# TD4_CPU.net
KiCad netlist of a schematic drawn in Altium Designer
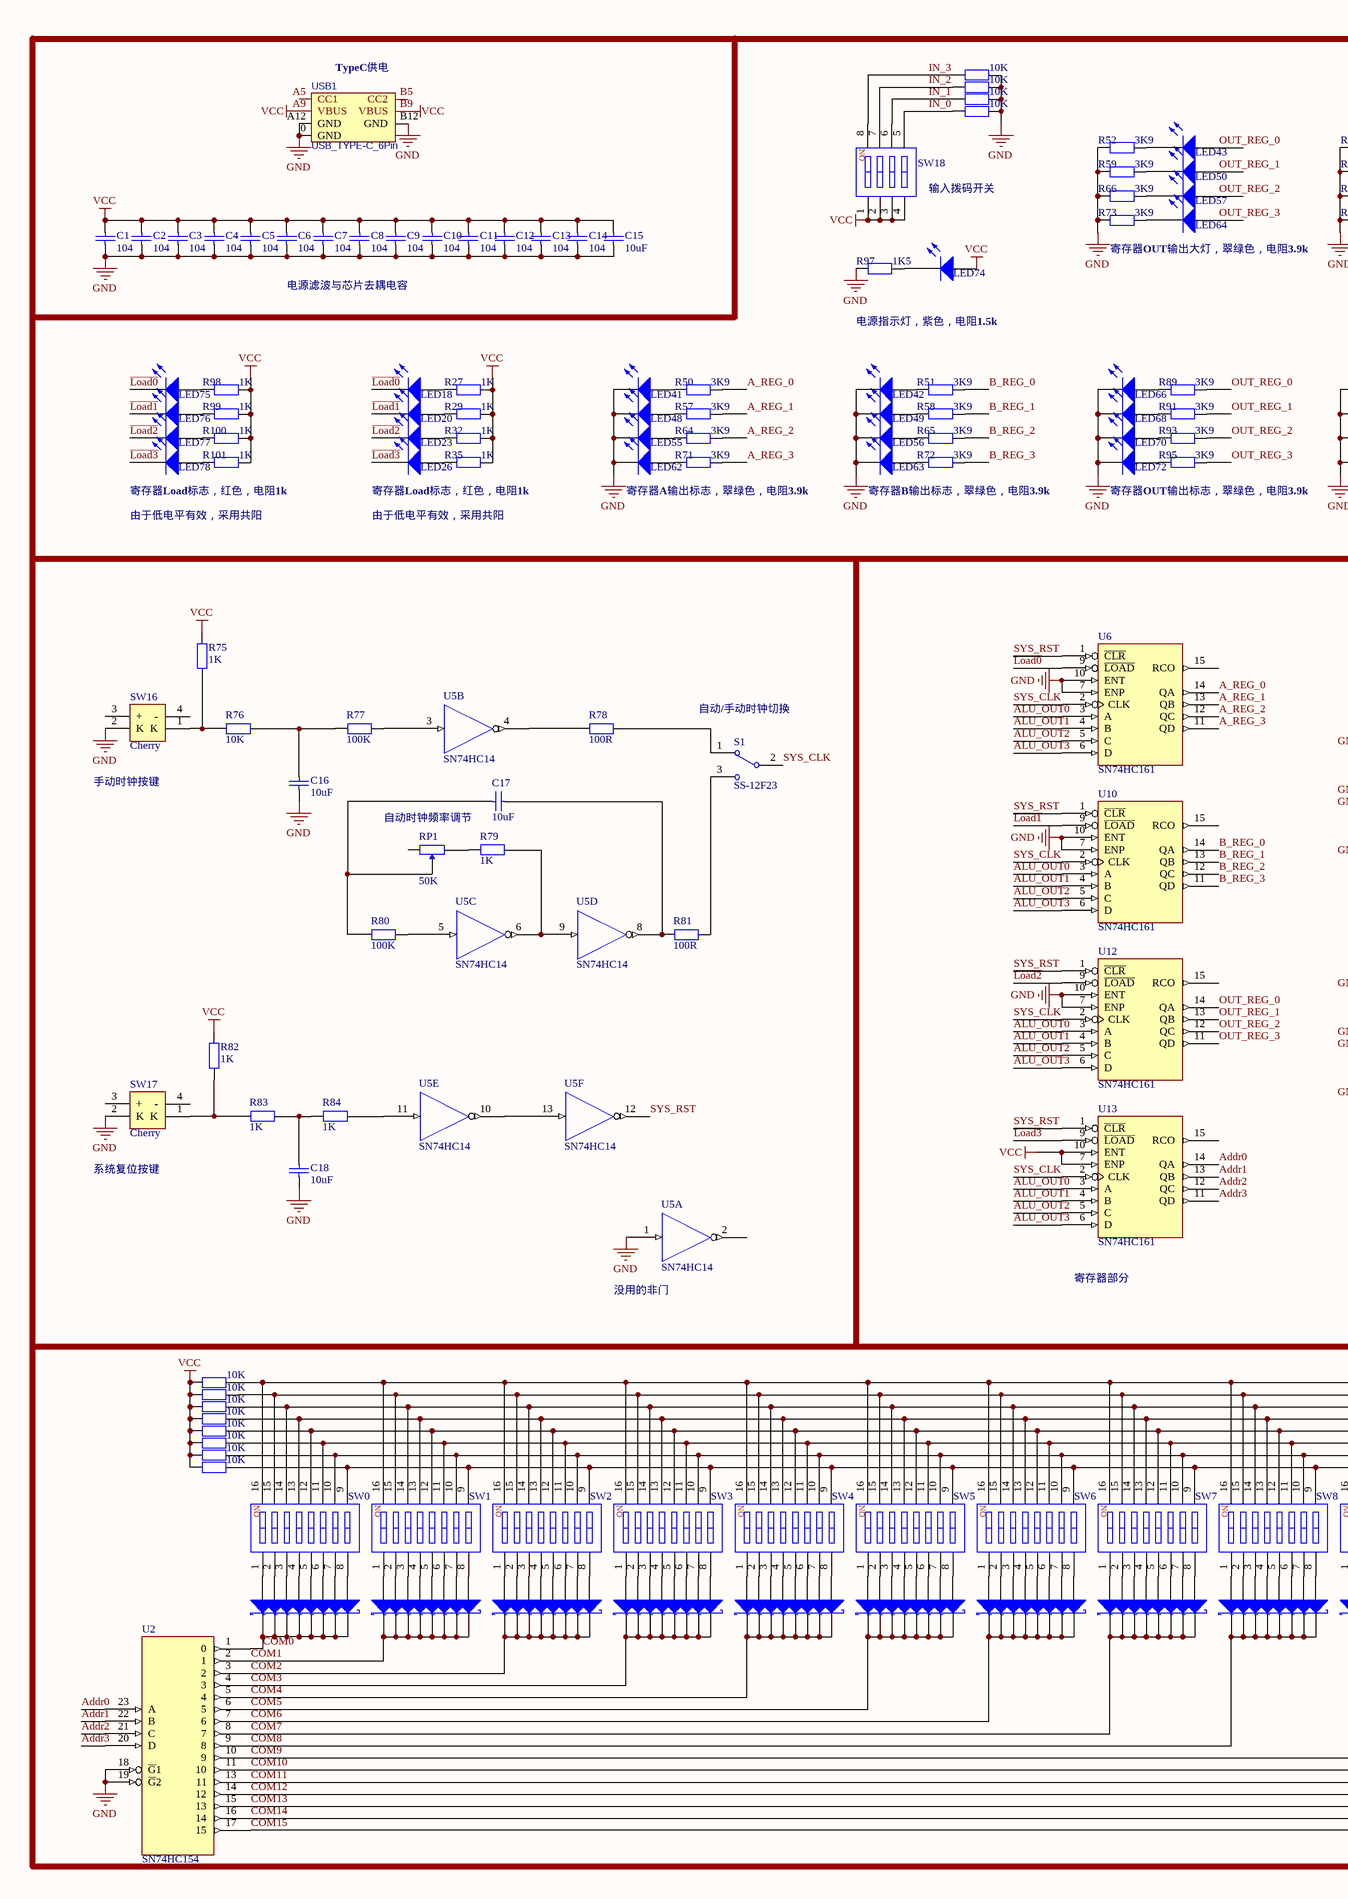
[diagram p0: TD4_CPU.SchDoc, left]
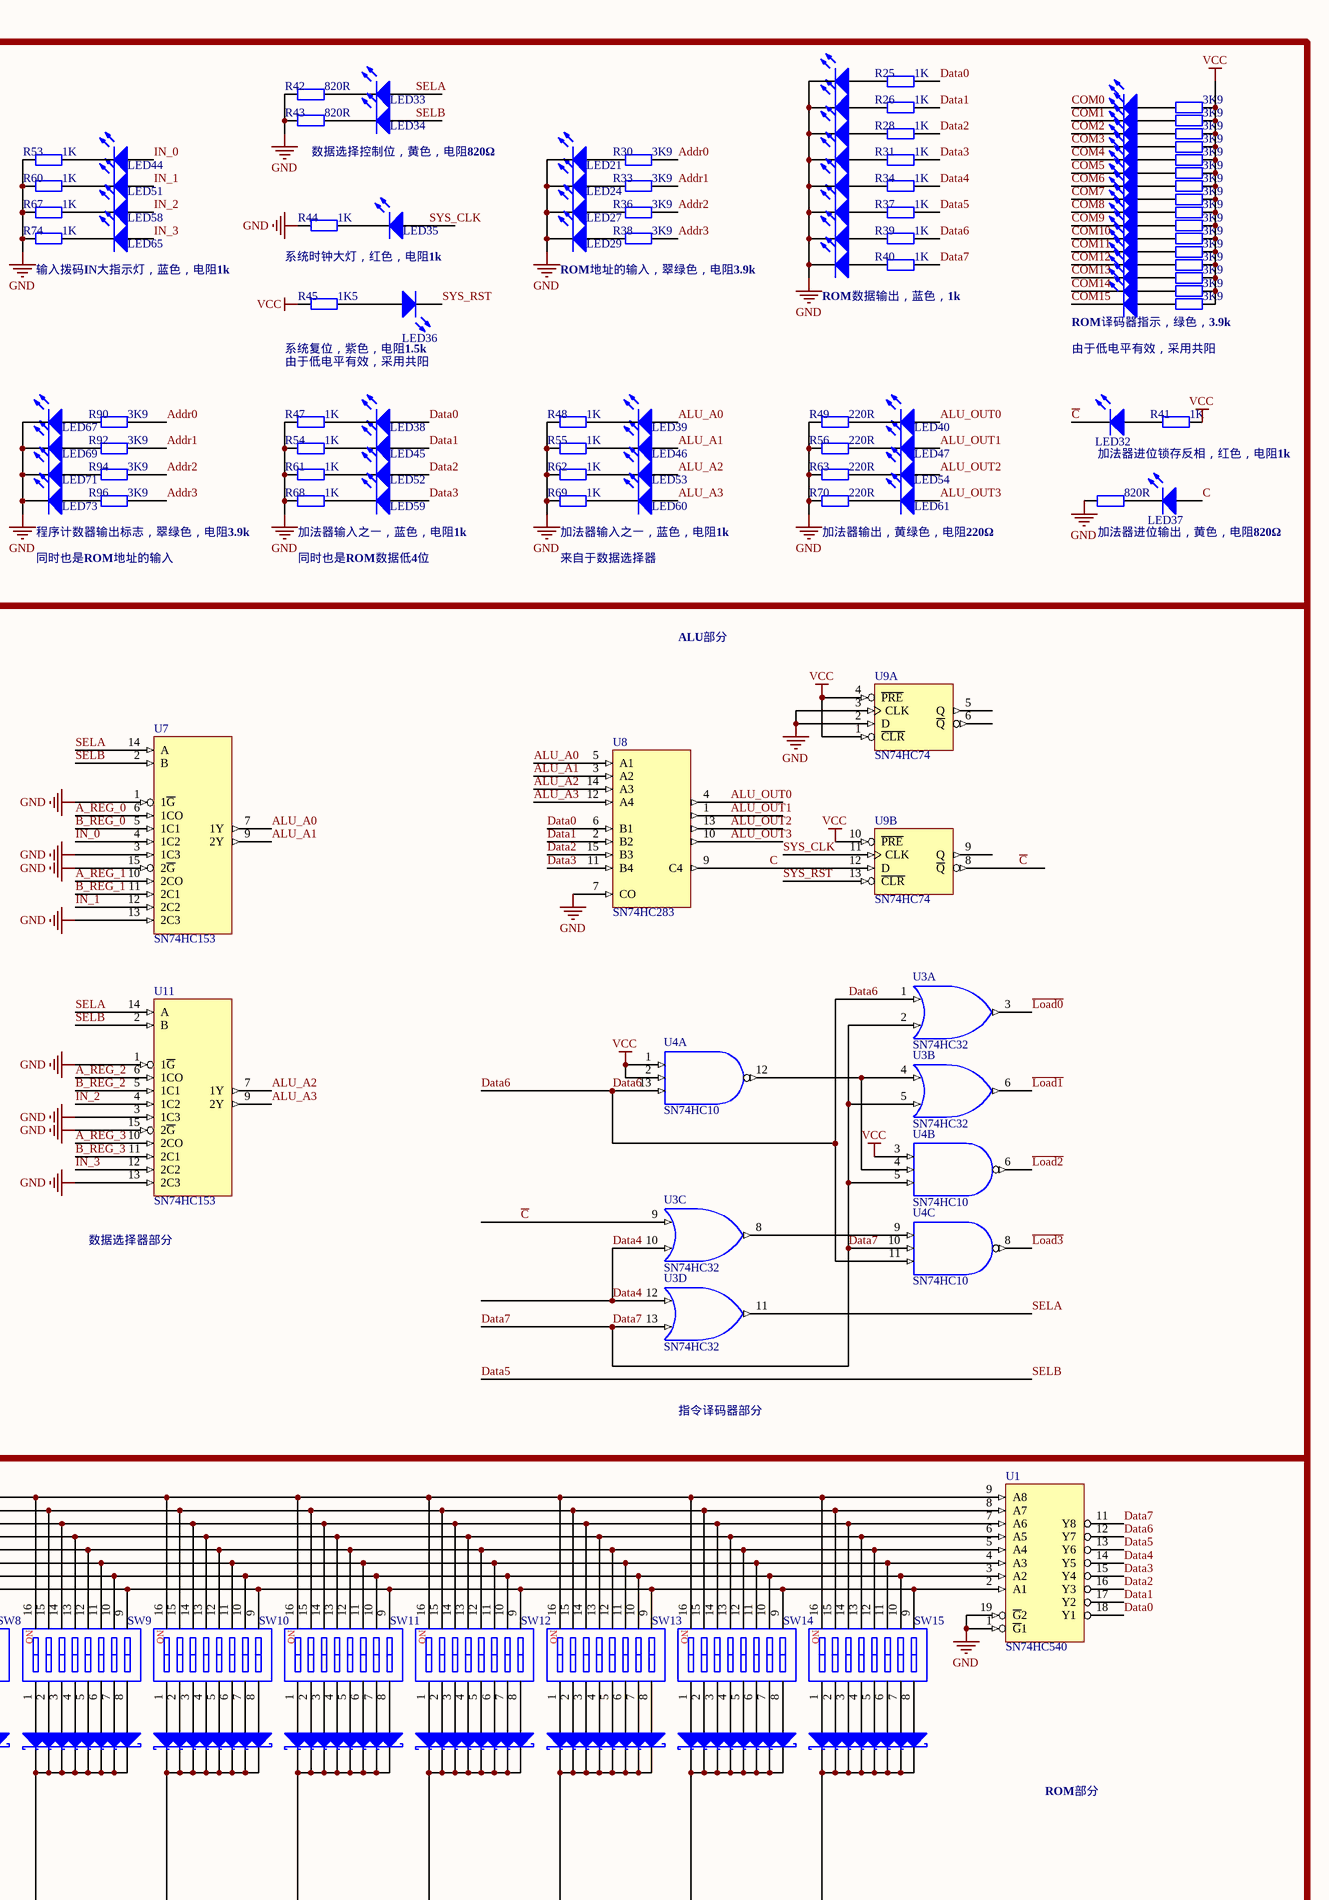
[diagram p1: TD4_CPU.SchDoc, right]

(export (version "E")
  (design (tool "Eeschema 10.0.6"))
  (components
    (comp (ref "C1")
      (value "104")
      (footprint "C0805_L")
      (description "贴片电容/MLCC电容")
      (libsource (lib "0.1 - 电阻-电容-电感-保险丝-晶振-晶体-磁珠-电位器-法拉电容-馈通电容") (part "C"))
    )
    (comp (ref "C2")
      (value "104")
      (footprint "C0805_L")
      (description "贴片电容/MLCC电容")
      (libsource (lib "0.1 - 电阻-电容-电感-保险丝-晶振-晶体-磁珠-电位器-法拉电容-馈通电容") (part "C"))
    )
    (comp (ref "C3")
      (value "104")
      (footprint "C0805_L")
      (description "贴片电容/MLCC电容")
      (libsource (lib "0.1 - 电阻-电容-电感-保险丝-晶振-晶体-磁珠-电位器-法拉电容-馈通电容") (part "C"))
    )
    (comp (ref "C4")
      (value "104")
      (footprint "C0805_L")
      (description "贴片电容/MLCC电容")
      (libsource (lib "0.1 - 电阻-电容-电感-保险丝-晶振-晶体-磁珠-电位器-法拉电容-馈通电容") (part "C"))
    )
    (comp (ref "C5")
      (value "104")
      (footprint "C0805_L")
      (description "贴片电容/MLCC电容")
      (libsource (lib "0.1 - 电阻-电容-电感-保险丝-晶振-晶体-磁珠-电位器-法拉电容-馈通电容") (part "C"))
    )
    (comp (ref "C6")
      (value "104")
      (footprint "C0805_L")
      (description "贴片电容/MLCC电容")
      (libsource (lib "0.1 - 电阻-电容-电感-保险丝-晶振-晶体-磁珠-电位器-法拉电容-馈通电容") (part "C"))
    )
    (comp (ref "C7")
      (value "104")
      (footprint "C0805_L")
      (description "贴片电容/MLCC电容")
      (libsource (lib "0.1 - 电阻-电容-电感-保险丝-晶振-晶体-磁珠-电位器-法拉电容-馈通电容") (part "C"))
    )
    (comp (ref "C8")
      (value "104")
      (footprint "C0805_L")
      (description "贴片电容/MLCC电容")
      (libsource (lib "0.1 - 电阻-电容-电感-保险丝-晶振-晶体-磁珠-电位器-法拉电容-馈通电容") (part "C"))
    )
    (comp (ref "C9")
      (value "104")
      (footprint "C0805_L")
      (description "贴片电容/MLCC电容")
      (libsource (lib "0.1 - 电阻-电容-电感-保险丝-晶振-晶体-磁珠-电位器-法拉电容-馈通电容") (part "C"))
    )
    (comp (ref "C10")
      (value "104")
      (footprint "C0805_L")
      (description "贴片电容/MLCC电容")
      (libsource (lib "0.1 - 电阻-电容-电感-保险丝-晶振-晶体-磁珠-电位器-法拉电容-馈通电容") (part "C"))
    )
    (comp (ref "C11")
      (value "104")
      (footprint "C0805_L")
      (description "贴片电容/MLCC电容")
      (libsource (lib "0.1 - 电阻-电容-电感-保险丝-晶振-晶体-磁珠-电位器-法拉电容-馈通电容") (part "C"))
    )
    (comp (ref "C12")
      (value "104")
      (footprint "C0805_L")
      (description "贴片电容/MLCC电容")
      (libsource (lib "0.1 - 电阻-电容-电感-保险丝-晶振-晶体-磁珠-电位器-法拉电容-馈通电容") (part "C"))
    )
    (comp (ref "C13")
      (value "104")
      (footprint "C0805_L")
      (description "贴片电容/MLCC电容")
      (libsource (lib "0.1 - 电阻-电容-电感-保险丝-晶振-晶体-磁珠-电位器-法拉电容-馈通电容") (part "C"))
    )
    (comp (ref "C14")
      (value "104")
      (footprint "C0805_L")
      (description "贴片电容/MLCC电容")
      (libsource (lib "0.1 - 电阻-电容-电感-保险丝-晶振-晶体-磁珠-电位器-法拉电容-馈通电容") (part "C"))
    )
    (comp (ref "C15")
      (value "10uF")
      (footprint "C0805_L")
      (description "贴片电容/MLCC电容")
      (libsource (lib "0.1 - 电阻-电容-电感-保险丝-晶振-晶体-磁珠-电位器-法拉电容-馈通电容") (part "C"))
    )
    (comp (ref "C16")
      (value "10uF")
      (footprint "C0805_L")
      (description "贴片电容/MLCC电容")
      (libsource (lib "0.1 - 电阻-电容-电感-保险丝-晶振-晶体-磁珠-电位器-法拉电容-馈通电容") (part "C"))
    )
    (comp (ref "C17")
      (value "10uF")
      (footprint "C0805_L")
      (description "贴片电容/MLCC电容")
      (libsource (lib "0.1 - 电阻-电容-电感-保险丝-晶振-晶体-磁珠-电位器-法拉电容-馈通电容") (part "C"))
    )
    (comp (ref "C18")
      (value "10uF")
      (footprint "C0805_L")
      (description "贴片电容/MLCC电容")
      (libsource (lib "0.1 - 电阻-电容-电感-保险丝-晶振-晶体-磁珠-电位器-法拉电容-馈通电容") (part "C"))
    )
    (comp (ref "D1")
      (value "SS14")
      (footprint "SOD-123")
      (description "肖特基二极管")
      (libsource (lib "0.2 - 二极管-TVS-ESD-整流桥-放电管") (part "SS14"))
    )
    (comp (ref "D2")
      (value "SS14")
      (footprint "SOD-123")
      (description "肖特基二极管")
      (libsource (lib "0.2 - 二极管-TVS-ESD-整流桥-放电管") (part "SS14"))
    )
    (comp (ref "D3")
      (value "SS14")
      (footprint "SOD-123")
      (description "肖特基二极管")
      (libsource (lib "0.2 - 二极管-TVS-ESD-整流桥-放电管") (part "SS14"))
    )
    (comp (ref "D4")
      (value "SS14")
      (footprint "SOD-123")
      (description "肖特基二极管")
      (libsource (lib "0.2 - 二极管-TVS-ESD-整流桥-放电管") (part "SS14"))
    )
    (comp (ref "D5")
      (value "SS14")
      (footprint "SOD-123")
      (description "肖特基二极管")
      (libsource (lib "0.2 - 二极管-TVS-ESD-整流桥-放电管") (part "SS14"))
    )
    (comp (ref "D6")
      (value "SS14")
      (footprint "SOD-123")
      (description "肖特基二极管")
      (libsource (lib "0.2 - 二极管-TVS-ESD-整流桥-放电管") (part "SS14"))
    )
    (comp (ref "D7")
      (value "SS14")
      (footprint "SOD-123")
      (description "肖特基二极管")
      (libsource (lib "0.2 - 二极管-TVS-ESD-整流桥-放电管") (part "SS14"))
    )
    (comp (ref "D8")
      (value "SS14")
      (footprint "SOD-123")
      (description "肖特基二极管")
      (libsource (lib "0.2 - 二极管-TVS-ESD-整流桥-放电管") (part "SS14"))
    )
    (comp (ref "D9")
      (value "SS14")
      (footprint "SOD-123")
      (description "肖特基二极管")
      (libsource (lib "0.2 - 二极管-TVS-ESD-整流桥-放电管") (part "SS14"))
    )
    (comp (ref "D10")
      (value "SS14")
      (footprint "SOD-123")
      (description "肖特基二极管")
      (libsource (lib "0.2 - 二极管-TVS-ESD-整流桥-放电管") (part "SS14"))
    )
    (comp (ref "D11")
      (value "SS14")
      (footprint "SOD-123")
      (description "肖特基二极管")
      (libsource (lib "0.2 - 二极管-TVS-ESD-整流桥-放电管") (part "SS14"))
    )
    (comp (ref "D12")
      (value "SS14")
      (footprint "SOD-123")
      (description "肖特基二极管")
      (libsource (lib "0.2 - 二极管-TVS-ESD-整流桥-放电管") (part "SS14"))
    )
    (comp (ref "D13")
      (value "SS14")
      (footprint "SOD-123")
      (description "肖特基二极管")
      (libsource (lib "0.2 - 二极管-TVS-ESD-整流桥-放电管") (part "SS14"))
    )
    (comp (ref "D14")
      (value "SS14")
      (footprint "SOD-123")
      (description "肖特基二极管")
      (libsource (lib "0.2 - 二极管-TVS-ESD-整流桥-放电管") (part "SS14"))
    )
    (comp (ref "D15")
      (value "SS14")
      (footprint "SOD-123")
      (description "肖特基二极管")
      (libsource (lib "0.2 - 二极管-TVS-ESD-整流桥-放电管") (part "SS14"))
    )
    (comp (ref "D16")
      (value "SS14")
      (footprint "SOD-123")
      (description "肖特基二极管")
      (libsource (lib "0.2 - 二极管-TVS-ESD-整流桥-放电管") (part "SS14"))
    )
    (comp (ref "D17")
      (value "SS14")
      (footprint "SOD-123")
      (description "肖特基二极管")
      (libsource (lib "0.2 - 二极管-TVS-ESD-整流桥-放电管") (part "SS14"))
    )
    (comp (ref "D18")
      (value "SS14")
      (footprint "SOD-123")
      (description "肖特基二极管")
      (libsource (lib "0.2 - 二极管-TVS-ESD-整流桥-放电管") (part "SS14"))
    )
    (comp (ref "D19")
      (value "SS14")
      (footprint "SOD-123")
      (description "肖特基二极管")
      (libsource (lib "0.2 - 二极管-TVS-ESD-整流桥-放电管") (part "SS14"))
    )
    (comp (ref "D20")
      (value "SS14")
      (footprint "SOD-123")
      (description "肖特基二极管")
      (libsource (lib "0.2 - 二极管-TVS-ESD-整流桥-放电管") (part "SS14"))
    )
    (comp (ref "D21")
      (value "SS14")
      (footprint "SOD-123")
      (description "肖特基二极管")
      (libsource (lib "0.2 - 二极管-TVS-ESD-整流桥-放电管") (part "SS14"))
    )
    (comp (ref "D22")
      (value "SS14")
      (footprint "SOD-123")
      (description "肖特基二极管")
      (libsource (lib "0.2 - 二极管-TVS-ESD-整流桥-放电管") (part "SS14"))
    )
    (comp (ref "D23")
      (value "SS14")
      (footprint "SOD-123")
      (description "肖特基二极管")
      (libsource (lib "0.2 - 二极管-TVS-ESD-整流桥-放电管") (part "SS14"))
    )
    (comp (ref "D24")
      (value "SS14")
      (footprint "SOD-123")
      (description "肖特基二极管")
      (libsource (lib "0.2 - 二极管-TVS-ESD-整流桥-放电管") (part "SS14"))
    )
    (comp (ref "D25")
      (value "SS14")
      (footprint "SOD-123")
      (description "肖特基二极管")
      (libsource (lib "0.2 - 二极管-TVS-ESD-整流桥-放电管") (part "SS14"))
    )
    (comp (ref "D26")
      (value "SS14")
      (footprint "SOD-123")
      (description "肖特基二极管")
      (libsource (lib "0.2 - 二极管-TVS-ESD-整流桥-放电管") (part "SS14"))
    )
    (comp (ref "D27")
      (value "SS14")
      (footprint "SOD-123")
      (description "肖特基二极管")
      (libsource (lib "0.2 - 二极管-TVS-ESD-整流桥-放电管") (part "SS14"))
    )
    (comp (ref "D28")
      (value "SS14")
      (footprint "SOD-123")
      (description "肖特基二极管")
      (libsource (lib "0.2 - 二极管-TVS-ESD-整流桥-放电管") (part "SS14"))
    )
    (comp (ref "D29")
      (value "SS14")
      (footprint "SOD-123")
      (description "肖特基二极管")
      (libsource (lib "0.2 - 二极管-TVS-ESD-整流桥-放电管") (part "SS14"))
    )
    (comp (ref "D30")
      (value "SS14")
      (footprint "SOD-123")
      (description "肖特基二极管")
      (libsource (lib "0.2 - 二极管-TVS-ESD-整流桥-放电管") (part "SS14"))
    )
    (comp (ref "D31")
      (value "SS14")
      (footprint "SOD-123")
      (description "肖特基二极管")
      (libsource (lib "0.2 - 二极管-TVS-ESD-整流桥-放电管") (part "SS14"))
    )
    (comp (ref "D32")
      (value "SS14")
      (footprint "SOD-123")
      (description "肖特基二极管")
      (libsource (lib "0.2 - 二极管-TVS-ESD-整流桥-放电管") (part "SS14"))
    )
    (comp (ref "D33")
      (value "SS14")
      (footprint "SOD-123")
      (description "肖特基二极管")
      (libsource (lib "0.2 - 二极管-TVS-ESD-整流桥-放电管") (part "SS14"))
    )
    (comp (ref "D34")
      (value "SS14")
      (footprint "SOD-123")
      (description "肖特基二极管")
      (libsource (lib "0.2 - 二极管-TVS-ESD-整流桥-放电管") (part "SS14"))
    )
    (comp (ref "D35")
      (value "SS14")
      (footprint "SOD-123")
      (description "肖特基二极管")
      (libsource (lib "0.2 - 二极管-TVS-ESD-整流桥-放电管") (part "SS14"))
    )
    (comp (ref "D36")
      (value "SS14")
      (footprint "SOD-123")
      (description "肖特基二极管")
      (libsource (lib "0.2 - 二极管-TVS-ESD-整流桥-放电管") (part "SS14"))
    )
    (comp (ref "D37")
      (value "SS14")
      (footprint "SOD-123")
      (description "肖特基二极管")
      (libsource (lib "0.2 - 二极管-TVS-ESD-整流桥-放电管") (part "SS14"))
    )
    (comp (ref "D38")
      (value "SS14")
      (footprint "SOD-123")
      (description "肖特基二极管")
      (libsource (lib "0.2 - 二极管-TVS-ESD-整流桥-放电管") (part "SS14"))
    )
    (comp (ref "D39")
      (value "SS14")
      (footprint "SOD-123")
      (description "肖特基二极管")
      (libsource (lib "0.2 - 二极管-TVS-ESD-整流桥-放电管") (part "SS14"))
    )
    (comp (ref "D40")
      (value "SS14")
      (footprint "SOD-123")
      (description "肖特基二极管")
      (libsource (lib "0.2 - 二极管-TVS-ESD-整流桥-放电管") (part "SS14"))
    )
    (comp (ref "D41")
      (value "SS14")
      (footprint "SOD-123")
      (description "肖特基二极管")
      (libsource (lib "0.2 - 二极管-TVS-ESD-整流桥-放电管") (part "SS14"))
    )
    (comp (ref "D42")
      (value "SS14")
      (footprint "SOD-123")
      (description "肖特基二极管")
      (libsource (lib "0.2 - 二极管-TVS-ESD-整流桥-放电管") (part "SS14"))
    )
    (comp (ref "D43")
      (value "SS14")
      (footprint "SOD-123")
      (description "肖特基二极管")
      (libsource (lib "0.2 - 二极管-TVS-ESD-整流桥-放电管") (part "SS14"))
    )
    (comp (ref "D44")
      (value "SS14")
      (footprint "SOD-123")
      (description "肖特基二极管")
      (libsource (lib "0.2 - 二极管-TVS-ESD-整流桥-放电管") (part "SS14"))
    )
    (comp (ref "D45")
      (value "SS14")
      (footprint "SOD-123")
      (description "肖特基二极管")
      (libsource (lib "0.2 - 二极管-TVS-ESD-整流桥-放电管") (part "SS14"))
    )
    (comp (ref "D46")
      (value "SS14")
      (footprint "SOD-123")
      (description "肖特基二极管")
      (libsource (lib "0.2 - 二极管-TVS-ESD-整流桥-放电管") (part "SS14"))
    )
    (comp (ref "D47")
      (value "SS14")
      (footprint "SOD-123")
      (description "肖特基二极管")
      (libsource (lib "0.2 - 二极管-TVS-ESD-整流桥-放电管") (part "SS14"))
    )
    (comp (ref "D48")
      (value "SS14")
      (footprint "SOD-123")
      (description "肖特基二极管")
      (libsource (lib "0.2 - 二极管-TVS-ESD-整流桥-放电管") (part "SS14"))
    )
    (comp (ref "D49")
      (value "SS14")
      (footprint "SOD-123")
      (description "肖特基二极管")
      (libsource (lib "0.2 - 二极管-TVS-ESD-整流桥-放电管") (part "SS14"))
    )
    (comp (ref "D50")
      (value "SS14")
      (footprint "SOD-123")
      (description "肖特基二极管")
      (libsource (lib "0.2 - 二极管-TVS-ESD-整流桥-放电管") (part "SS14"))
    )
    (comp (ref "D51")
      (value "SS14")
      (footprint "SOD-123")
      (description "肖特基二极管")
      (libsource (lib "0.2 - 二极管-TVS-ESD-整流桥-放电管") (part "SS14"))
    )
    (comp (ref "D52")
      (value "SS14")
      (footprint "SOD-123")
      (description "肖特基二极管")
      (libsource (lib "0.2 - 二极管-TVS-ESD-整流桥-放电管") (part "SS14"))
    )
    (comp (ref "D53")
      (value "SS14")
      (footprint "SOD-123")
      (description "肖特基二极管")
      (libsource (lib "0.2 - 二极管-TVS-ESD-整流桥-放电管") (part "SS14"))
    )
    (comp (ref "D54")
      (value "SS14")
      (footprint "SOD-123")
      (description "肖特基二极管")
      (libsource (lib "0.2 - 二极管-TVS-ESD-整流桥-放电管") (part "SS14"))
    )
    (comp (ref "D55")
      (value "SS14")
      (footprint "SOD-123")
      (description "肖特基二极管")
      (libsource (lib "0.2 - 二极管-TVS-ESD-整流桥-放电管") (part "SS14"))
    )
    (comp (ref "D56")
      (value "SS14")
      (footprint "SOD-123")
      (description "肖特基二极管")
      (libsource (lib "0.2 - 二极管-TVS-ESD-整流桥-放电管") (part "SS14"))
    )
    (comp (ref "D57")
      (value "SS14")
      (footprint "SOD-123")
      (description "肖特基二极管")
      (libsource (lib "0.2 - 二极管-TVS-ESD-整流桥-放电管") (part "SS14"))
    )
    (comp (ref "D58")
      (value "SS14")
      (footprint "SOD-123")
      (description "肖特基二极管")
      (libsource (lib "0.2 - 二极管-TVS-ESD-整流桥-放电管") (part "SS14"))
    )
    (comp (ref "D59")
      (value "SS14")
      (footprint "SOD-123")
      (description "肖特基二极管")
      (libsource (lib "0.2 - 二极管-TVS-ESD-整流桥-放电管") (part "SS14"))
    )
    (comp (ref "D60")
      (value "SS14")
      (footprint "SOD-123")
      (description "肖特基二极管")
      (libsource (lib "0.2 - 二极管-TVS-ESD-整流桥-放电管") (part "SS14"))
    )
    (comp (ref "D61")
      (value "SS14")
      (footprint "SOD-123")
      (description "肖特基二极管")
      (libsource (lib "0.2 - 二极管-TVS-ESD-整流桥-放电管") (part "SS14"))
    )
    (comp (ref "D62")
      (value "SS14")
      (footprint "SOD-123")
      (description "肖特基二极管")
      (libsource (lib "0.2 - 二极管-TVS-ESD-整流桥-放电管") (part "SS14"))
    )
    (comp (ref "D63")
      (value "SS14")
      (footprint "SOD-123")
      (description "肖特基二极管")
      (libsource (lib "0.2 - 二极管-TVS-ESD-整流桥-放电管") (part "SS14"))
    )
    (comp (ref "D64")
      (value "SS14")
      (footprint "SOD-123")
      (description "肖特基二极管")
      (libsource (lib "0.2 - 二极管-TVS-ESD-整流桥-放电管") (part "SS14"))
    )
    (comp (ref "D65")
      (value "SS14")
      (footprint "SOD-123")
      (description "肖特基二极管")
      (libsource (lib "0.2 - 二极管-TVS-ESD-整流桥-放电管") (part "SS14"))
    )
    (comp (ref "D66")
      (value "SS14")
      (footprint "SOD-123")
      (description "肖特基二极管")
      (libsource (lib "0.2 - 二极管-TVS-ESD-整流桥-放电管") (part "SS14"))
    )
    (comp (ref "D67")
      (value "SS14")
      (footprint "SOD-123")
      (description "肖特基二极管")
      (libsource (lib "0.2 - 二极管-TVS-ESD-整流桥-放电管") (part "SS14"))
    )
    (comp (ref "D68")
      (value "SS14")
      (footprint "SOD-123")
      (description "肖特基二极管")
      (libsource (lib "0.2 - 二极管-TVS-ESD-整流桥-放电管") (part "SS14"))
    )
    (comp (ref "D69")
      (value "SS14")
      (footprint "SOD-123")
      (description "肖特基二极管")
      (libsource (lib "0.2 - 二极管-TVS-ESD-整流桥-放电管") (part "SS14"))
    )
    (comp (ref "D70")
      (value "SS14")
      (footprint "SOD-123")
      (description "肖特基二极管")
      (libsource (lib "0.2 - 二极管-TVS-ESD-整流桥-放电管") (part "SS14"))
    )
    (comp (ref "D71")
      (value "SS14")
      (footprint "SOD-123")
      (description "肖特基二极管")
      (libsource (lib "0.2 - 二极管-TVS-ESD-整流桥-放电管") (part "SS14"))
    )
    (comp (ref "D72")
      (value "SS14")
      (footprint "SOD-123")
      (description "肖特基二极管")
      (libsource (lib "0.2 - 二极管-TVS-ESD-整流桥-放电管") (part "SS14"))
    )
    (comp (ref "D73")
      (value "SS14")
      (footprint "SOD-123")
      (description "肖特基二极管")
      (libsource (lib "0.2 - 二极管-TVS-ESD-整流桥-放电管") (part "SS14"))
    )
    (comp (ref "D74")
      (value "SS14")
      (footprint "SOD-123")
      (description "肖特基二极管")
      (libsource (lib "0.2 - 二极管-TVS-ESD-整流桥-放电管") (part "SS14"))
    )
    (comp (ref "D75")
      (value "SS14")
      (footprint "SOD-123")
      (description "肖特基二极管")
      (libsource (lib "0.2 - 二极管-TVS-ESD-整流桥-放电管") (part "SS14"))
    )
    (comp (ref "D76")
      (value "SS14")
      (footprint "SOD-123")
      (description "肖特基二极管")
      (libsource (lib "0.2 - 二极管-TVS-ESD-整流桥-放电管") (part "SS14"))
    )
    (comp (ref "D77")
      (value "SS14")
      (footprint "SOD-123")
      (description "肖特基二极管")
      (libsource (lib "0.2 - 二极管-TVS-ESD-整流桥-放电管") (part "SS14"))
    )
    (comp (ref "D78")
      (value "SS14")
      (footprint "SOD-123")
      (description "肖特基二极管")
      (libsource (lib "0.2 - 二极管-TVS-ESD-整流桥-放电管") (part "SS14"))
    )
    (comp (ref "D79")
      (value "SS14")
      (footprint "SOD-123")
      (description "肖特基二极管")
      (libsource (lib "0.2 - 二极管-TVS-ESD-整流桥-放电管") (part "SS14"))
    )
    (comp (ref "D80")
      (value "SS14")
      (footprint "SOD-123")
      (description "肖特基二极管")
      (libsource (lib "0.2 - 二极管-TVS-ESD-整流桥-放电管") (part "SS14"))
    )
    (comp (ref "D81")
      (value "SS14")
      (footprint "SOD-123")
      (description "肖特基二极管")
      (libsource (lib "0.2 - 二极管-TVS-ESD-整流桥-放电管") (part "SS14"))
    )
    (comp (ref "D82")
      (value "SS14")
      (footprint "SOD-123")
      (description "肖特基二极管")
      (libsource (lib "0.2 - 二极管-TVS-ESD-整流桥-放电管") (part "SS14"))
    )
    (comp (ref "D83")
      (value "SS14")
      (footprint "SOD-123")
      (description "肖特基二极管")
      (libsource (lib "0.2 - 二极管-TVS-ESD-整流桥-放电管") (part "SS14"))
    )
    (comp (ref "D84")
      (value "SS14")
      (footprint "SOD-123")
      (description "肖特基二极管")
      (libsource (lib "0.2 - 二极管-TVS-ESD-整流桥-放电管") (part "SS14"))
    )
    (comp (ref "D85")
      (value "SS14")
      (footprint "SOD-123")
      (description "肖特基二极管")
      (libsource (lib "0.2 - 二极管-TVS-ESD-整流桥-放电管") (part "SS14"))
    )
    (comp (ref "D86")
      (value "SS14")
      (footprint "SOD-123")
      (description "肖特基二极管")
      (libsource (lib "0.2 - 二极管-TVS-ESD-整流桥-放电管") (part "SS14"))
    )
    (comp (ref "D87")
      (value "SS14")
      (footprint "SOD-123")
      (description "肖特基二极管")
      (libsource (lib "0.2 - 二极管-TVS-ESD-整流桥-放电管") (part "SS14"))
    )
    (comp (ref "D88")
      (value "SS14")
      (footprint "SOD-123")
      (description "肖特基二极管")
      (libsource (lib "0.2 - 二极管-TVS-ESD-整流桥-放电管") (part "SS14"))
    )
    (comp (ref "D89")
      (value "SS14")
      (footprint "SOD-123")
      (description "肖特基二极管")
      (libsource (lib "0.2 - 二极管-TVS-ESD-整流桥-放电管") (part "SS14"))
    )
    (comp (ref "D90")
      (value "SS14")
      (footprint "SOD-123")
      (description "肖特基二极管")
      (libsource (lib "0.2 - 二极管-TVS-ESD-整流桥-放电管") (part "SS14"))
    )
    (comp (ref "D91")
      (value "SS14")
      (footprint "SOD-123")
      (description "肖特基二极管")
      (libsource (lib "0.2 - 二极管-TVS-ESD-整流桥-放电管") (part "SS14"))
    )
    (comp (ref "D92")
      (value "SS14")
      (footprint "SOD-123")
      (description "肖特基二极管")
      (libsource (lib "0.2 - 二极管-TVS-ESD-整流桥-放电管") (part "SS14"))
    )
    (comp (ref "D93")
      (value "SS14")
      (footprint "SOD-123")
      (description "肖特基二极管")
      (libsource (lib "0.2 - 二极管-TVS-ESD-整流桥-放电管") (part "SS14"))
    )
    (comp (ref "D94")
      (value "SS14")
      (footprint "SOD-123")
      (description "肖特基二极管")
      (libsource (lib "0.2 - 二极管-TVS-ESD-整流桥-放电管") (part "SS14"))
    )
    (comp (ref "D95")
      (value "SS14")
      (footprint "SOD-123")
      (description "肖特基二极管")
      (libsource (lib "0.2 - 二极管-TVS-ESD-整流桥-放电管") (part "SS14"))
    )
    (comp (ref "D96")
      (value "SS14")
      (footprint "SOD-123")
      (description "肖特基二极管")
      (libsource (lib "0.2 - 二极管-TVS-ESD-整流桥-放电管") (part "SS14"))
    )
    (comp (ref "D97")
      (value "SS14")
      (footprint "SOD-123")
      (description "肖特基二极管")
      (libsource (lib "0.2 - 二极管-TVS-ESD-整流桥-放电管") (part "SS14"))
    )
    (comp (ref "D98")
      (value "SS14")
      (footprint "SOD-123")
      (description "肖特基二极管")
      (libsource (lib "0.2 - 二极管-TVS-ESD-整流桥-放电管") (part "SS14"))
    )
    (comp (ref "D99")
      (value "SS14")
      (footprint "SOD-123")
      (description "肖特基二极管")
      (libsource (lib "0.2 - 二极管-TVS-ESD-整流桥-放电管") (part "SS14"))
    )
    (comp (ref "D100")
      (value "SS14")
      (footprint "SOD-123")
      (description "肖特基二极管")
      (libsource (lib "0.2 - 二极管-TVS-ESD-整流桥-放电管") (part "SS14"))
    )
    (comp (ref "D101")
      (value "SS14")
      (footprint "SOD-123")
      (description "肖特基二极管")
      (libsource (lib "0.2 - 二极管-TVS-ESD-整流桥-放电管") (part "SS14"))
    )
    (comp (ref "D102")
      (value "SS14")
      (footprint "SOD-123")
      (description "肖特基二极管")
      (libsource (lib "0.2 - 二极管-TVS-ESD-整流桥-放电管") (part "SS14"))
    )
    (comp (ref "D103")
      (value "SS14")
      (footprint "SOD-123")
      (description "肖特基二极管")
      (libsource (lib "0.2 - 二极管-TVS-ESD-整流桥-放电管") (part "SS14"))
    )
    (comp (ref "D104")
      (value "SS14")
      (footprint "SOD-123")
      (description "肖特基二极管")
      (libsource (lib "0.2 - 二极管-TVS-ESD-整流桥-放电管") (part "SS14"))
    )
    (comp (ref "D105")
      (value "SS14")
      (footprint "SOD-123")
      (description "肖特基二极管")
      (libsource (lib "0.2 - 二极管-TVS-ESD-整流桥-放电管") (part "SS14"))
    )
    (comp (ref "D106")
      (value "SS14")
      (footprint "SOD-123")
      (description "肖特基二极管")
      (libsource (lib "0.2 - 二极管-TVS-ESD-整流桥-放电管") (part "SS14"))
    )
    (comp (ref "D107")
      (value "SS14")
      (footprint "SOD-123")
      (description "肖特基二极管")
      (libsource (lib "0.2 - 二极管-TVS-ESD-整流桥-放电管") (part "SS14"))
    )
    (comp (ref "D108")
      (value "SS14")
      (footprint "SOD-123")
      (description "肖特基二极管")
      (libsource (lib "0.2 - 二极管-TVS-ESD-整流桥-放电管") (part "SS14"))
    )
    (comp (ref "D109")
      (value "SS14")
      (footprint "SOD-123")
      (description "肖特基二极管")
      (libsource (lib "0.2 - 二极管-TVS-ESD-整流桥-放电管") (part "SS14"))
    )
    (comp (ref "D110")
      (value "SS14")
      (footprint "SOD-123")
      (description "肖特基二极管")
      (libsource (lib "0.2 - 二极管-TVS-ESD-整流桥-放电管") (part "SS14"))
    )
    (comp (ref "D111")
      (value "SS14")
      (footprint "SOD-123")
      (description "肖特基二极管")
      (libsource (lib "0.2 - 二极管-TVS-ESD-整流桥-放电管") (part "SS14"))
    )
    (comp (ref "D112")
      (value "SS14")
      (footprint "SOD-123")
      (description "肖特基二极管")
      (libsource (lib "0.2 - 二极管-TVS-ESD-整流桥-放电管") (part "SS14"))
    )
    (comp (ref "D113")
      (value "SS14")
      (footprint "SOD-123")
      (description "肖特基二极管")
      (libsource (lib "0.2 - 二极管-TVS-ESD-整流桥-放电管") (part "SS14"))
    )
    (comp (ref "D114")
      (value "SS14")
      (footprint "SOD-123")
      (description "肖特基二极管")
      (libsource (lib "0.2 - 二极管-TVS-ESD-整流桥-放电管") (part "SS14"))
    )
    (comp (ref "D115")
      (value "SS14")
      (footprint "SOD-123")
      (description "肖特基二极管")
      (libsource (lib "0.2 - 二极管-TVS-ESD-整流桥-放电管") (part "SS14"))
    )
    (comp (ref "D116")
      (value "SS14")
      (footprint "SOD-123")
      (description "肖特基二极管")
      (libsource (lib "0.2 - 二极管-TVS-ESD-整流桥-放电管") (part "SS14"))
    )
    (comp (ref "D117")
      (value "SS14")
      (footprint "SOD-123")
      (description "肖特基二极管")
      (libsource (lib "0.2 - 二极管-TVS-ESD-整流桥-放电管") (part "SS14"))
    )
    (comp (ref "D118")
      (value "SS14")
      (footprint "SOD-123")
      (description "肖特基二极管")
      (libsource (lib "0.2 - 二极管-TVS-ESD-整流桥-放电管") (part "SS14"))
    )
    (comp (ref "D119")
      (value "SS14")
      (footprint "SOD-123")
      (description "肖特基二极管")
      (libsource (lib "0.2 - 二极管-TVS-ESD-整流桥-放电管") (part "SS14"))
    )
    (comp (ref "D120")
      (value "SS14")
      (footprint "SOD-123")
      (description "肖特基二极管")
      (libsource (lib "0.2 - 二极管-TVS-ESD-整流桥-放电管") (part "SS14"))
    )
    (comp (ref "D121")
      (value "SS14")
      (footprint "SOD-123")
      (description "肖特基二极管")
      (libsource (lib "0.2 - 二极管-TVS-ESD-整流桥-放电管") (part "SS14"))
    )
    (comp (ref "D122")
      (value "SS14")
      (footprint "SOD-123")
      (description "肖特基二极管")
      (libsource (lib "0.2 - 二极管-TVS-ESD-整流桥-放电管") (part "SS14"))
    )
    (comp (ref "D123")
      (value "SS14")
      (footprint "SOD-123")
      (description "肖特基二极管")
      (libsource (lib "0.2 - 二极管-TVS-ESD-整流桥-放电管") (part "SS14"))
    )
    (comp (ref "D124")
      (value "SS14")
      (footprint "SOD-123")
      (description "肖特基二极管")
      (libsource (lib "0.2 - 二极管-TVS-ESD-整流桥-放电管") (part "SS14"))
    )
    (comp (ref "D125")
      (value "SS14")
      (footprint "SOD-123")
      (description "肖特基二极管")
      (libsource (lib "0.2 - 二极管-TVS-ESD-整流桥-放电管") (part "SS14"))
    )
    (comp (ref "D126")
      (value "SS14")
      (footprint "SOD-123")
      (description "肖特基二极管")
      (libsource (lib "0.2 - 二极管-TVS-ESD-整流桥-放电管") (part "SS14"))
    )
    (comp (ref "D127")
      (value "SS14")
      (footprint "SOD-123")
      (description "肖特基二极管")
      (libsource (lib "0.2 - 二极管-TVS-ESD-整流桥-放电管") (part "SS14"))
    )
    (comp (ref "D128")
      (value "SS14")
      (footprint "SOD-123")
      (description "肖特基二极管")
      (libsource (lib "0.2 - 二极管-TVS-ESD-整流桥-放电管") (part "SS14"))
    )
    (comp (ref "LED0")
      (value "绿色")
      (footprint "LED0805_B")
      (description "贴片LED")
      (libsource (lib "0.3 - LED发光二极管-IR二极管_接收管-光耦") (part "LED"))
    )
    (comp (ref "LED1")
      (value "绿色")
      (footprint "LED0805_B")
      (description "贴片LED")
      (libsource (lib "0.3 - LED发光二极管-IR二极管_接收管-光耦") (part "LED"))
    )
    (comp (ref "LED2")
      (value "绿色")
      (footprint "LED0805_B")
      (description "贴片LED")
      (libsource (lib "0.3 - LED发光二极管-IR二极管_接收管-光耦") (part "LED"))
    )
    (comp (ref "LED3")
      (value "绿色")
      (footprint "LED0805_B")
      (description "贴片LED")
      (libsource (lib "0.3 - LED发光二极管-IR二极管_接收管-光耦") (part "LED"))
    )
    (comp (ref "LED4")
      (value "绿色")
      (footprint "LED0805_B")
      (description "贴片LED")
      (libsource (lib "0.3 - LED发光二极管-IR二极管_接收管-光耦") (part "LED"))
    )
    (comp (ref "LED5")
      (value "绿色")
      (footprint "LED0805_B")
      (description "贴片LED")
      (libsource (lib "0.3 - LED发光二极管-IR二极管_接收管-光耦") (part "LED"))
    )
    (comp (ref "LED6")
      (value "绿色")
      (footprint "LED0805_B")
      (description "贴片LED")
      (libsource (lib "0.3 - LED发光二极管-IR二极管_接收管-光耦") (part "LED"))
    )
    (comp (ref "LED7")
      (value "绿色")
      (footprint "LED0805_B")
      (description "贴片LED")
      (libsource (lib "0.3 - LED发光二极管-IR二极管_接收管-光耦") (part "LED"))
    )
    (comp (ref "LED8")
      (value "绿色")
      (footprint "LED0805_B")
      (description "贴片LED")
      (libsource (lib "0.3 - LED发光二极管-IR二极管_接收管-光耦") (part "LED"))
    )
    (comp (ref "LED9")
      (value "绿色")
      (footprint "LED0805_B")
      (description "贴片LED")
      (libsource (lib "0.3 - LED发光二极管-IR二极管_接收管-光耦") (part "LED"))
    )
    (comp (ref "LED10")
      (value "绿色")
      (footprint "LED0805_B")
      (description "贴片LED")
      (libsource (lib "0.3 - LED发光二极管-IR二极管_接收管-光耦") (part "LED"))
    )
    (comp (ref "LED11")
      (value "绿色")
      (footprint "LED0805_B")
      (description "贴片LED")
      (libsource (lib "0.3 - LED发光二极管-IR二极管_接收管-光耦") (part "LED"))
    )
    (comp (ref "LED12")
      (value "绿色")
      (footprint "LED0805_B")
      (description "贴片LED")
      (libsource (lib "0.3 - LED发光二极管-IR二极管_接收管-光耦") (part "LED"))
    )
    (comp (ref "LED13")
      (value "绿色")
      (footprint "LED0805_B")
      (description "贴片LED")
      (libsource (lib "0.3 - LED发光二极管-IR二极管_接收管-光耦") (part "LED"))
    )
    (comp (ref "LED14")
      (value "绿色")
      (footprint "LED0805_B")
      (description "贴片LED")
      (libsource (lib "0.3 - LED发光二极管-IR二极管_接收管-光耦") (part "LED"))
    )
    (comp (ref "LED15")
      (value "绿色")
      (footprint "LED0805_B")
      (description "贴片LED")
      (libsource (lib "0.3 - LED发光二极管-IR二极管_接收管-光耦") (part "LED"))
    )
    (comp (ref "LED16")
      (value "蓝色")
      (footprint "LED0805_B")
      (description "贴片LED")
      (libsource (lib "0.3 - LED发光二极管-IR二极管_接收管-光耦") (part "LED"))
    )
    (comp (ref "LED17")
      (value "蓝色")
      (footprint "LED0805_B")
      (description "贴片LED")
      (libsource (lib "0.3 - LED发光二极管-IR二极管_接收管-光耦") (part "LED"))
    )
    (comp (ref "LED18")
      (value "红色")
      (footprint "LED0805_B")
      (description "贴片LED")
      (libsource (lib "0.3 - LED发光二极管-IR二极管_接收管-光耦") (part "LED"))
    )
    (comp (ref "LED19")
      (value "蓝色")
      (footprint "LED0805_B")
      (description "贴片LED")
      (libsource (lib "0.3 - LED发光二极管-IR二极管_接收管-光耦") (part "LED"))
    )
    (comp (ref "LED20")
      (value "红色")
      (footprint "LED0805_B")
      (description "贴片LED")
      (libsource (lib "0.3 - LED发光二极管-IR二极管_接收管-光耦") (part "LED"))
    )
    (comp (ref "LED21")
      (value "绿色")
      (footprint "LED0805_B")
      (description "贴片LED")
      (libsource (lib "0.3 - LED发光二极管-IR二极管_接收管-光耦") (part "LED"))
    )
    (comp (ref "LED22")
      (value "蓝色")
      (footprint "LED0805_B")
      (description "贴片LED")
      (libsource (lib "0.3 - LED发光二极管-IR二极管_接收管-光耦") (part "LED"))
    )
    (comp (ref "LED23")
      (value "红色")
      (footprint "LED0805_B")
      (description "贴片LED")
      (libsource (lib "0.3 - LED发光二极管-IR二极管_接收管-光耦") (part "LED"))
    )
    (comp (ref "LED24")
      (value "绿色")
      (footprint "LED0805_B")
      (description "贴片LED")
      (libsource (lib "0.3 - LED发光二极管-IR二极管_接收管-光耦") (part "LED"))
    )
    (comp (ref "LED25")
      (value "蓝色")
      (footprint "LED0805_B")
      (description "贴片LED")
      (libsource (lib "0.3 - LED发光二极管-IR二极管_接收管-光耦") (part "LED"))
    )
    (comp (ref "LED26")
      (value "红色")
      (footprint "LED0805_B")
      (description "贴片LED")
      (libsource (lib "0.3 - LED发光二极管-IR二极管_接收管-光耦") (part "LED"))
    )
    (comp (ref "LED27")
      (value "绿色")
      (footprint "LED0805_B")
      (description "贴片LED")
      (libsource (lib "0.3 - LED发光二极管-IR二极管_接收管-光耦") (part "LED"))
    )
    (comp (ref "LED28")
      (value "蓝色")
      (footprint "LED0805_B")
      (description "贴片LED")
      (libsource (lib "0.3 - LED发光二极管-IR二极管_接收管-光耦") (part "LED"))
    )
    (comp (ref "LED29")
      (value "绿色")
      (footprint "LED0805_B")
      (description "贴片LED")
      (libsource (lib "0.3 - LED发光二极管-IR二极管_接收管-光耦") (part "LED"))
    )
    (comp (ref "LED30")
      (value "蓝色")
      (footprint "LED0805_B")
      (description "贴片LED")
      (libsource (lib "0.3 - LED发光二极管-IR二极管_接收管-光耦") (part "LED"))
    )
    (comp (ref "LED31")
      (value "蓝色")
      (footprint "LED0805_B")
      (description "贴片LED")
      (libsource (lib "0.3 - LED发光二极管-IR二极管_接收管-光耦") (part "LED"))
    )
    (comp (ref "LED32")
      (value "红色")
      (footprint "LED0805_B")
      (description "贴片LED")
      (libsource (lib "0.3 - LED发光二极管-IR二极管_接收管-光耦") (part "LED"))
    )
    (comp (ref "LED33")
      (value "黄色")
      (footprint "LED0805_B")
      (description "贴片LED")
      (libsource (lib "0.3 - LED发光二极管-IR二极管_接收管-光耦") (part "LED"))
    )
    (comp (ref "LED34")
      (value "黄色")
      (footprint "LED0805_B")
      (description "贴片LED")
      (libsource (lib "0.3 - LED发光二极管-IR二极管_接收管-光耦") (part "LED"))
    )
    (comp (ref "LED35")
      (value "红色")
      (footprint "LED F257-W - duplicate")
      (description "贴片LED")
      (libsource (lib "0.3 - LED发光二极管-IR二极管_接收管-光耦") (part "LED"))
    )
    (comp (ref "LED36")
      (value "紫色")
      (footprint "LED0805_B")
      (description "贴片LED")
      (libsource (lib "0.3 - LED发光二极管-IR二极管_接收管-光耦") (part "LED"))
    )
    (comp (ref "LED37")
      (value "黄色")
      (footprint "LED0805_B")
      (description "贴片LED")
      (libsource (lib "0.3 - LED发光二极管-IR二极管_接收管-光耦") (part "LED"))
    )
    (comp (ref "LED38")
      (value "蓝色")
      (footprint "LED0805_B")
      (description "贴片LED")
      (libsource (lib "0.3 - LED发光二极管-IR二极管_接收管-光耦") (part "LED"))
    )
    (comp (ref "LED39")
      (value "红色")
      (footprint "LED0805_B")
      (description "贴片LED")
      (libsource (lib "0.3 - LED发光二极管-IR二极管_接收管-光耦") (part "LED"))
    )
    (comp (ref "LED40")
      (value "黄绿色")
      (footprint "LED0805_B")
      (description "贴片LED")
      (libsource (lib "0.3 - LED发光二极管-IR二极管_接收管-光耦") (part "LED"))
    )
    (comp (ref "LED41")
      (value "绿色")
      (footprint "LED0805_B")
      (description "贴片LED")
      (libsource (lib "0.3 - LED发光二极管-IR二极管_接收管-光耦") (part "LED"))
    )
    (comp (ref "LED42")
      (value "绿色")
      (footprint "LED0805_B")
      (description "贴片LED")
      (libsource (lib "0.3 - LED发光二极管-IR二极管_接收管-光耦") (part "LED"))
    )
    (comp (ref "LED43")
      (value "绿色")
      (footprint "LED F257-W - duplicate")
      (description "贴片LED")
      (libsource (lib "0.3 - LED发光二极管-IR二极管_接收管-光耦") (part "LED"))
    )
    (comp (ref "LED44")
      (value "蓝色")
      (footprint "LED F257-W - duplicate")
      (description "贴片LED")
      (libsource (lib "0.3 - LED发光二极管-IR二极管_接收管-光耦") (part "LED"))
    )
    (comp (ref "LED45")
      (value "蓝色")
      (footprint "LED0805_B")
      (description "贴片LED")
      (libsource (lib "0.3 - LED发光二极管-IR二极管_接收管-光耦") (part "LED"))
    )
    (comp (ref "LED46")
      (value "红色")
      (footprint "LED0805_B")
      (description "贴片LED")
      (libsource (lib "0.3 - LED发光二极管-IR二极管_接收管-光耦") (part "LED"))
    )
    (comp (ref "LED47")
      (value "黄绿色")
      (footprint "LED0805_B")
      (description "贴片LED")
      (libsource (lib "0.3 - LED发光二极管-IR二极管_接收管-光耦") (part "LED"))
    )
    (comp (ref "LED48")
      (value "绿色")
      (footprint "LED0805_B")
      (description "贴片LED")
      (libsource (lib "0.3 - LED发光二极管-IR二极管_接收管-光耦") (part "LED"))
    )
    (comp (ref "LED49")
      (value "绿色")
      (footprint "LED0805_B")
      (description "贴片LED")
      (libsource (lib "0.3 - LED发光二极管-IR二极管_接收管-光耦") (part "LED"))
    )
    (comp (ref "LED50")
      (value "绿色")
      (footprint "LED F257-W - duplicate")
      (description "贴片LED")
      (libsource (lib "0.3 - LED发光二极管-IR二极管_接收管-光耦") (part "LED"))
    )
    (comp (ref "LED51")
      (value "蓝色")
      (footprint "LED F257-W - duplicate")
      (description "贴片LED")
      (libsource (lib "0.3 - LED发光二极管-IR二极管_接收管-光耦") (part "LED"))
    )
    (comp (ref "LED52")
      (value "蓝色")
      (footprint "LED0805_B")
      (description "贴片LED")
      (libsource (lib "0.3 - LED发光二极管-IR二极管_接收管-光耦") (part "LED"))
    )
    (comp (ref "LED53")
      (value "红色")
      (footprint "LED0805_B")
      (description "贴片LED")
      (libsource (lib "0.3 - LED发光二极管-IR二极管_接收管-光耦") (part "LED"))
    )
    (comp (ref "LED54")
      (value "黄绿色")
      (footprint "LED0805_B")
      (description "贴片LED")
      (libsource (lib "0.3 - LED发光二极管-IR二极管_接收管-光耦") (part "LED"))
    )
    (comp (ref "LED55")
      (value "绿色")
      (footprint "LED0805_B")
      (description "贴片LED")
      (libsource (lib "0.3 - LED发光二极管-IR二极管_接收管-光耦") (part "LED"))
    )
    (comp (ref "LED56")
      (value "绿色")
      (footprint "LED0805_B")
      (description "贴片LED")
      (libsource (lib "0.3 - LED发光二极管-IR二极管_接收管-光耦") (part "LED"))
    )
    (comp (ref "LED57")
      (value "绿色")
      (footprint "LED F257-W - duplicate")
      (description "贴片LED")
      (libsource (lib "0.3 - LED发光二极管-IR二极管_接收管-光耦") (part "LED"))
    )
    (comp (ref "LED58")
      (value "蓝色")
      (footprint "LED F257-W - duplicate")
      (description "贴片LED")
      (libsource (lib "0.3 - LED发光二极管-IR二极管_接收管-光耦") (part "LED"))
    )
    (comp (ref "LED59")
      (value "蓝色")
      (footprint "LED0805_B")
      (description "贴片LED")
      (libsource (lib "0.3 - LED发光二极管-IR二极管_接收管-光耦") (part "LED"))
    )
    (comp (ref "LED60")
      (value "红色")
      (footprint "LED0805_B")
      (description "贴片LED")
      (libsource (lib "0.3 - LED发光二极管-IR二极管_接收管-光耦") (part "LED"))
    )
    (comp (ref "LED61")
      (value "黄绿色")
      (footprint "LED0805_B")
      (description "贴片LED")
      (libsource (lib "0.3 - LED发光二极管-IR二极管_接收管-光耦") (part "LED"))
    )
    (comp (ref "LED62")
      (value "绿色")
      (footprint "LED0805_B")
      (description "贴片LED")
      (libsource (lib "0.3 - LED发光二极管-IR二极管_接收管-光耦") (part "LED"))
    )
    (comp (ref "LED63")
      (value "绿色")
      (footprint "LED0805_B")
      (description "贴片LED")
      (libsource (lib "0.3 - LED发光二极管-IR二极管_接收管-光耦") (part "LED"))
    )
    (comp (ref "LED64")
      (value "绿色")
      (footprint "LED F257-W - duplicate")
      (description "贴片LED")
      (libsource (lib "0.3 - LED发光二极管-IR二极管_接收管-光耦") (part "LED"))
    )
    (comp (ref "LED65")
      (value "蓝色")
      (footprint "LED F257-W - duplicate")
      (description "贴片LED")
      (libsource (lib "0.3 - LED发光二极管-IR二极管_接收管-光耦") (part "LED"))
    )
    (comp (ref "LED66")
      (value "绿色")
      (footprint "LED0805_B")
      (description "贴片LED")
      (libsource (lib "0.3 - LED发光二极管-IR二极管_接收管-光耦") (part "LED"))
    )
    (comp (ref "LED67")
      (value "绿色")
      (footprint "LED0805_B")
      (description "贴片LED")
      (libsource (lib "0.3 - LED发光二极管-IR二极管_接收管-光耦") (part "LED"))
    )
    (comp (ref "LED68")
      (value "绿色")
      (footprint "LED0805_B")
      (description "贴片LED")
      (libsource (lib "0.3 - LED发光二极管-IR二极管_接收管-光耦") (part "LED"))
    )
    (comp (ref "LED69")
      (value "绿色")
      (footprint "LED0805_B")
      (description "贴片LED")
      (libsource (lib "0.3 - LED发光二极管-IR二极管_接收管-光耦") (part "LED"))
    )
    (comp (ref "LED70")
      (value "绿色")
      (footprint "LED0805_B")
      (description "贴片LED")
      (libsource (lib "0.3 - LED发光二极管-IR二极管_接收管-光耦") (part "LED"))
    )
    (comp (ref "LED71")
      (value "绿色")
      (footprint "LED0805_B")
      (description "贴片LED")
      (libsource (lib "0.3 - LED发光二极管-IR二极管_接收管-光耦") (part "LED"))
    )
    (comp (ref "LED72")
      (value "绿色")
      (footprint "LED0805_B")
      (description "贴片LED")
      (libsource (lib "0.3 - LED发光二极管-IR二极管_接收管-光耦") (part "LED"))
    )
    (comp (ref "LED73")
      (value "绿色")
      (footprint "LED0805_B")
      (description "贴片LED")
      (libsource (lib "0.3 - LED发光二极管-IR二极管_接收管-光耦") (part "LED"))
    )
    (comp (ref "LED74")
      (value "紫色")
      (footprint "LED0805_B")
      (description "贴片LED")
      (libsource (lib "0.3 - LED发光二极管-IR二极管_接收管-光耦") (part "LED"))
    )
    (comp (ref "LED75")
      (value "红色")
      (footprint "LED0805_B")
      (description "贴片LED")
      (libsource (lib "0.3 - LED发光二极管-IR二极管_接收管-光耦") (part "LED"))
    )
    (comp (ref "LED76")
      (value "红色")
      (footprint "LED0805_B")
      (description "贴片LED")
      (libsource (lib "0.3 - LED发光二极管-IR二极管_接收管-光耦") (part "LED"))
    )
    (comp (ref "LED77")
      (value "红色")
      (footprint "LED0805_B")
      (description "贴片LED")
      (libsource (lib "0.3 - LED发光二极管-IR二极管_接收管-光耦") (part "LED"))
    )
    (comp (ref "LED78")
      (value "红色")
      (footprint "LED0805_B")
      (description "贴片LED")
      (libsource (lib "0.3 - LED发光二极管-IR二极管_接收管-光耦") (part "LED"))
    )
    (comp (ref "R1")
      (value "10K")
      (footprint "R0805_L")
      (description "贴片电阻")
      (libsource (lib "0.1 - 电阻-电容-电感-保险丝-晶振-晶体-磁珠-电位器-法拉电容-馈通电容") (part "R"))
    )
    (comp (ref "R2")
      (value "10K")
      (footprint "R0805_L")
      (description "贴片电阻")
      (libsource (lib "0.1 - 电阻-电容-电感-保险丝-晶振-晶体-磁珠-电位器-法拉电容-馈通电容") (part "R"))
    )
    (comp (ref "R3")
      (value "10K")
      (footprint "R0805_L")
      (description "贴片电阻")
      (libsource (lib "0.1 - 电阻-电容-电感-保险丝-晶振-晶体-磁珠-电位器-法拉电容-馈通电容") (part "R"))
    )
    (comp (ref "R4")
      (value "10K")
      (footprint "R0805_L")
      (description "贴片电阻")
      (libsource (lib "0.1 - 电阻-电容-电感-保险丝-晶振-晶体-磁珠-电位器-法拉电容-馈通电容") (part "R"))
    )
    (comp (ref "R5")
      (value "10K")
      (footprint "R0805_L")
      (description "贴片电阻")
      (libsource (lib "0.1 - 电阻-电容-电感-保险丝-晶振-晶体-磁珠-电位器-法拉电容-馈通电容") (part "R"))
    )
    (comp (ref "R6")
      (value "10K")
      (footprint "R0805_L")
      (description "贴片电阻")
      (libsource (lib "0.1 - 电阻-电容-电感-保险丝-晶振-晶体-磁珠-电位器-法拉电容-馈通电容") (part "R"))
    )
    (comp (ref "R7")
      (value "10K")
      (footprint "R0805_L")
      (description "贴片电阻")
      (libsource (lib "0.1 - 电阻-电容-电感-保险丝-晶振-晶体-磁珠-电位器-法拉电容-馈通电容") (part "R"))
    )
    (comp (ref "R8")
      (value "10K")
      (footprint "R0805_L")
      (description "贴片电阻")
      (libsource (lib "0.1 - 电阻-电容-电感-保险丝-晶振-晶体-磁珠-电位器-法拉电容-馈通电容") (part "R"))
    )
    (comp (ref "R9")
      (value "3K9")
      (footprint "R0805_L")
      (description "贴片电阻")
      (libsource (lib "0.1 - 电阻-电容-电感-保险丝-晶振-晶体-磁珠-电位器-法拉电容-馈通电容") (part "R"))
    )
    (comp (ref "R10")
      (value "3K9")
      (footprint "R0805_L")
      (description "贴片电阻")
      (libsource (lib "0.1 - 电阻-电容-电感-保险丝-晶振-晶体-磁珠-电位器-法拉电容-馈通电容") (part "R"))
    )
    (comp (ref "R11")
      (value "3K9")
      (footprint "R0805_L")
      (description "贴片电阻")
      (libsource (lib "0.1 - 电阻-电容-电感-保险丝-晶振-晶体-磁珠-电位器-法拉电容-馈通电容") (part "R"))
    )
    (comp (ref "R12")
      (value "3K9")
      (footprint "R0805_L")
      (description "贴片电阻")
      (libsource (lib "0.1 - 电阻-电容-电感-保险丝-晶振-晶体-磁珠-电位器-法拉电容-馈通电容") (part "R"))
    )
    (comp (ref "R13")
      (value "3K9")
      (footprint "R0805_L")
      (description "贴片电阻")
      (libsource (lib "0.1 - 电阻-电容-电感-保险丝-晶振-晶体-磁珠-电位器-法拉电容-馈通电容") (part "R"))
    )
    (comp (ref "R14")
      (value "3K9")
      (footprint "R0805_L")
      (description "贴片电阻")
      (libsource (lib "0.1 - 电阻-电容-电感-保险丝-晶振-晶体-磁珠-电位器-法拉电容-馈通电容") (part "R"))
    )
    (comp (ref "R15")
      (value "3K9")
      (footprint "R0805_L")
      (description "贴片电阻")
      (libsource (lib "0.1 - 电阻-电容-电感-保险丝-晶振-晶体-磁珠-电位器-法拉电容-馈通电容") (part "R"))
    )
    (comp (ref "R16")
      (value "3K9")
      (footprint "R0805_L")
      (description "贴片电阻")
      (libsource (lib "0.1 - 电阻-电容-电感-保险丝-晶振-晶体-磁珠-电位器-法拉电容-馈通电容") (part "R"))
    )
    (comp (ref "R17")
      (value "3K9")
      (footprint "R0805_L")
      (description "贴片电阻")
      (libsource (lib "0.1 - 电阻-电容-电感-保险丝-晶振-晶体-磁珠-电位器-法拉电容-馈通电容") (part "R"))
    )
    (comp (ref "R18")
      (value "3K9")
      (footprint "R0805_L")
      (description "贴片电阻")
      (libsource (lib "0.1 - 电阻-电容-电感-保险丝-晶振-晶体-磁珠-电位器-法拉电容-馈通电容") (part "R"))
    )
    (comp (ref "R19")
      (value "3K9")
      (footprint "R0805_L")
      (description "贴片电阻")
      (libsource (lib "0.1 - 电阻-电容-电感-保险丝-晶振-晶体-磁珠-电位器-法拉电容-馈通电容") (part "R"))
    )
    (comp (ref "R20")
      (value "3K9")
      (footprint "R0805_L")
      (description "贴片电阻")
      (libsource (lib "0.1 - 电阻-电容-电感-保险丝-晶振-晶体-磁珠-电位器-法拉电容-馈通电容") (part "R"))
    )
    (comp (ref "R21")
      (value "3K9")
      (footprint "R0805_L")
      (description "贴片电阻")
      (libsource (lib "0.1 - 电阻-电容-电感-保险丝-晶振-晶体-磁珠-电位器-法拉电容-馈通电容") (part "R"))
    )
    (comp (ref "R22")
      (value "3K9")
      (footprint "R0805_L")
      (description "贴片电阻")
      (libsource (lib "0.1 - 电阻-电容-电感-保险丝-晶振-晶体-磁珠-电位器-法拉电容-馈通电容") (part "R"))
    )
    (comp (ref "R23")
      (value "3K9")
      (footprint "R0805_L")
      (description "贴片电阻")
      (libsource (lib "0.1 - 电阻-电容-电感-保险丝-晶振-晶体-磁珠-电位器-法拉电容-馈通电容") (part "R"))
    )
    (comp (ref "R24")
      (value "3K9")
      (footprint "R0805_L")
      (description "贴片电阻")
      (libsource (lib "0.1 - 电阻-电容-电感-保险丝-晶振-晶体-磁珠-电位器-法拉电容-馈通电容") (part "R"))
    )
    (comp (ref "R25")
      (value "1K")
      (footprint "R0805_L")
      (description "贴片电阻")
      (libsource (lib "0.1 - 电阻-电容-电感-保险丝-晶振-晶体-磁珠-电位器-法拉电容-馈通电容") (part "R"))
    )
    (comp (ref "R26")
      (value "1K")
      (footprint "R0805_L")
      (description "贴片电阻")
      (libsource (lib "0.1 - 电阻-电容-电感-保险丝-晶振-晶体-磁珠-电位器-法拉电容-馈通电容") (part "R"))
    )
    (comp (ref "R27")
      (value "1K")
      (footprint "R0805_L")
      (description "贴片电阻")
      (libsource (lib "0.1 - 电阻-电容-电感-保险丝-晶振-晶体-磁珠-电位器-法拉电容-馈通电容") (part "R"))
    )
    (comp (ref "R28")
      (value "1K")
      (footprint "R0805_L")
      (description "贴片电阻")
      (libsource (lib "0.1 - 电阻-电容-电感-保险丝-晶振-晶体-磁珠-电位器-法拉电容-馈通电容") (part "R"))
    )
    (comp (ref "R29")
      (value "1K")
      (footprint "R0805_L")
      (description "贴片电阻")
      (libsource (lib "0.1 - 电阻-电容-电感-保险丝-晶振-晶体-磁珠-电位器-法拉电容-馈通电容") (part "R"))
    )
    (comp (ref "R30")
      (value "3K9")
      (footprint "R0805_L")
      (description "贴片电阻")
      (libsource (lib "0.1 - 电阻-电容-电感-保险丝-晶振-晶体-磁珠-电位器-法拉电容-馈通电容") (part "R"))
    )
    (comp (ref "R31")
      (value "1K")
      (footprint "R0805_L")
      (description "贴片电阻")
      (libsource (lib "0.1 - 电阻-电容-电感-保险丝-晶振-晶体-磁珠-电位器-法拉电容-馈通电容") (part "R"))
    )
    (comp (ref "R32")
      (value "1K")
      (footprint "R0805_L")
      (description "贴片电阻")
      (libsource (lib "0.1 - 电阻-电容-电感-保险丝-晶振-晶体-磁珠-电位器-法拉电容-馈通电容") (part "R"))
    )
    (comp (ref "R33")
      (value "3K9")
      (footprint "R0805_L")
      (description "贴片电阻")
      (libsource (lib "0.1 - 电阻-电容-电感-保险丝-晶振-晶体-磁珠-电位器-法拉电容-馈通电容") (part "R"))
    )
    (comp (ref "R34")
      (value "1K")
      (footprint "R0805_L")
      (description "贴片电阻")
      (libsource (lib "0.1 - 电阻-电容-电感-保险丝-晶振-晶体-磁珠-电位器-法拉电容-馈通电容") (part "R"))
    )
    (comp (ref "R35")
      (value "1K")
      (footprint "R0805_L")
      (description "贴片电阻")
      (libsource (lib "0.1 - 电阻-电容-电感-保险丝-晶振-晶体-磁珠-电位器-法拉电容-馈通电容") (part "R"))
    )
    (comp (ref "R36")
      (value "3K9")
      (footprint "R0805_L")
      (description "贴片电阻")
      (libsource (lib "0.1 - 电阻-电容-电感-保险丝-晶振-晶体-磁珠-电位器-法拉电容-馈通电容") (part "R"))
    )
    (comp (ref "R37")
      (value "1K")
      (footprint "R0805_L")
      (description "贴片电阻")
      (libsource (lib "0.1 - 电阻-电容-电感-保险丝-晶振-晶体-磁珠-电位器-法拉电容-馈通电容") (part "R"))
    )
    (comp (ref "R38")
      (value "3K9")
      (footprint "R0805_L")
      (description "贴片电阻")
      (libsource (lib "0.1 - 电阻-电容-电感-保险丝-晶振-晶体-磁珠-电位器-法拉电容-馈通电容") (part "R"))
    )
    (comp (ref "R39")
      (value "1K")
      (footprint "R0805_L")
      (description "贴片电阻")
      (libsource (lib "0.1 - 电阻-电容-电感-保险丝-晶振-晶体-磁珠-电位器-法拉电容-馈通电容") (part "R"))
    )
    (comp (ref "R40")
      (value "1K")
      (footprint "R0805_L")
      (description "贴片电阻")
      (libsource (lib "0.1 - 电阻-电容-电感-保险丝-晶振-晶体-磁珠-电位器-法拉电容-馈通电容") (part "R"))
    )
    (comp (ref "R41")
      (value "1K")
      (footprint "R0805_L")
      (description "贴片电阻")
      (libsource (lib "0.1 - 电阻-电容-电感-保险丝-晶振-晶体-磁珠-电位器-法拉电容-馈通电容") (part "R"))
    )
    (comp (ref "R42")
      (value "820R")
      (footprint "R0805_L")
      (description "贴片电阻")
      (libsource (lib "0.1 - 电阻-电容-电感-保险丝-晶振-晶体-磁珠-电位器-法拉电容-馈通电容") (part "R"))
    )
    (comp (ref "R43")
      (value "820R")
      (footprint "R0805_L")
      (description "贴片电阻")
      (libsource (lib "0.1 - 电阻-电容-电感-保险丝-晶振-晶体-磁珠-电位器-法拉电容-馈通电容") (part "R"))
    )
    (comp (ref "R44")
      (value "1K")
      (footprint "R0805_L")
      (description "贴片电阻")
      (libsource (lib "0.1 - 电阻-电容-电感-保险丝-晶振-晶体-磁珠-电位器-法拉电容-馈通电容") (part "R"))
    )
    (comp (ref "R45")
      (value "1K5")
      (footprint "R0805_L")
      (description "贴片电阻")
      (libsource (lib "0.1 - 电阻-电容-电感-保险丝-晶振-晶体-磁珠-电位器-法拉电容-馈通电容") (part "R"))
    )
    (comp (ref "R46")
      (value "820R")
      (footprint "R0805_L")
      (description "贴片电阻")
      (libsource (lib "0.1 - 电阻-电容-电感-保险丝-晶振-晶体-磁珠-电位器-法拉电容-馈通电容") (part "R"))
    )
    (comp (ref "R47")
      (value "1K")
      (footprint "R0805_L")
      (description "贴片电阻")
      (libsource (lib "0.1 - 电阻-电容-电感-保险丝-晶振-晶体-磁珠-电位器-法拉电容-馈通电容") (part "R"))
    )
    (comp (ref "R48")
      (value "1K")
      (footprint "R0805_L")
      (description "贴片电阻")
      (libsource (lib "0.1 - 电阻-电容-电感-保险丝-晶振-晶体-磁珠-电位器-法拉电容-馈通电容") (part "R"))
    )
    (comp (ref "R49")
      (value "220R")
      (footprint "R0805_L")
      (description "贴片电阻")
      (libsource (lib "0.1 - 电阻-电容-电感-保险丝-晶振-晶体-磁珠-电位器-法拉电容-馈通电容") (part "R"))
    )
    (comp (ref "R50")
      (value "3K9")
      (footprint "R0805_L")
      (description "贴片电阻")
      (libsource (lib "0.1 - 电阻-电容-电感-保险丝-晶振-晶体-磁珠-电位器-法拉电容-馈通电容") (part "R"))
    )
    (comp (ref "R51")
      (value "3K9")
      (footprint "R0805_L")
      (description "贴片电阻")
      (libsource (lib "0.1 - 电阻-电容-电感-保险丝-晶振-晶体-磁珠-电位器-法拉电容-馈通电容") (part "R"))
    )
    (comp (ref "R52")
      (value "3K9")
      (footprint "R0805_L")
      (description "贴片电阻")
      (libsource (lib "0.1 - 电阻-电容-电感-保险丝-晶振-晶体-磁珠-电位器-法拉电容-馈通电容") (part "R"))
    )
    (comp (ref "R53")
      (value "1K")
      (footprint "R0805_L")
      (description "贴片电阻")
      (libsource (lib "0.1 - 电阻-电容-电感-保险丝-晶振-晶体-磁珠-电位器-法拉电容-馈通电容") (part "R"))
    )
    (comp (ref "R54")
      (value "1K")
      (footprint "R0805_L")
      (description "贴片电阻")
      (libsource (lib "0.1 - 电阻-电容-电感-保险丝-晶振-晶体-磁珠-电位器-法拉电容-馈通电容") (part "R"))
    )
    (comp (ref "R55")
      (value "1K")
      (footprint "R0805_L")
      (description "贴片电阻")
      (libsource (lib "0.1 - 电阻-电容-电感-保险丝-晶振-晶体-磁珠-电位器-法拉电容-馈通电容") (part "R"))
    )
    (comp (ref "R56")
      (value "220R")
      (footprint "R0805_L")
      (description "贴片电阻")
      (libsource (lib "0.1 - 电阻-电容-电感-保险丝-晶振-晶体-磁珠-电位器-法拉电容-馈通电容") (part "R"))
    )
    (comp (ref "R57")
      (value "3K9")
      (footprint "R0805_L")
      (description "贴片电阻")
      (libsource (lib "0.1 - 电阻-电容-电感-保险丝-晶振-晶体-磁珠-电位器-法拉电容-馈通电容") (part "R"))
    )
    (comp (ref "R58")
      (value "3K9")
      (footprint "R0805_L")
      (description "贴片电阻")
      (libsource (lib "0.1 - 电阻-电容-电感-保险丝-晶振-晶体-磁珠-电位器-法拉电容-馈通电容") (part "R"))
    )
    (comp (ref "R59")
      (value "3K9")
      (footprint "R0805_L")
      (description "贴片电阻")
      (libsource (lib "0.1 - 电阻-电容-电感-保险丝-晶振-晶体-磁珠-电位器-法拉电容-馈通电容") (part "R"))
    )
    (comp (ref "R60")
      (value "1K")
      (footprint "R0805_L")
      (description "贴片电阻")
      (libsource (lib "0.1 - 电阻-电容-电感-保险丝-晶振-晶体-磁珠-电位器-法拉电容-馈通电容") (part "R"))
    )
    (comp (ref "R61")
      (value "1K")
      (footprint "R0805_L")
      (description "贴片电阻")
      (libsource (lib "0.1 - 电阻-电容-电感-保险丝-晶振-晶体-磁珠-电位器-法拉电容-馈通电容") (part "R"))
    )
    (comp (ref "R62")
      (value "1K")
      (footprint "R0805_L")
      (description "贴片电阻")
      (libsource (lib "0.1 - 电阻-电容-电感-保险丝-晶振-晶体-磁珠-电位器-法拉电容-馈通电容") (part "R"))
    )
    (comp (ref "R63")
      (value "220R")
      (footprint "R0805_L")
      (description "贴片电阻")
      (libsource (lib "0.1 - 电阻-电容-电感-保险丝-晶振-晶体-磁珠-电位器-法拉电容-馈通电容") (part "R"))
    )
    (comp (ref "R64")
      (value "3K9")
      (footprint "R0805_L")
      (description "贴片电阻")
      (libsource (lib "0.1 - 电阻-电容-电感-保险丝-晶振-晶体-磁珠-电位器-法拉电容-馈通电容") (part "R"))
    )
    (comp (ref "R65")
      (value "3K9")
      (footprint "R0805_L")
      (description "贴片电阻")
      (libsource (lib "0.1 - 电阻-电容-电感-保险丝-晶振-晶体-磁珠-电位器-法拉电容-馈通电容") (part "R"))
    )
    (comp (ref "R66")
      (value "3K9")
      (footprint "R0805_L")
      (description "贴片电阻")
      (libsource (lib "0.1 - 电阻-电容-电感-保险丝-晶振-晶体-磁珠-电位器-法拉电容-馈通电容") (part "R"))
    )
    (comp (ref "R67")
      (value "1K")
      (footprint "R0805_L")
      (description "贴片电阻")
      (libsource (lib "0.1 - 电阻-电容-电感-保险丝-晶振-晶体-磁珠-电位器-法拉电容-馈通电容") (part "R"))
    )
    (comp (ref "R68")
      (value "1K")
      (footprint "R0805_L")
      (description "贴片电阻")
      (libsource (lib "0.1 - 电阻-电容-电感-保险丝-晶振-晶体-磁珠-电位器-法拉电容-馈通电容") (part "R"))
    )
    (comp (ref "R69")
      (value "1K")
      (footprint "R0805_L")
      (description "贴片电阻")
      (libsource (lib "0.1 - 电阻-电容-电感-保险丝-晶振-晶体-磁珠-电位器-法拉电容-馈通电容") (part "R"))
    )
    (comp (ref "R70")
      (value "220R")
      (footprint "R0805_L")
      (description "贴片电阻")
      (libsource (lib "0.1 - 电阻-电容-电感-保险丝-晶振-晶体-磁珠-电位器-法拉电容-馈通电容") (part "R"))
    )
    (comp (ref "R71")
      (value "3K9")
      (footprint "R0805_L")
      (description "贴片电阻")
      (libsource (lib "0.1 - 电阻-电容-电感-保险丝-晶振-晶体-磁珠-电位器-法拉电容-馈通电容") (part "R"))
    )
    (comp (ref "R72")
      (value "3K9")
      (footprint "R0805_L")
      (description "贴片电阻")
      (libsource (lib "0.1 - 电阻-电容-电感-保险丝-晶振-晶体-磁珠-电位器-法拉电容-馈通电容") (part "R"))
    )
    (comp (ref "R73")
      (value "3K9")
      (footprint "R0805_L")
      (description "贴片电阻")
      (libsource (lib "0.1 - 电阻-电容-电感-保险丝-晶振-晶体-磁珠-电位器-法拉电容-馈通电容") (part "R"))
    )
    (comp (ref "R74")
      (value "1K")
      (footprint "R0805_L")
      (description "贴片电阻")
      (libsource (lib "0.1 - 电阻-电容-电感-保险丝-晶振-晶体-磁珠-电位器-法拉电容-馈通电容") (part "R"))
    )
    (comp (ref "R75")
      (value "1K")
      (footprint "R0805_L")
      (description "贴片电阻")
      (libsource (lib "0.1 - 电阻-电容-电感-保险丝-晶振-晶体-磁珠-电位器-法拉电容-馈通电容") (part "R"))
    )
    (comp (ref "R76")
      (value "10K")
      (footprint "R0805_L")
      (description "贴片电阻")
      (libsource (lib "0.1 - 电阻-电容-电感-保险丝-晶振-晶体-磁珠-电位器-法拉电容-馈通电容") (part "R"))
    )
    (comp (ref "R77")
      (value "100K")
      (footprint "R0805_L")
      (description "贴片电阻")
      (libsource (lib "0.1 - 电阻-电容-电感-保险丝-晶振-晶体-磁珠-电位器-法拉电容-馈通电容") (part "R"))
    )
    (comp (ref "R78")
      (value "100R")
      (footprint "R0805_L")
      (description "贴片电阻")
      (libsource (lib "0.1 - 电阻-电容-电感-保险丝-晶振-晶体-磁珠-电位器-法拉电容-馈通电容") (part "R"))
    )
    (comp (ref "R79")
      (value "1K")
      (footprint "R0805_L")
      (description "贴片电阻")
      (libsource (lib "0.1 - 电阻-电容-电感-保险丝-晶振-晶体-磁珠-电位器-法拉电容-馈通电容") (part "R"))
    )
    (comp (ref "R80")
      (value "100K")
      (footprint "R0805_L")
      (description "贴片电阻")
      (libsource (lib "0.1 - 电阻-电容-电感-保险丝-晶振-晶体-磁珠-电位器-法拉电容-馈通电容") (part "R"))
    )
    (comp (ref "R81")
      (value "100R")
      (footprint "R0805_L")
      (description "贴片电阻")
      (libsource (lib "0.1 - 电阻-电容-电感-保险丝-晶振-晶体-磁珠-电位器-法拉电容-馈通电容") (part "R"))
    )
    (comp (ref "R82")
      (value "1K")
      (footprint "R0805_L")
      (description "贴片电阻")
      (libsource (lib "0.1 - 电阻-电容-电感-保险丝-晶振-晶体-磁珠-电位器-法拉电容-馈通电容") (part "R"))
    )
    (comp (ref "R83")
      (value "1K")
      (footprint "R0805_L")
      (description "贴片电阻")
      (libsource (lib "0.1 - 电阻-电容-电感-保险丝-晶振-晶体-磁珠-电位器-法拉电容-馈通电容") (part "R"))
    )
    (comp (ref "R84")
      (value "1K")
      (footprint "R0805_L")
      (description "贴片电阻")
      (libsource (lib "0.1 - 电阻-电容-电感-保险丝-晶振-晶体-磁珠-电位器-法拉电容-馈通电容") (part "R"))
    )
    (comp (ref "R85")
      (value "10K")
      (footprint "R0805_L")
      (description "贴片电阻")
      (libsource (lib "0.1 - 电阻-电容-电感-保险丝-晶振-晶体-磁珠-电位器-法拉电容-馈通电容") (part "R"))
    )
    (comp (ref "R86")
      (value "10K")
      (footprint "R0805_L")
      (description "贴片电阻")
      (libsource (lib "0.1 - 电阻-电容-电感-保险丝-晶振-晶体-磁珠-电位器-法拉电容-馈通电容") (part "R"))
    )
    (comp (ref "R87")
      (value "10K")
      (footprint "R0805_L")
      (description "贴片电阻")
      (libsource (lib "0.1 - 电阻-电容-电感-保险丝-晶振-晶体-磁珠-电位器-法拉电容-馈通电容") (part "R"))
    )
    (comp (ref "R88")
      (value "10K")
      (footprint "R0805_L")
      (description "贴片电阻")
      (libsource (lib "0.1 - 电阻-电容-电感-保险丝-晶振-晶体-磁珠-电位器-法拉电容-馈通电容") (part "R"))
    )
    (comp (ref "R89")
      (value "3K9")
      (footprint "R0805_L")
      (description "贴片电阻")
      (libsource (lib "0.1 - 电阻-电容-电感-保险丝-晶振-晶体-磁珠-电位器-法拉电容-馈通电容") (part "R"))
    )
    (comp (ref "R90")
      (value "3K9")
      (footprint "R0805_L")
      (description "贴片电阻")
      (libsource (lib "0.1 - 电阻-电容-电感-保险丝-晶振-晶体-磁珠-电位器-法拉电容-馈通电容") (part "R"))
    )
    (comp (ref "R91")
      (value "3K9")
      (footprint "R0805_L")
      (description "贴片电阻")
      (libsource (lib "0.1 - 电阻-电容-电感-保险丝-晶振-晶体-磁珠-电位器-法拉电容-馈通电容") (part "R"))
    )
    (comp (ref "R92")
      (value "3K9")
      (footprint "R0805_L")
      (description "贴片电阻")
      (libsource (lib "0.1 - 电阻-电容-电感-保险丝-晶振-晶体-磁珠-电位器-法拉电容-馈通电容") (part "R"))
    )
    (comp (ref "R93")
      (value "3K9")
      (footprint "R0805_L")
      (description "贴片电阻")
      (libsource (lib "0.1 - 电阻-电容-电感-保险丝-晶振-晶体-磁珠-电位器-法拉电容-馈通电容") (part "R"))
    )
    (comp (ref "R94")
      (value "3K9")
      (footprint "R0805_L")
      (description "贴片电阻")
      (libsource (lib "0.1 - 电阻-电容-电感-保险丝-晶振-晶体-磁珠-电位器-法拉电容-馈通电容") (part "R"))
    )
    (comp (ref "R95")
      (value "3K9")
      (footprint "R0805_L")
      (description "贴片电阻")
      (libsource (lib "0.1 - 电阻-电容-电感-保险丝-晶振-晶体-磁珠-电位器-法拉电容-馈通电容") (part "R"))
    )
    (comp (ref "R96")
      (value "3K9")
      (footprint "R0805_L")
      (description "贴片电阻")
      (libsource (lib "0.1 - 电阻-电容-电感-保险丝-晶振-晶体-磁珠-电位器-法拉电容-馈通电容") (part "R"))
    )
    (comp (ref "R97")
      (value "1K5")
      (footprint "R0805_L")
      (description "贴片电阻")
      (libsource (lib "0.1 - 电阻-电容-电感-保险丝-晶振-晶体-磁珠-电位器-法拉电容-馈通电容") (part "R"))
    )
    (comp (ref "R98")
      (value "1K")
      (footprint "R0805_L")
      (description "贴片电阻")
      (libsource (lib "0.1 - 电阻-电容-电感-保险丝-晶振-晶体-磁珠-电位器-法拉电容-馈通电容") (part "R"))
    )
    (comp (ref "R99")
      (value "1K")
      (footprint "R0805_L")
      (description "贴片电阻")
      (libsource (lib "0.1 - 电阻-电容-电感-保险丝-晶振-晶体-磁珠-电位器-法拉电容-馈通电容") (part "R"))
    )
    (comp (ref "R100")
      (value "1K")
      (footprint "R0805_L")
      (description "贴片电阻")
      (libsource (lib "0.1 - 电阻-电容-电感-保险丝-晶振-晶体-磁珠-电位器-法拉电容-馈通电容") (part "R"))
    )
    (comp (ref "R101")
      (value "1K")
      (footprint "R0805_L")
      (description "贴片电阻")
      (libsource (lib "0.1 - 电阻-电容-电感-保险丝-晶振-晶体-磁珠-电位器-法拉电容-馈通电容") (part "R"))
    )
    (comp (ref "RP1")
      (value "50K")
      (footprint "XV09223NPV-20F")
      (description "单联电位器")
      (libsource (lib "0.1 - 电阻-电容-电感-保险丝-晶振-晶体-磁珠-电位器-法拉电容-馈通电容") (part "RP"))
    )
    (comp (ref "S1")
      (value "SS-12F23")
      (footprint "SS-12D10")
      (description "1路波动开关")
      (libsource (lib "0.5 - 按键_开关_蜂鸣器_电池_测试点_Mark点_铜柱") (part "SSW-1P"))
    )
    (comp (ref "SW0")
      (value "DIP-SW-8P")
      (footprint "SW DIP-8P-B")
      (description "8路编码开关")
      (libsource (lib "0.5 - 按键_开关_蜂鸣器_电池_测试点_Mark点_铜柱") (part "DIP-SW-8P"))
    )
    (comp (ref "SW1")
      (value "DIP-SW-8P")
      (footprint "SW DIP-8P-B")
      (description "8路编码开关")
      (libsource (lib "0.5 - 按键_开关_蜂鸣器_电池_测试点_Mark点_铜柱") (part "DIP-SW-8P"))
    )
    (comp (ref "SW2")
      (value "DIP-SW-8P")
      (footprint "SW DIP-8P-B")
      (description "8路编码开关")
      (libsource (lib "0.5 - 按键_开关_蜂鸣器_电池_测试点_Mark点_铜柱") (part "DIP-SW-8P"))
    )
    (comp (ref "SW3")
      (value "DIP-SW-8P")
      (footprint "SW DIP-8P-B")
      (description "8路编码开关")
      (libsource (lib "0.5 - 按键_开关_蜂鸣器_电池_测试点_Mark点_铜柱") (part "DIP-SW-8P"))
    )
    (comp (ref "SW4")
      (value "DIP-SW-8P")
      (footprint "SW DIP-8P-B")
      (description "8路编码开关")
      (libsource (lib "0.5 - 按键_开关_蜂鸣器_电池_测试点_Mark点_铜柱") (part "DIP-SW-8P"))
    )
    (comp (ref "SW5")
      (value "DIP-SW-8P")
      (footprint "SW DIP-8P-B")
      (description "8路编码开关")
      (libsource (lib "0.5 - 按键_开关_蜂鸣器_电池_测试点_Mark点_铜柱") (part "DIP-SW-8P"))
    )
    (comp (ref "SW6")
      (value "DIP-SW-8P")
      (footprint "SW DIP-8P-B")
      (description "8路编码开关")
      (libsource (lib "0.5 - 按键_开关_蜂鸣器_电池_测试点_Mark点_铜柱") (part "DIP-SW-8P"))
    )
    (comp (ref "SW7")
      (value "DIP-SW-8P")
      (footprint "SW DIP-8P-B")
      (description "8路编码开关")
      (libsource (lib "0.5 - 按键_开关_蜂鸣器_电池_测试点_Mark点_铜柱") (part "DIP-SW-8P"))
    )
    (comp (ref "SW8")
      (value "DIP-SW-8P")
      (footprint "SW DIP-8P-B")
      (description "8路编码开关")
      (libsource (lib "0.5 - 按键_开关_蜂鸣器_电池_测试点_Mark点_铜柱") (part "DIP-SW-8P"))
    )
    (comp (ref "SW9")
      (value "DIP-SW-8P")
      (footprint "SW DIP-8P-B")
      (description "8路编码开关")
      (libsource (lib "0.5 - 按键_开关_蜂鸣器_电池_测试点_Mark点_铜柱") (part "DIP-SW-8P"))
    )
    (comp (ref "SW10")
      (value "DIP-SW-8P")
      (footprint "SW DIP-8P-B")
      (description "8路编码开关")
      (libsource (lib "0.5 - 按键_开关_蜂鸣器_电池_测试点_Mark点_铜柱") (part "DIP-SW-8P"))
    )
    (comp (ref "SW11")
      (value "DIP-SW-8P")
      (footprint "SW DIP-8P-B")
      (description "8路编码开关")
      (libsource (lib "0.5 - 按键_开关_蜂鸣器_电池_测试点_Mark点_铜柱") (part "DIP-SW-8P"))
    )
    (comp (ref "SW12")
      (value "DIP-SW-8P")
      (footprint "SW DIP-8P-B")
      (description "8路编码开关")
      (libsource (lib "0.5 - 按键_开关_蜂鸣器_电池_测试点_Mark点_铜柱") (part "DIP-SW-8P"))
    )
    (comp (ref "SW13")
      (value "DIP-SW-8P")
      (footprint "SW DIP-8P-B")
      (description "8路编码开关")
      (libsource (lib "0.5 - 按键_开关_蜂鸣器_电池_测试点_Mark点_铜柱") (part "DIP-SW-8P"))
    )
    (comp (ref "SW14")
      (value "DIP-SW-8P")
      (footprint "SW DIP-8P-B")
      (description "8路编码开关")
      (libsource (lib "0.5 - 按键_开关_蜂鸣器_电池_测试点_Mark点_铜柱") (part "DIP-SW-8P"))
    )
    (comp (ref "SW15")
      (value "DIP-SW-8P")
      (footprint "SW DIP-8P-B")
      (description "8路编码开关")
      (libsource (lib "0.5 - 按键_开关_蜂鸣器_电池_测试点_Mark点_铜柱") (part "DIP-SW-8P"))
    )
    (comp (ref "SW16")
      (value "Cherry")
      (footprint "LSW DIP-CHERRY-Hat")
      (description "带灯机械按键开关")
      (libsource (lib "0.5 - 按键_开关_蜂鸣器_电池_测试点_Mark点_铜柱") (part "LSW"))
    )
    (comp (ref "SW17")
      (value "Cherry")
      (footprint "LSW DIP-CHERRY-Hat")
      (description "带灯机械按键开关")
      (libsource (lib "0.5 - 按键_开关_蜂鸣器_电池_测试点_Mark点_铜柱") (part "LSW"))
    )
    (comp (ref "SW18")
      (value "DIP-SW-4P")
      (footprint "SW DIP-4P-B")
      (description "4路编码开关")
      (libsource (lib "0.5 - 按键_开关_蜂鸣器_电池_测试点_Mark点_铜柱") (part "DIP-SW-4P"))
    )
    (comp (ref "U1")
      (value "SN74HC540")
      (footprint "DIP20-300_MH")
      (description "OCTAL BUF AND LINE DRV 3SO")
      (libsource (lib "1.1 - 74系列TTL逻辑芯片") (part "SN74HC540"))
    )
    (comp (ref "U2")
      (value "SN74HC154")
      (footprint "DIP24-300_MH")
      (description "4-16LINE DEC DEMUL")
      (libsource (lib "1.1 - 74系列TTL逻辑芯片") (part "SN74HC154"))
    )
    (comp (ref "U3")
      (value "SN74HC32")
      (footprint "DIP14-300_MH")
      (description "Quad 2-IN Pos Or G")
      (libsource (lib "1.1 - 74系列TTL逻辑芯片") (part "SN74HC32"))
    )
    (comp (ref "U4")
      (value "SN74HC10")
      (footprint "DIP14-300_MH")
      (description "Triple 3-IN Pos Nand G")
      (libsource (lib "1.1 - 74系列TTL逻辑芯片") (part "SN74HC10"))
    )
    (comp (ref "U5")
      (value "SN74HC14")
      (footprint "DIP14-300_MH")
      (description "Hex Inverter SCH")
      (libsource (lib "1.1 - 74系列TTL逻辑芯片") (part "SN74HC14"))
    )
    (comp (ref "U6")
      (value "SN74HC161")
      (footprint "DIP16-300_MH")
      (description "SYN 4-BIT CNT")
      (libsource (lib "1.1 - 74系列TTL逻辑芯片") (part "SN74HC161"))
    )
    (comp (ref "U7")
      (value "SN74HC153")
      (footprint "DIP16-300_MH")
      (description "DUAL 4-1 LINE DATA SELEC/MUX")
      (libsource (lib "1.1 - 74系列TTL逻辑芯片") (part "SN74HC153"))
    )
    (comp (ref "U8")
      (value "SN74HC283")
      (footprint "DIP16-300_MH")
      (description "4-BIT BIN ADD WITH FC")
      (libsource (lib "1.1 - 74系列TTL逻辑芯片") (part "SN74HC283"))
    )
    (comp (ref "U9")
      (value "SN74HC74")
      (footprint "DIP14-300_MH")
      (description "DUAL D PET FF RS CR")
      (libsource (lib "1.1 - 74系列TTL逻辑芯片") (part "SN74HC74"))
    )
    (comp (ref "U10")
      (value "SN74HC161")
      (footprint "DIP16-300_MH")
      (description "SYN 4-BIT CNT")
      (libsource (lib "1.1 - 74系列TTL逻辑芯片") (part "SN74HC161"))
    )
    (comp (ref "U11")
      (value "SN74HC153")
      (footprint "DIP16-300_MH")
      (description "DUAL 4-1 LINE DATA SELEC/MUX")
      (libsource (lib "1.1 - 74系列TTL逻辑芯片") (part "SN74HC153"))
    )
    (comp (ref "U12")
      (value "SN74HC161")
      (footprint "DIP16-300_MH")
      (description "SYN 4-BIT CNT")
      (libsource (lib "1.1 - 74系列TTL逻辑芯片") (part "SN74HC161"))
    )
    (comp (ref "U13")
      (value "SN74HC161")
      (footprint "DIP16-300_MH")
      (description "SYN 4-BIT CNT")
      (libsource (lib "1.1 - 74系列TTL逻辑芯片") (part "SN74HC161"))
    )
    (comp (ref "USB1")
      (value "USB_TYPE-C_6Pin")
      (footprint "USB-C-SMD_6P")
      (description "USB_TYPE-C_6Pin母座")
      (libsource (lib "0.6 - 电源_音频_USB Type-C_HDMI_XT60_5557_D-SUB_RJ45_SD-TF_SIM插座") (part "USB_TYPE-C_6Pin"))
    )
  )
  (nets
    (net (code "1") (name "/ALU_A0") (class "Default")
      (node (ref "LED39") (pin "1") (pinfunction "A_1") (pintype "passive"))
      (node (ref "U7") (pin "7") (pinfunction "1Y_7") (pintype "output"))
      (node (ref "U8") (pin "5") (pinfunction "A1_5") (pintype "input"))
    )
    (net (code "2") (name "/ALU_A1") (class "Default")
      (node (ref "LED46") (pin "1") (pinfunction "A_1") (pintype "passive"))
      (node (ref "U7") (pin "9") (pinfunction "2Y_9") (pintype "output"))
      (node (ref "U8") (pin "3") (pinfunction "A2_3") (pintype "input"))
    )
    (net (code "3") (name "/ALU_A2") (class "Default")
      (node (ref "LED53") (pin "1") (pinfunction "A_1") (pintype "passive"))
      (node (ref "U11") (pin "7") (pinfunction "1Y_7") (pintype "output"))
      (node (ref "U8") (pin "14") (pinfunction "A3_14") (pintype "input"))
    )
    (net (code "4") (name "/ALU_A3") (class "Default")
      (node (ref "LED60") (pin "1") (pinfunction "A_1") (pintype "passive"))
      (node (ref "U11") (pin "9") (pinfunction "2Y_9") (pintype "output"))
      (node (ref "U8") (pin "12") (pinfunction "A4_12") (pintype "input"))
    )
    (net (code "5") (name "/ALU_OUT0") (class "Default")
      (node (ref "LED40") (pin "1") (pinfunction "A_1") (pintype "passive"))
      (node (ref "U10") (pin "3") (pinfunction "A_3") (pintype "input"))
      (node (ref "U12") (pin "3") (pinfunction "A_3") (pintype "input"))
      (node (ref "U13") (pin "3") (pinfunction "A_3") (pintype "input"))
      (node (ref "U6") (pin "3") (pinfunction "A_3") (pintype "input"))
      (node (ref "U8") (pin "4") (pintype "output"))
    )
    (net (code "6") (name "/ALU_OUT1") (class "Default")
      (node (ref "LED47") (pin "1") (pinfunction "A_1") (pintype "passive"))
      (node (ref "U10") (pin "4") (pinfunction "B_4") (pintype "input"))
      (node (ref "U12") (pin "4") (pinfunction "B_4") (pintype "input"))
      (node (ref "U13") (pin "4") (pinfunction "B_4") (pintype "input"))
      (node (ref "U6") (pin "4") (pinfunction "B_4") (pintype "input"))
      (node (ref "U8") (pin "1") (pintype "output"))
    )
    (net (code "7") (name "/ALU_OUT2") (class "Default")
      (node (ref "LED54") (pin "1") (pinfunction "A_1") (pintype "passive"))
      (node (ref "U10") (pin "5") (pinfunction "C_5") (pintype "input"))
      (node (ref "U12") (pin "5") (pinfunction "C_5") (pintype "input"))
      (node (ref "U13") (pin "5") (pinfunction "C_5") (pintype "input"))
      (node (ref "U6") (pin "5") (pinfunction "C_5") (pintype "input"))
      (node (ref "U8") (pin "13") (pintype "output"))
    )
    (net (code "8") (name "/ALU_OUT3") (class "Default")
      (node (ref "LED61") (pin "1") (pinfunction "A_1") (pintype "passive"))
      (node (ref "U10") (pin "6") (pinfunction "D_6") (pintype "input"))
      (node (ref "U12") (pin "6") (pinfunction "D_6") (pintype "input"))
      (node (ref "U13") (pin "6") (pinfunction "D_6") (pintype "input"))
      (node (ref "U6") (pin "6") (pinfunction "D_6") (pintype "input"))
      (node (ref "U8") (pin "10") (pintype "output"))
    )
    (net (code "9") (name "/A_REG_0") (class "Default")
      (node (ref "R50") (pin "2") (pinfunction "2_2") (pintype "passive"))
      (node (ref "U6") (pin "14") (pinfunction "QA_14") (pintype "output"))
      (node (ref "U7") (pin "6") (pinfunction "1CO_6") (pintype "input"))
    )
    (net (code "10") (name "/A_REG_1") (class "Default")
      (node (ref "R57") (pin "2") (pinfunction "2_2") (pintype "passive"))
      (node (ref "U6") (pin "13") (pinfunction "QB_13") (pintype "output"))
      (node (ref "U7") (pin "10") (pinfunction "2CO_10") (pintype "input"))
    )
    (net (code "11") (name "/A_REG_2") (class "Default")
      (node (ref "R64") (pin "2") (pinfunction "2_2") (pintype "passive"))
      (node (ref "U11") (pin "6") (pinfunction "1CO_6") (pintype "input"))
      (node (ref "U6") (pin "12") (pinfunction "QC_12") (pintype "output"))
    )
    (net (code "12") (name "/A_REG_3") (class "Default")
      (node (ref "R71") (pin "2") (pinfunction "2_2") (pintype "passive"))
      (node (ref "U11") (pin "10") (pinfunction "2CO_10") (pintype "input"))
      (node (ref "U6") (pin "11") (pinfunction "QD_11") (pintype "output"))
    )
    (net (code "13") (name "/Addr0") (class "Default")
      (node (ref "R30") (pin "2") (pinfunction "2_2") (pintype "passive"))
      (node (ref "R90") (pin "2") (pinfunction "2_2") (pintype "passive"))
      (node (ref "U13") (pin "14") (pinfunction "QA_14") (pintype "output"))
      (node (ref "U2") (pin "23") (pinfunction "A_23") (pintype "input"))
    )
    (net (code "14") (name "/Addr1") (class "Default")
      (node (ref "R33") (pin "2") (pinfunction "2_2") (pintype "passive"))
      (node (ref "R92") (pin "2") (pinfunction "2_2") (pintype "passive"))
      (node (ref "U13") (pin "13") (pinfunction "QB_13") (pintype "output"))
      (node (ref "U2") (pin "22") (pinfunction "B_22") (pintype "input"))
    )
    (net (code "15") (name "/Addr2") (class "Default")
      (node (ref "R36") (pin "2") (pinfunction "2_2") (pintype "passive"))
      (node (ref "R94") (pin "2") (pinfunction "2_2") (pintype "passive"))
      (node (ref "U13") (pin "12") (pinfunction "QC_12") (pintype "output"))
      (node (ref "U2") (pin "21") (pinfunction "C_21") (pintype "input"))
    )
    (net (code "16") (name "/Addr3") (class "Default")
      (node (ref "R38") (pin "2") (pinfunction "2_2") (pintype "passive"))
      (node (ref "R96") (pin "2") (pinfunction "2_2") (pintype "passive"))
      (node (ref "U13") (pin "11") (pinfunction "QD_11") (pintype "output"))
      (node (ref "U2") (pin "20") (pinfunction "D_20") (pintype "input"))
    )
    (net (code "17") (name "/B_REG_0") (class "Default")
      (node (ref "R51") (pin "2") (pinfunction "2_2") (pintype "passive"))
      (node (ref "U10") (pin "14") (pinfunction "QA_14") (pintype "output"))
      (node (ref "U7") (pin "5") (pinfunction "1C1_5") (pintype "input"))
    )
    (net (code "18") (name "/B_REG_1") (class "Default")
      (node (ref "R58") (pin "2") (pinfunction "2_2") (pintype "passive"))
      (node (ref "U10") (pin "13") (pinfunction "QB_13") (pintype "output"))
      (node (ref "U7") (pin "11") (pinfunction "2C1_11") (pintype "input"))
    )
    (net (code "19") (name "/B_REG_2") (class "Default")
      (node (ref "R65") (pin "2") (pinfunction "2_2") (pintype "passive"))
      (node (ref "U10") (pin "12") (pinfunction "QC_12") (pintype "output"))
      (node (ref "U11") (pin "5") (pinfunction "1C1_5") (pintype "input"))
    )
    (net (code "20") (name "/B_REG_3") (class "Default")
      (node (ref "R72") (pin "2") (pinfunction "2_2") (pintype "passive"))
      (node (ref "U10") (pin "11") (pinfunction "QD_11") (pintype "output"))
      (node (ref "U11") (pin "11") (pinfunction "2C1_11") (pintype "input"))
    )
    (net (code "21") (name "/C") (class "Default")
      (node (ref "LED37") (pin "1") (pinfunction "A_1") (pintype "passive"))
      (node (ref "U8") (pin "9") (pinfunction "C4_9") (pintype "output"))
      (node (ref "U9") (pin "12") (pinfunction "D_12") (pintype "input"))
    )
    (net (code "22") (name "/COM0") (class "Default")
      (node (ref "D1") (pin "2") (pinfunction "K_2") (pintype "passive"))
      (node (ref "D2") (pin "2") (pinfunction "K_2") (pintype "passive"))
      (node (ref "D3") (pin "2") (pinfunction "K_2") (pintype "passive"))
      (node (ref "D4") (pin "2") (pinfunction "K_2") (pintype "passive"))
      (node (ref "D5") (pin "2") (pinfunction "K_2") (pintype "passive"))
      (node (ref "D6") (pin "2") (pinfunction "K_2") (pintype "passive"))
      (node (ref "D7") (pin "2") (pinfunction "K_2") (pintype "passive"))
      (node (ref "D8") (pin "2") (pinfunction "K_2") (pintype "passive"))
      (node (ref "LED0") (pin "2") (pinfunction "K_2") (pintype "passive"))
      (node (ref "U2") (pin "1") (pinfunction "0_1") (pintype "output"))
    )
    (net (code "23") (name "/COM1") (class "Default")
      (node (ref "D10") (pin "2") (pinfunction "K_2") (pintype "passive"))
      (node (ref "D11") (pin "2") (pinfunction "K_2") (pintype "passive"))
      (node (ref "D12") (pin "2") (pinfunction "K_2") (pintype "passive"))
      (node (ref "D13") (pin "2") (pinfunction "K_2") (pintype "passive"))
      (node (ref "D14") (pin "2") (pinfunction "K_2") (pintype "passive"))
      (node (ref "D15") (pin "2") (pinfunction "K_2") (pintype "passive"))
      (node (ref "D16") (pin "2") (pinfunction "K_2") (pintype "passive"))
      (node (ref "D9") (pin "2") (pinfunction "K_2") (pintype "passive"))
      (node (ref "LED1") (pin "2") (pinfunction "K_2") (pintype "passive"))
      (node (ref "U2") (pin "2") (pinfunction "1_2") (pintype "output"))
    )
    (net (code "24") (name "/COM2") (class "Default")
      (node (ref "D17") (pin "2") (pinfunction "K_2") (pintype "passive"))
      (node (ref "D18") (pin "2") (pinfunction "K_2") (pintype "passive"))
      (node (ref "D19") (pin "2") (pinfunction "K_2") (pintype "passive"))
      (node (ref "D20") (pin "2") (pinfunction "K_2") (pintype "passive"))
      (node (ref "D21") (pin "2") (pinfunction "K_2") (pintype "passive"))
      (node (ref "D22") (pin "2") (pinfunction "K_2") (pintype "passive"))
      (node (ref "D23") (pin "2") (pinfunction "K_2") (pintype "passive"))
      (node (ref "D24") (pin "2") (pinfunction "K_2") (pintype "passive"))
      (node (ref "LED2") (pin "2") (pinfunction "K_2") (pintype "passive"))
      (node (ref "U2") (pin "3") (pinfunction "2_3") (pintype "output"))
    )
    (net (code "25") (name "/COM3") (class "Default")
      (node (ref "D25") (pin "2") (pinfunction "K_2") (pintype "passive"))
      (node (ref "D26") (pin "2") (pinfunction "K_2") (pintype "passive"))
      (node (ref "D27") (pin "2") (pinfunction "K_2") (pintype "passive"))
      (node (ref "D28") (pin "2") (pinfunction "K_2") (pintype "passive"))
      (node (ref "D29") (pin "2") (pinfunction "K_2") (pintype "passive"))
      (node (ref "D30") (pin "2") (pinfunction "K_2") (pintype "passive"))
      (node (ref "D31") (pin "2") (pinfunction "K_2") (pintype "passive"))
      (node (ref "D32") (pin "2") (pinfunction "K_2") (pintype "passive"))
      (node (ref "LED3") (pin "2") (pinfunction "K_2") (pintype "passive"))
      (node (ref "U2") (pin "4") (pinfunction "3_4") (pintype "output"))
    )
    (net (code "26") (name "/COM4") (class "Default")
      (node (ref "D33") (pin "2") (pinfunction "K_2") (pintype "passive"))
      (node (ref "D34") (pin "2") (pinfunction "K_2") (pintype "passive"))
      (node (ref "D35") (pin "2") (pinfunction "K_2") (pintype "passive"))
      (node (ref "D36") (pin "2") (pinfunction "K_2") (pintype "passive"))
      (node (ref "D37") (pin "2") (pinfunction "K_2") (pintype "passive"))
      (node (ref "D38") (pin "2") (pinfunction "K_2") (pintype "passive"))
      (node (ref "D39") (pin "2") (pinfunction "K_2") (pintype "passive"))
      (node (ref "D40") (pin "2") (pinfunction "K_2") (pintype "passive"))
      (node (ref "LED4") (pin "2") (pinfunction "K_2") (pintype "passive"))
      (node (ref "U2") (pin "5") (pinfunction "4_5") (pintype "output"))
    )
    (net (code "27") (name "/COM5") (class "Default")
      (node (ref "D41") (pin "2") (pinfunction "K_2") (pintype "passive"))
      (node (ref "D42") (pin "2") (pinfunction "K_2") (pintype "passive"))
      (node (ref "D43") (pin "2") (pinfunction "K_2") (pintype "passive"))
      (node (ref "D44") (pin "2") (pinfunction "K_2") (pintype "passive"))
      (node (ref "D45") (pin "2") (pinfunction "K_2") (pintype "passive"))
      (node (ref "D46") (pin "2") (pinfunction "K_2") (pintype "passive"))
      (node (ref "D47") (pin "2") (pinfunction "K_2") (pintype "passive"))
      (node (ref "D48") (pin "2") (pinfunction "K_2") (pintype "passive"))
      (node (ref "LED5") (pin "2") (pinfunction "K_2") (pintype "passive"))
      (node (ref "U2") (pin "6") (pinfunction "5_6") (pintype "output"))
    )
    (net (code "28") (name "/COM6") (class "Default")
      (node (ref "D49") (pin "2") (pinfunction "K_2") (pintype "passive"))
      (node (ref "D50") (pin "2") (pinfunction "K_2") (pintype "passive"))
      (node (ref "D51") (pin "2") (pinfunction "K_2") (pintype "passive"))
      (node (ref "D52") (pin "2") (pinfunction "K_2") (pintype "passive"))
      (node (ref "D53") (pin "2") (pinfunction "K_2") (pintype "passive"))
      (node (ref "D54") (pin "2") (pinfunction "K_2") (pintype "passive"))
      (node (ref "D55") (pin "2") (pinfunction "K_2") (pintype "passive"))
      (node (ref "D56") (pin "2") (pinfunction "K_2") (pintype "passive"))
      (node (ref "LED6") (pin "2") (pinfunction "K_2") (pintype "passive"))
      (node (ref "U2") (pin "7") (pinfunction "6_7") (pintype "output"))
    )
    (net (code "29") (name "/COM7") (class "Default")
      (node (ref "D57") (pin "2") (pinfunction "K_2") (pintype "passive"))
      (node (ref "D58") (pin "2") (pinfunction "K_2") (pintype "passive"))
      (node (ref "D59") (pin "2") (pinfunction "K_2") (pintype "passive"))
      (node (ref "D60") (pin "2") (pinfunction "K_2") (pintype "passive"))
      (node (ref "D61") (pin "2") (pinfunction "K_2") (pintype "passive"))
      (node (ref "D62") (pin "2") (pinfunction "K_2") (pintype "passive"))
      (node (ref "D63") (pin "2") (pinfunction "K_2") (pintype "passive"))
      (node (ref "D64") (pin "2") (pinfunction "K_2") (pintype "passive"))
      (node (ref "LED7") (pin "2") (pinfunction "K_2") (pintype "passive"))
      (node (ref "U2") (pin "8") (pinfunction "7_8") (pintype "output"))
    )
    (net (code "30") (name "/COM8") (class "Default")
      (node (ref "D65") (pin "2") (pinfunction "K_2") (pintype "passive"))
      (node (ref "D66") (pin "2") (pinfunction "K_2") (pintype "passive"))
      (node (ref "D67") (pin "2") (pinfunction "K_2") (pintype "passive"))
      (node (ref "D68") (pin "2") (pinfunction "K_2") (pintype "passive"))
      (node (ref "D69") (pin "2") (pinfunction "K_2") (pintype "passive"))
      (node (ref "D70") (pin "2") (pinfunction "K_2") (pintype "passive"))
      (node (ref "D71") (pin "2") (pinfunction "K_2") (pintype "passive"))
      (node (ref "D72") (pin "2") (pinfunction "K_2") (pintype "passive"))
      (node (ref "LED8") (pin "2") (pinfunction "K_2") (pintype "passive"))
      (node (ref "U2") (pin "9") (pinfunction "8_9") (pintype "output"))
    )
    (net (code "31") (name "/COM9") (class "Default")
      (node (ref "D73") (pin "2") (pinfunction "K_2") (pintype "passive"))
      (node (ref "D74") (pin "2") (pinfunction "K_2") (pintype "passive"))
      (node (ref "D75") (pin "2") (pinfunction "K_2") (pintype "passive"))
      (node (ref "D76") (pin "2") (pinfunction "K_2") (pintype "passive"))
      (node (ref "D77") (pin "2") (pinfunction "K_2") (pintype "passive"))
      (node (ref "D78") (pin "2") (pinfunction "K_2") (pintype "passive"))
      (node (ref "D79") (pin "2") (pinfunction "K_2") (pintype "passive"))
      (node (ref "D80") (pin "2") (pinfunction "K_2") (pintype "passive"))
      (node (ref "LED9") (pin "2") (pinfunction "K_2") (pintype "passive"))
      (node (ref "U2") (pin "10") (pinfunction "9_10") (pintype "output"))
    )
    (net (code "32") (name "/COM10") (class "Default")
      (node (ref "D81") (pin "2") (pinfunction "K_2") (pintype "passive"))
      (node (ref "D82") (pin "2") (pinfunction "K_2") (pintype "passive"))
      (node (ref "D83") (pin "2") (pinfunction "K_2") (pintype "passive"))
      (node (ref "D84") (pin "2") (pinfunction "K_2") (pintype "passive"))
      (node (ref "D85") (pin "2") (pinfunction "K_2") (pintype "passive"))
      (node (ref "D86") (pin "2") (pinfunction "K_2") (pintype "passive"))
      (node (ref "D87") (pin "2") (pinfunction "K_2") (pintype "passive"))
      (node (ref "D88") (pin "2") (pinfunction "K_2") (pintype "passive"))
      (node (ref "LED10") (pin "2") (pinfunction "K_2") (pintype "passive"))
      (node (ref "U2") (pin "11") (pinfunction "10_11") (pintype "output"))
    )
    (net (code "33") (name "/COM11") (class "Default")
      (node (ref "D89") (pin "2") (pinfunction "K_2") (pintype "passive"))
      (node (ref "D90") (pin "2") (pinfunction "K_2") (pintype "passive"))
      (node (ref "D91") (pin "2") (pinfunction "K_2") (pintype "passive"))
      (node (ref "D92") (pin "2") (pinfunction "K_2") (pintype "passive"))
      (node (ref "D93") (pin "2") (pinfunction "K_2") (pintype "passive"))
      (node (ref "D94") (pin "2") (pinfunction "K_2") (pintype "passive"))
      (node (ref "D95") (pin "2") (pinfunction "K_2") (pintype "passive"))
      (node (ref "D96") (pin "2") (pinfunction "K_2") (pintype "passive"))
      (node (ref "LED11") (pin "2") (pinfunction "K_2") (pintype "passive"))
      (node (ref "U2") (pin "13") (pinfunction "11_13") (pintype "output"))
    )
    (net (code "34") (name "/COM12") (class "Default")
      (node (ref "D100") (pin "2") (pinfunction "K_2") (pintype "passive"))
      (node (ref "D101") (pin "2") (pinfunction "K_2") (pintype "passive"))
      (node (ref "D102") (pin "2") (pinfunction "K_2") (pintype "passive"))
      (node (ref "D103") (pin "2") (pinfunction "K_2") (pintype "passive"))
      (node (ref "D104") (pin "2") (pinfunction "K_2") (pintype "passive"))
      (node (ref "D97") (pin "2") (pinfunction "K_2") (pintype "passive"))
      (node (ref "D98") (pin "2") (pinfunction "K_2") (pintype "passive"))
      (node (ref "D99") (pin "2") (pinfunction "K_2") (pintype "passive"))
      (node (ref "LED12") (pin "2") (pinfunction "K_2") (pintype "passive"))
      (node (ref "U2") (pin "14") (pinfunction "12_14") (pintype "output"))
    )
    (net (code "35") (name "/COM13") (class "Default")
      (node (ref "D105") (pin "2") (pinfunction "K_2") (pintype "passive"))
      (node (ref "D106") (pin "2") (pinfunction "K_2") (pintype "passive"))
      (node (ref "D107") (pin "2") (pinfunction "K_2") (pintype "passive"))
      (node (ref "D108") (pin "2") (pinfunction "K_2") (pintype "passive"))
      (node (ref "D109") (pin "2") (pinfunction "K_2") (pintype "passive"))
      (node (ref "D110") (pin "2") (pinfunction "K_2") (pintype "passive"))
      (node (ref "D111") (pin "2") (pinfunction "K_2") (pintype "passive"))
      (node (ref "D112") (pin "2") (pinfunction "K_2") (pintype "passive"))
      (node (ref "LED13") (pin "2") (pinfunction "K_2") (pintype "passive"))
      (node (ref "U2") (pin "15") (pinfunction "13_15") (pintype "output"))
    )
    (net (code "36") (name "/COM14") (class "Default")
      (node (ref "D113") (pin "2") (pinfunction "K_2") (pintype "passive"))
      (node (ref "D114") (pin "2") (pinfunction "K_2") (pintype "passive"))
      (node (ref "D115") (pin "2") (pinfunction "K_2") (pintype "passive"))
      (node (ref "D116") (pin "2") (pinfunction "K_2") (pintype "passive"))
      (node (ref "D117") (pin "2") (pinfunction "K_2") (pintype "passive"))
      (node (ref "D118") (pin "2") (pinfunction "K_2") (pintype "passive"))
      (node (ref "D119") (pin "2") (pinfunction "K_2") (pintype "passive"))
      (node (ref "D120") (pin "2") (pinfunction "K_2") (pintype "passive"))
      (node (ref "LED14") (pin "2") (pinfunction "K_2") (pintype "passive"))
      (node (ref "U2") (pin "16") (pinfunction "14_16") (pintype "output"))
    )
    (net (code "37") (name "/COM15") (class "Default")
      (node (ref "D121") (pin "2") (pinfunction "K_2") (pintype "passive"))
      (node (ref "D122") (pin "2") (pinfunction "K_2") (pintype "passive"))
      (node (ref "D123") (pin "2") (pinfunction "K_2") (pintype "passive"))
      (node (ref "D124") (pin "2") (pinfunction "K_2") (pintype "passive"))
      (node (ref "D125") (pin "2") (pinfunction "K_2") (pintype "passive"))
      (node (ref "D126") (pin "2") (pinfunction "K_2") (pintype "passive"))
      (node (ref "D127") (pin "2") (pinfunction "K_2") (pintype "passive"))
      (node (ref "D128") (pin "2") (pinfunction "K_2") (pintype "passive"))
      (node (ref "LED15") (pin "2") (pinfunction "K_2") (pintype "passive"))
      (node (ref "U2") (pin "17") (pinfunction "15_17") (pintype "output"))
    )
    (net (code "38") (name "/Data0") (class "Default")
      (node (ref "LED38") (pin "1") (pinfunction "A_1") (pintype "passive"))
      (node (ref "R25") (pin "2") (pinfunction "2_2") (pintype "passive"))
      (node (ref "U1") (pin "18") (pinfunction "Y1_18") (pintype "tri_state"))
      (node (ref "U8") (pin "6") (pinfunction "B1_6") (pintype "input"))
    )
    (net (code "39") (name "/Data1") (class "Default")
      (node (ref "LED45") (pin "1") (pinfunction "A_1") (pintype "passive"))
      (node (ref "R26") (pin "2") (pinfunction "2_2") (pintype "passive"))
      (node (ref "U1") (pin "17") (pinfunction "Y2_17") (pintype "tri_state"))
      (node (ref "U8") (pin "2") (pinfunction "B2_2") (pintype "input"))
    )
    (net (code "40") (name "/Data2") (class "Default")
      (node (ref "LED52") (pin "1") (pinfunction "A_1") (pintype "passive"))
      (node (ref "R28") (pin "2") (pinfunction "2_2") (pintype "passive"))
      (node (ref "U1") (pin "16") (pinfunction "Y3_16") (pintype "tri_state"))
      (node (ref "U8") (pin "15") (pinfunction "B3_15") (pintype "input"))
    )
    (net (code "41") (name "/Data3") (class "Default")
      (node (ref "LED59") (pin "1") (pinfunction "A_1") (pintype "passive"))
      (node (ref "R31") (pin "2") (pinfunction "2_2") (pintype "passive"))
      (node (ref "U1") (pin "15") (pinfunction "Y4_15") (pintype "tri_state"))
      (node (ref "U8") (pin "11") (pinfunction "B4_11") (pintype "input"))
    )
    (net (code "42") (name "/Data4") (class "Default")
      (node (ref "R34") (pin "2") (pinfunction "2_2") (pintype "passive"))
      (node (ref "U1") (pin "14") (pinfunction "Y5_14") (pintype "tri_state"))
      (node (ref "U3") (pin "10") (pintype "input"))
      (node (ref "U3") (pin "12") (pintype "input"))
    )
    (net (code "43") (name "/Data5") (class "Default")
      (node (ref "LED34") (pin "1") (pinfunction "A_1") (pintype "passive"))
      (node (ref "R37") (pin "2") (pinfunction "2_2") (pintype "passive"))
      (node (ref "U1") (pin "13") (pinfunction "Y6_13") (pintype "tri_state"))
      (node (ref "U11") (pin "2") (pinfunction "B_2") (pintype "input"))
      (node (ref "U7") (pin "2") (pinfunction "B_2") (pintype "input"))
    )
    (net (code "44") (name "/Data6") (class "Default")
      (node (ref "R39") (pin "2") (pinfunction "2_2") (pintype "passive"))
      (node (ref "U1") (pin "12") (pinfunction "Y7_12") (pintype "tri_state"))
      (node (ref "U3") (pin "1") (pintype "input"))
      (node (ref "U4") (pin "11") (pintype "input"))
      (node (ref "U4") (pin "13") (pintype "input"))
    )
    (net (code "45") (name "/Data7") (class "Default")
      (node (ref "R40") (pin "2") (pinfunction "2_2") (pintype "passive"))
      (node (ref "U1") (pin "11") (pinfunction "Y8_11") (pintype "tri_state"))
      (node (ref "U3") (pin "13") (pintype "input"))
      (node (ref "U3") (pin "2") (pintype "input"))
      (node (ref "U3") (pin "5") (pintype "input"))
      (node (ref "U4") (pin "10") (pintype "input"))
      (node (ref "U4") (pin "5") (pintype "input"))
    )
    (net (code "46") (name "/IN_0") (class "Default")
      (node (ref "LED44") (pin "1") (pinfunction "A_1") (pintype "passive"))
      (node (ref "R88") (pin "1") (pinfunction "1_1") (pintype "passive"))
      (node (ref "SW18") (pin "5") (pinfunction "5_5") (pintype "passive"))
      (node (ref "U7") (pin "4") (pinfunction "1C2_4") (pintype "input"))
    )
    (net (code "47") (name "/IN_1") (class "Default")
      (node (ref "LED51") (pin "1") (pinfunction "A_1") (pintype "passive"))
      (node (ref "R87") (pin "1") (pinfunction "1_1") (pintype "passive"))
      (node (ref "SW18") (pin "6") (pinfunction "6_6") (pintype "passive"))
      (node (ref "U7") (pin "12") (pinfunction "2C2_12") (pintype "input"))
    )
    (net (code "48") (name "/IN_2") (class "Default")
      (node (ref "LED58") (pin "1") (pinfunction "A_1") (pintype "passive"))
      (node (ref "R86") (pin "1") (pinfunction "1_1") (pintype "passive"))
      (node (ref "SW18") (pin "7") (pinfunction "7_7") (pintype "passive"))
      (node (ref "U11") (pin "4") (pinfunction "1C2_4") (pintype "input"))
    )
    (net (code "49") (name "/IN_3") (class "Default")
      (node (ref "LED65") (pin "1") (pinfunction "A_1") (pintype "passive"))
      (node (ref "R85") (pin "1") (pinfunction "1_1") (pintype "passive"))
      (node (ref "SW18") (pin "8") (pinfunction "8_8") (pintype "passive"))
      (node (ref "U11") (pin "12") (pinfunction "2C2_12") (pintype "input"))
    )
    (net (code "50") (name "/OUT_REG_0") (class "Default")
      (node (ref "LED43") (pin "1") (pinfunction "A_1") (pintype "passive"))
      (node (ref "R89") (pin "2") (pinfunction "2_2") (pintype "passive"))
      (node (ref "U12") (pin "14") (pinfunction "QA_14") (pintype "output"))
    )
    (net (code "51") (name "/OUT_REG_1") (class "Default")
      (node (ref "LED50") (pin "1") (pinfunction "A_1") (pintype "passive"))
      (node (ref "R91") (pin "2") (pinfunction "2_2") (pintype "passive"))
      (node (ref "U12") (pin "13") (pinfunction "QB_13") (pintype "output"))
    )
    (net (code "52") (name "/OUT_REG_2") (class "Default")
      (node (ref "LED57") (pin "1") (pinfunction "A_1") (pintype "passive"))
      (node (ref "R93") (pin "2") (pinfunction "2_2") (pintype "passive"))
      (node (ref "U12") (pin "12") (pinfunction "QC_12") (pintype "output"))
    )
    (net (code "53") (name "/OUT_REG_3") (class "Default")
      (node (ref "LED64") (pin "1") (pinfunction "A_1") (pintype "passive"))
      (node (ref "R95") (pin "2") (pinfunction "2_2") (pintype "passive"))
      (node (ref "U12") (pin "11") (pinfunction "QD_11") (pintype "output"))
    )
    (net (code "54") (name "/SELA") (class "Default")
      (node (ref "LED33") (pin "1") (pinfunction "A_1") (pintype "passive"))
      (node (ref "U11") (pin "14") (pinfunction "A_14") (pintype "input"))
      (node (ref "U3") (pin "11") (pintype "output"))
      (node (ref "U7") (pin "14") (pinfunction "A_14") (pintype "input"))
    )
    (net (code "55") (name "/SYS_CLK") (class "Default")
      (node (ref "LED35") (pin "1") (pinfunction "A_1") (pintype "passive"))
      (node (ref "S1") (pin "2") (pinfunction "2_2") (pintype "passive"))
      (node (ref "U10") (pin "2") (pinfunction "CLK_2") (pintype "input"))
      (node (ref "U12") (pin "2") (pinfunction "CLK_2") (pintype "input"))
      (node (ref "U13") (pin "2") (pinfunction "CLK_2") (pintype "input"))
      (node (ref "U6") (pin "2") (pinfunction "CLK_2") (pintype "input"))
      (node (ref "U9") (pin "11") (pinfunction "CLK_11") (pintype "input"))
    )
    (net (code "56") (name "/SYS_RST") (class "Default")
      (node (ref "LED36") (pin "2") (pinfunction "K_2") (pintype "passive"))
      (node (ref "U10") (pin "1") (pinfunction "~{CLR}_1") (pintype "input"))
      (node (ref "U12") (pin "1") (pinfunction "~{CLR}_1") (pintype "input"))
      (node (ref "U13") (pin "1") (pinfunction "~{CLR}_1") (pintype "input"))
      (node (ref "U5") (pin "12") (pintype "output"))
      (node (ref "U6") (pin "1") (pinfunction "~{CLR}_1") (pintype "input"))
      (node (ref "U9") (pin "13") (pinfunction "~{CLR}_13") (pintype "input"))
    )
    (net (code "57") (name "/~{C}") (class "Default")
      (node (ref "LED32") (pin "2") (pinfunction "K_2") (pintype "passive"))
      (node (ref "U3") (pin "9") (pintype "input"))
      (node (ref "U9") (pin "8") (pinfunction "~{Q}_8") (pintype "output"))
    )
    (net (code "58") (name "/~{Load0}") (class "Default")
      (node (ref "LED18") (pin "2") (pinfunction "K_2") (pintype "passive"))
      (node (ref "LED75") (pin "2") (pinfunction "K_2") (pintype "passive"))
      (node (ref "U3") (pin "3") (pintype "output"))
      (node (ref "U6") (pin "9") (pinfunction "~{LOAD}_9") (pintype "input"))
    )
    (net (code "59") (name "/~{Load1}") (class "Default")
      (node (ref "LED20") (pin "2") (pinfunction "K_2") (pintype "passive"))
      (node (ref "LED76") (pin "2") (pinfunction "K_2") (pintype "passive"))
      (node (ref "U10") (pin "9") (pinfunction "~{LOAD}_9") (pintype "input"))
      (node (ref "U3") (pin "6") (pintype "output"))
    )
    (net (code "60") (name "/~{Load2}") (class "Default")
      (node (ref "LED23") (pin "2") (pinfunction "K_2") (pintype "passive"))
      (node (ref "LED77") (pin "2") (pinfunction "K_2") (pintype "passive"))
      (node (ref "U12") (pin "9") (pinfunction "~{LOAD}_9") (pintype "input"))
      (node (ref "U4") (pin "6") (pintype "output"))
    )
    (net (code "61") (name "/~{Load3}") (class "Default")
      (node (ref "LED26") (pin "2") (pinfunction "K_2") (pintype "passive"))
      (node (ref "LED78") (pin "2") (pinfunction "K_2") (pintype "passive"))
      (node (ref "U13") (pin "9") (pinfunction "~{LOAD}_9") (pintype "input"))
      (node (ref "U4") (pin "8") (pintype "output"))
    )
    (net (code "62") (name "GND") (class "Default")
      (node (ref "C1") (pin "1") (pinfunction "1_1") (pintype "passive"))
      (node (ref "C10") (pin "1") (pinfunction "1_1") (pintype "passive"))
      (node (ref "C11") (pin "1") (pinfunction "1_1") (pintype "passive"))
      (node (ref "C12") (pin "1") (pinfunction "1_1") (pintype "passive"))
      (node (ref "C13") (pin "1") (pinfunction "1_1") (pintype "passive"))
      (node (ref "C14") (pin "1") (pinfunction "1_1") (pintype "passive"))
      (node (ref "C15") (pin "1") (pinfunction "1_1") (pintype "passive"))
      (node (ref "C16") (pin "1") (pinfunction "1_1") (pintype "passive"))
      (node (ref "C18") (pin "1") (pinfunction "1_1") (pintype "passive"))
      (node (ref "C2") (pin "1") (pinfunction "1_1") (pintype "passive"))
      (node (ref "C3") (pin "1") (pinfunction "1_1") (pintype "passive"))
      (node (ref "C4") (pin "1") (pinfunction "1_1") (pintype "passive"))
      (node (ref "C5") (pin "1") (pinfunction "1_1") (pintype "passive"))
      (node (ref "C6") (pin "1") (pinfunction "1_1") (pintype "passive"))
      (node (ref "C7") (pin "1") (pinfunction "1_1") (pintype "passive"))
      (node (ref "C8") (pin "1") (pinfunction "1_1") (pintype "passive"))
      (node (ref "C9") (pin "1") (pinfunction "1_1") (pintype "passive"))
      (node (ref "LED16") (pin "2") (pinfunction "K_2") (pintype "passive"))
      (node (ref "LED17") (pin "2") (pinfunction "K_2") (pintype "passive"))
      (node (ref "LED19") (pin "2") (pinfunction "K_2") (pintype "passive"))
      (node (ref "LED21") (pin "2") (pinfunction "K_2") (pintype "passive"))
      (node (ref "LED22") (pin "2") (pinfunction "K_2") (pintype "passive"))
      (node (ref "LED24") (pin "2") (pinfunction "K_2") (pintype "passive"))
      (node (ref "LED25") (pin "2") (pinfunction "K_2") (pintype "passive"))
      (node (ref "LED27") (pin "2") (pinfunction "K_2") (pintype "passive"))
      (node (ref "LED28") (pin "2") (pinfunction "K_2") (pintype "passive"))
      (node (ref "LED29") (pin "2") (pinfunction "K_2") (pintype "passive"))
      (node (ref "LED30") (pin "2") (pinfunction "K_2") (pintype "passive"))
      (node (ref "LED31") (pin "2") (pinfunction "K_2") (pintype "passive"))
      (node (ref "LED41") (pin "2") (pinfunction "K_2") (pintype "passive"))
      (node (ref "LED42") (pin "2") (pinfunction "K_2") (pintype "passive"))
      (node (ref "LED48") (pin "2") (pinfunction "K_2") (pintype "passive"))
      (node (ref "LED49") (pin "2") (pinfunction "K_2") (pintype "passive"))
      (node (ref "LED55") (pin "2") (pinfunction "K_2") (pintype "passive"))
      (node (ref "LED56") (pin "2") (pinfunction "K_2") (pintype "passive"))
      (node (ref "LED62") (pin "2") (pinfunction "K_2") (pintype "passive"))
      (node (ref "LED63") (pin "2") (pinfunction "K_2") (pintype "passive"))
      (node (ref "LED66") (pin "2") (pinfunction "K_2") (pintype "passive"))
      (node (ref "LED67") (pin "2") (pinfunction "K_2") (pintype "passive"))
      (node (ref "LED68") (pin "2") (pinfunction "K_2") (pintype "passive"))
      (node (ref "LED69") (pin "2") (pinfunction "K_2") (pintype "passive"))
      (node (ref "LED70") (pin "2") (pinfunction "K_2") (pintype "passive"))
      (node (ref "LED71") (pin "2") (pinfunction "K_2") (pintype "passive"))
      (node (ref "LED72") (pin "2") (pinfunction "K_2") (pintype "passive"))
      (node (ref "LED73") (pin "2") (pinfunction "K_2") (pintype "passive"))
      (node (ref "R42") (pin "1") (pinfunction "1_1") (pintype "passive"))
      (node (ref "R43") (pin "1") (pinfunction "1_1") (pintype "passive"))
      (node (ref "R44") (pin "1") (pinfunction "1_1") (pintype "passive"))
      (node (ref "R46") (pin "1") (pinfunction "1_1") (pintype "passive"))
      (node (ref "R47") (pin "1") (pinfunction "1_1") (pintype "passive"))
      (node (ref "R48") (pin "1") (pinfunction "1_1") (pintype "passive"))
      (node (ref "R49") (pin "1") (pinfunction "1_1") (pintype "passive"))
      (node (ref "R52") (pin "1") (pinfunction "1_1") (pintype "passive"))
      (node (ref "R53") (pin "1") (pinfunction "1_1") (pintype "passive"))
      (node (ref "R54") (pin "1") (pinfunction "1_1") (pintype "passive"))
      (node (ref "R55") (pin "1") (pinfunction "1_1") (pintype "passive"))
      (node (ref "R56") (pin "1") (pinfunction "1_1") (pintype "passive"))
      (node (ref "R59") (pin "1") (pinfunction "1_1") (pintype "passive"))
      (node (ref "R60") (pin "1") (pinfunction "1_1") (pintype "passive"))
      (node (ref "R61") (pin "1") (pinfunction "1_1") (pintype "passive"))
      (node (ref "R62") (pin "1") (pinfunction "1_1") (pintype "passive"))
      (node (ref "R63") (pin "1") (pinfunction "1_1") (pintype "passive"))
      (node (ref "R66") (pin "1") (pinfunction "1_1") (pintype "passive"))
      (node (ref "R67") (pin "1") (pinfunction "1_1") (pintype "passive"))
      (node (ref "R68") (pin "1") (pinfunction "1_1") (pintype "passive"))
      (node (ref "R69") (pin "1") (pinfunction "1_1") (pintype "passive"))
      (node (ref "R70") (pin "1") (pinfunction "1_1") (pintype "passive"))
      (node (ref "R73") (pin "1") (pinfunction "1_1") (pintype "passive"))
      (node (ref "R74") (pin "1") (pinfunction "1_1") (pintype "passive"))
      (node (ref "R85") (pin "2") (pinfunction "2_2") (pintype "passive"))
      (node (ref "R86") (pin "2") (pinfunction "2_2") (pintype "passive"))
      (node (ref "R87") (pin "2") (pinfunction "2_2") (pintype "passive"))
      (node (ref "R88") (pin "2") (pinfunction "2_2") (pintype "passive"))
      (node (ref "R97") (pin "1") (pinfunction "1_1") (pintype "passive"))
      (node (ref "SW16") (pin "2") (pinfunction "K_2") (pintype "passive"))
      (node (ref "SW17") (pin "2") (pinfunction "K_2") (pintype "passive"))
      (node (ref "U1") (pin "1") (pinfunction "~{G}1_1") (pintype "input"))
      (node (ref "U1") (pin "10") (pinfunction "GND_10") (pintype "power_in"))
      (node (ref "U1") (pin "19") (pinfunction "~{G}2_19") (pintype "input"))
      (node (ref "U10") (pin "10") (pinfunction "ENT_10") (pintype "input"))
      (node (ref "U10") (pin "7") (pinfunction "ENP_7") (pintype "input"))
      (node (ref "U10") (pin "8") (pinfunction "GND_8") (pintype "power_in"))
      (node (ref "U11") (pin "1") (pinfunction "1~{G}_1") (pintype "input"))
      (node (ref "U11") (pin "13") (pinfunction "2C3_13") (pintype "input"))
      (node (ref "U11") (pin "15") (pinfunction "2~{G}_15") (pintype "input"))
      (node (ref "U11") (pin "3") (pinfunction "1C3_3") (pintype "input"))
      (node (ref "U11") (pin "8") (pinfunction "GND_8") (pintype "power_in"))
      (node (ref "U12") (pin "10") (pinfunction "ENT_10") (pintype "input"))
      (node (ref "U12") (pin "7") (pinfunction "ENP_7") (pintype "input"))
      (node (ref "U12") (pin "8") (pinfunction "GND_8") (pintype "power_in"))
      (node (ref "U13") (pin "8") (pinfunction "GND_8") (pintype "power_in"))
      (node (ref "U2") (pin "12") (pinfunction "GND_12") (pintype "power_in"))
      (node (ref "U2") (pin "18") (pinfunction "~{G}1_18") (pintype "input"))
      (node (ref "U2") (pin "19") (pinfunction "~{G}2_19") (pintype "input"))
      (node (ref "U3") (pin "7") (pinfunction "GND_7") (pintype "power_in"))
      (node (ref "U4") (pin "7") (pinfunction "GND_7") (pintype "power_in"))
      (node (ref "U5") (pin "1") (pintype "input"))
      (node (ref "U5") (pin "7") (pinfunction "GND_7") (pintype "power_in"))
      (node (ref "U6") (pin "10") (pinfunction "ENT_10") (pintype "input"))
      (node (ref "U6") (pin "7") (pinfunction "ENP_7") (pintype "input"))
      (node (ref "U6") (pin "8") (pinfunction "GND_8") (pintype "power_in"))
      (node (ref "U7") (pin "1") (pinfunction "1~{G}_1") (pintype "input"))
      (node (ref "U7") (pin "13") (pinfunction "2C3_13") (pintype "input"))
      (node (ref "U7") (pin "15") (pinfunction "2~{G}_15") (pintype "input"))
      (node (ref "U7") (pin "3") (pinfunction "1C3_3") (pintype "input"))
      (node (ref "U7") (pin "8") (pinfunction "GND_8") (pintype "power_in"))
      (node (ref "U8") (pin "7") (pinfunction "CO_7") (pintype "input"))
      (node (ref "U8") (pin "8") (pinfunction "GND_8") (pintype "power_in"))
      (node (ref "U9") (pin "2") (pinfunction "D_2") (pintype "input"))
      (node (ref "U9") (pin "3") (pinfunction "CLK_3") (pintype "input"))
      (node (ref "U9") (pin "7") (pinfunction "GND_7") (pintype "power_in"))
      (node (ref "USB1") (pin "0") (pinfunction "GND_0") (pintype "passive"))
      (node (ref "USB1") (pin "A12") (pinfunction "GND_A12") (pintype "passive"))
      (node (ref "USB1") (pin "B12") (pinfunction "GND_B12") (pintype "passive"))
    )
    (net (code "63") (name "Net-(C16-Pad2)") (class "Default")
      (node (ref "C16") (pin "2") (pinfunction "2_2") (pintype "passive"))
      (node (ref "R76") (pin "2") (pinfunction "2_2") (pintype "passive"))
      (node (ref "R77") (pin "1") (pinfunction "1_1") (pintype "passive"))
    )
    (net (code "64") (name "Net-(C17-Pad1)") (class "Default")
      (node (ref "C17") (pin "1") (pinfunction "1_1") (pintype "passive"))
      (node (ref "R81") (pin "1") (pinfunction "1_1") (pintype "passive"))
      (node (ref "U5") (pin "8") (pintype "output"))
    )
    (net (code "65") (name "Net-(C17-Pad2)") (class "Default")
      (node (ref "C17") (pin "2") (pinfunction "2_2") (pintype "passive"))
      (node (ref "R80") (pin "1") (pinfunction "1_1") (pintype "passive"))
      (node (ref "RP1") (pin "2") (pinfunction "2_2") (pintype "passive"))
    )
    (net (code "66") (name "Net-(C18-Pad2)") (class "Default")
      (node (ref "C18") (pin "2") (pinfunction "2_2") (pintype "passive"))
      (node (ref "R83") (pin "2") (pinfunction "2_2") (pintype "passive"))
      (node (ref "R84") (pin "1") (pinfunction "1_1") (pintype "passive"))
    )
    (net (code "67") (name "Net-(D1-A)") (class "Default")
      (node (ref "D1") (pin "1") (pinfunction "A_1") (pintype "passive"))
      (node (ref "SW0") (pin "1") (pinfunction "1_1") (pintype "passive"))
    )
    (net (code "68") (name "Net-(D2-A)") (class "Default")
      (node (ref "D2") (pin "1") (pinfunction "A_1") (pintype "passive"))
      (node (ref "SW0") (pin "2") (pinfunction "2_2") (pintype "passive"))
    )
    (net (code "69") (name "Net-(D3-A)") (class "Default")
      (node (ref "D3") (pin "1") (pinfunction "A_1") (pintype "passive"))
      (node (ref "SW0") (pin "3") (pinfunction "3_3") (pintype "passive"))
    )
    (net (code "70") (name "Net-(D4-A)") (class "Default")
      (node (ref "D4") (pin "1") (pinfunction "A_1") (pintype "passive"))
      (node (ref "SW0") (pin "4") (pinfunction "4_4") (pintype "passive"))
    )
    (net (code "71") (name "Net-(D5-A)") (class "Default")
      (node (ref "D5") (pin "1") (pinfunction "A_1") (pintype "passive"))
      (node (ref "SW0") (pin "5") (pinfunction "5_5") (pintype "passive"))
    )
    (net (code "72") (name "Net-(D6-A)") (class "Default")
      (node (ref "D6") (pin "1") (pinfunction "A_1") (pintype "passive"))
      (node (ref "SW0") (pin "6") (pinfunction "6_6") (pintype "passive"))
    )
    (net (code "73") (name "Net-(D7-A)") (class "Default")
      (node (ref "D7") (pin "1") (pinfunction "A_1") (pintype "passive"))
      (node (ref "SW0") (pin "7") (pinfunction "7_7") (pintype "passive"))
    )
    (net (code "74") (name "Net-(D8-A)") (class "Default")
      (node (ref "D8") (pin "1") (pinfunction "A_1") (pintype "passive"))
      (node (ref "SW0") (pin "8") (pinfunction "8_8") (pintype "passive"))
    )
    (net (code "75") (name "Net-(D9-A)") (class "Default")
      (node (ref "D9") (pin "1") (pinfunction "A_1") (pintype "passive"))
      (node (ref "SW1") (pin "1") (pinfunction "1_1") (pintype "passive"))
    )
    (net (code "76") (name "Net-(D10-A)") (class "Default")
      (node (ref "D10") (pin "1") (pinfunction "A_1") (pintype "passive"))
      (node (ref "SW1") (pin "2") (pinfunction "2_2") (pintype "passive"))
    )
    (net (code "77") (name "Net-(D11-A)") (class "Default")
      (node (ref "D11") (pin "1") (pinfunction "A_1") (pintype "passive"))
      (node (ref "SW1") (pin "3") (pinfunction "3_3") (pintype "passive"))
    )
    (net (code "78") (name "Net-(D12-A)") (class "Default")
      (node (ref "D12") (pin "1") (pinfunction "A_1") (pintype "passive"))
      (node (ref "SW1") (pin "4") (pinfunction "4_4") (pintype "passive"))
    )
    (net (code "79") (name "Net-(D13-A)") (class "Default")
      (node (ref "D13") (pin "1") (pinfunction "A_1") (pintype "passive"))
      (node (ref "SW1") (pin "5") (pinfunction "5_5") (pintype "passive"))
    )
    (net (code "80") (name "Net-(D14-A)") (class "Default")
      (node (ref "D14") (pin "1") (pinfunction "A_1") (pintype "passive"))
      (node (ref "SW1") (pin "6") (pinfunction "6_6") (pintype "passive"))
    )
    (net (code "81") (name "Net-(D15-A)") (class "Default")
      (node (ref "D15") (pin "1") (pinfunction "A_1") (pintype "passive"))
      (node (ref "SW1") (pin "7") (pinfunction "7_7") (pintype "passive"))
    )
    (net (code "82") (name "Net-(D16-A)") (class "Default")
      (node (ref "D16") (pin "1") (pinfunction "A_1") (pintype "passive"))
      (node (ref "SW1") (pin "8") (pinfunction "8_8") (pintype "passive"))
    )
    (net (code "83") (name "Net-(D17-A)") (class "Default")
      (node (ref "D17") (pin "1") (pinfunction "A_1") (pintype "passive"))
      (node (ref "SW2") (pin "1") (pinfunction "1_1") (pintype "passive"))
    )
    (net (code "84") (name "Net-(D18-A)") (class "Default")
      (node (ref "D18") (pin "1") (pinfunction "A_1") (pintype "passive"))
      (node (ref "SW2") (pin "2") (pinfunction "2_2") (pintype "passive"))
    )
    (net (code "85") (name "Net-(D19-A)") (class "Default")
      (node (ref "D19") (pin "1") (pinfunction "A_1") (pintype "passive"))
      (node (ref "SW2") (pin "3") (pinfunction "3_3") (pintype "passive"))
    )
    (net (code "86") (name "Net-(D20-A)") (class "Default")
      (node (ref "D20") (pin "1") (pinfunction "A_1") (pintype "passive"))
      (node (ref "SW2") (pin "4") (pinfunction "4_4") (pintype "passive"))
    )
    (net (code "87") (name "Net-(D21-A)") (class "Default")
      (node (ref "D21") (pin "1") (pinfunction "A_1") (pintype "passive"))
      (node (ref "SW2") (pin "5") (pinfunction "5_5") (pintype "passive"))
    )
    (net (code "88") (name "Net-(D22-A)") (class "Default")
      (node (ref "D22") (pin "1") (pinfunction "A_1") (pintype "passive"))
      (node (ref "SW2") (pin "6") (pinfunction "6_6") (pintype "passive"))
    )
    (net (code "89") (name "Net-(D23-A)") (class "Default")
      (node (ref "D23") (pin "1") (pinfunction "A_1") (pintype "passive"))
      (node (ref "SW2") (pin "7") (pinfunction "7_7") (pintype "passive"))
    )
    (net (code "90") (name "Net-(D24-A)") (class "Default")
      (node (ref "D24") (pin "1") (pinfunction "A_1") (pintype "passive"))
      (node (ref "SW2") (pin "8") (pinfunction "8_8") (pintype "passive"))
    )
    (net (code "91") (name "Net-(D25-A)") (class "Default")
      (node (ref "D25") (pin "1") (pinfunction "A_1") (pintype "passive"))
      (node (ref "SW3") (pin "1") (pinfunction "1_1") (pintype "passive"))
    )
    (net (code "92") (name "Net-(D26-A)") (class "Default")
      (node (ref "D26") (pin "1") (pinfunction "A_1") (pintype "passive"))
      (node (ref "SW3") (pin "2") (pinfunction "2_2") (pintype "passive"))
    )
    (net (code "93") (name "Net-(D27-A)") (class "Default")
      (node (ref "D27") (pin "1") (pinfunction "A_1") (pintype "passive"))
      (node (ref "SW3") (pin "3") (pinfunction "3_3") (pintype "passive"))
    )
    (net (code "94") (name "Net-(D28-A)") (class "Default")
      (node (ref "D28") (pin "1") (pinfunction "A_1") (pintype "passive"))
      (node (ref "SW3") (pin "4") (pinfunction "4_4") (pintype "passive"))
    )
    (net (code "95") (name "Net-(D29-A)") (class "Default")
      (node (ref "D29") (pin "1") (pinfunction "A_1") (pintype "passive"))
      (node (ref "SW3") (pin "5") (pinfunction "5_5") (pintype "passive"))
    )
    (net (code "96") (name "Net-(D30-A)") (class "Default")
      (node (ref "D30") (pin "1") (pinfunction "A_1") (pintype "passive"))
      (node (ref "SW3") (pin "6") (pinfunction "6_6") (pintype "passive"))
    )
    (net (code "97") (name "Net-(D31-A)") (class "Default")
      (node (ref "D31") (pin "1") (pinfunction "A_1") (pintype "passive"))
      (node (ref "SW3") (pin "7") (pinfunction "7_7") (pintype "passive"))
    )
    (net (code "98") (name "Net-(D32-A)") (class "Default")
      (node (ref "D32") (pin "1") (pinfunction "A_1") (pintype "passive"))
      (node (ref "SW3") (pin "8") (pinfunction "8_8") (pintype "passive"))
    )
    (net (code "99") (name "Net-(D33-A)") (class "Default")
      (node (ref "D33") (pin "1") (pinfunction "A_1") (pintype "passive"))
      (node (ref "SW4") (pin "1") (pinfunction "1_1") (pintype "passive"))
    )
    (net (code "100") (name "Net-(D34-A)") (class "Default")
      (node (ref "D34") (pin "1") (pinfunction "A_1") (pintype "passive"))
      (node (ref "SW4") (pin "2") (pinfunction "2_2") (pintype "passive"))
    )
    (net (code "101") (name "Net-(D35-A)") (class "Default")
      (node (ref "D35") (pin "1") (pinfunction "A_1") (pintype "passive"))
      (node (ref "SW4") (pin "3") (pinfunction "3_3") (pintype "passive"))
    )
    (net (code "102") (name "Net-(D36-A)") (class "Default")
      (node (ref "D36") (pin "1") (pinfunction "A_1") (pintype "passive"))
      (node (ref "SW4") (pin "4") (pinfunction "4_4") (pintype "passive"))
    )
    (net (code "103") (name "Net-(D37-A)") (class "Default")
      (node (ref "D37") (pin "1") (pinfunction "A_1") (pintype "passive"))
      (node (ref "SW4") (pin "5") (pinfunction "5_5") (pintype "passive"))
    )
    (net (code "104") (name "Net-(D38-A)") (class "Default")
      (node (ref "D38") (pin "1") (pinfunction "A_1") (pintype "passive"))
      (node (ref "SW4") (pin "6") (pinfunction "6_6") (pintype "passive"))
    )
    (net (code "105") (name "Net-(D39-A)") (class "Default")
      (node (ref "D39") (pin "1") (pinfunction "A_1") (pintype "passive"))
      (node (ref "SW4") (pin "7") (pinfunction "7_7") (pintype "passive"))
    )
    (net (code "106") (name "Net-(D40-A)") (class "Default")
      (node (ref "D40") (pin "1") (pinfunction "A_1") (pintype "passive"))
      (node (ref "SW4") (pin "8") (pinfunction "8_8") (pintype "passive"))
    )
    (net (code "107") (name "Net-(D41-A)") (class "Default")
      (node (ref "D41") (pin "1") (pinfunction "A_1") (pintype "passive"))
      (node (ref "SW5") (pin "1") (pinfunction "1_1") (pintype "passive"))
    )
    (net (code "108") (name "Net-(D42-A)") (class "Default")
      (node (ref "D42") (pin "1") (pinfunction "A_1") (pintype "passive"))
      (node (ref "SW5") (pin "2") (pinfunction "2_2") (pintype "passive"))
    )
    (net (code "109") (name "Net-(D43-A)") (class "Default")
      (node (ref "D43") (pin "1") (pinfunction "A_1") (pintype "passive"))
      (node (ref "SW5") (pin "3") (pinfunction "3_3") (pintype "passive"))
    )
    (net (code "110") (name "Net-(D44-A)") (class "Default")
      (node (ref "D44") (pin "1") (pinfunction "A_1") (pintype "passive"))
      (node (ref "SW5") (pin "4") (pinfunction "4_4") (pintype "passive"))
    )
    (net (code "111") (name "Net-(D45-A)") (class "Default")
      (node (ref "D45") (pin "1") (pinfunction "A_1") (pintype "passive"))
      (node (ref "SW5") (pin "5") (pinfunction "5_5") (pintype "passive"))
    )
    (net (code "112") (name "Net-(D46-A)") (class "Default")
      (node (ref "D46") (pin "1") (pinfunction "A_1") (pintype "passive"))
      (node (ref "SW5") (pin "6") (pinfunction "6_6") (pintype "passive"))
    )
    (net (code "113") (name "Net-(D47-A)") (class "Default")
      (node (ref "D47") (pin "1") (pinfunction "A_1") (pintype "passive"))
      (node (ref "SW5") (pin "7") (pinfunction "7_7") (pintype "passive"))
    )
    (net (code "114") (name "Net-(D48-A)") (class "Default")
      (node (ref "D48") (pin "1") (pinfunction "A_1") (pintype "passive"))
      (node (ref "SW5") (pin "8") (pinfunction "8_8") (pintype "passive"))
    )
    (net (code "115") (name "Net-(D49-A)") (class "Default")
      (node (ref "D49") (pin "1") (pinfunction "A_1") (pintype "passive"))
      (node (ref "SW6") (pin "1") (pinfunction "1_1") (pintype "passive"))
    )
    (net (code "116") (name "Net-(D50-A)") (class "Default")
      (node (ref "D50") (pin "1") (pinfunction "A_1") (pintype "passive"))
      (node (ref "SW6") (pin "2") (pinfunction "2_2") (pintype "passive"))
    )
    (net (code "117") (name "Net-(D51-A)") (class "Default")
      (node (ref "D51") (pin "1") (pinfunction "A_1") (pintype "passive"))
      (node (ref "SW6") (pin "3") (pinfunction "3_3") (pintype "passive"))
    )
    (net (code "118") (name "Net-(D52-A)") (class "Default")
      (node (ref "D52") (pin "1") (pinfunction "A_1") (pintype "passive"))
      (node (ref "SW6") (pin "4") (pinfunction "4_4") (pintype "passive"))
    )
    (net (code "119") (name "Net-(D53-A)") (class "Default")
      (node (ref "D53") (pin "1") (pinfunction "A_1") (pintype "passive"))
      (node (ref "SW6") (pin "5") (pinfunction "5_5") (pintype "passive"))
    )
    (net (code "120") (name "Net-(D54-A)") (class "Default")
      (node (ref "D54") (pin "1") (pinfunction "A_1") (pintype "passive"))
      (node (ref "SW6") (pin "6") (pinfunction "6_6") (pintype "passive"))
    )
    (net (code "121") (name "Net-(D55-A)") (class "Default")
      (node (ref "D55") (pin "1") (pinfunction "A_1") (pintype "passive"))
      (node (ref "SW6") (pin "7") (pinfunction "7_7") (pintype "passive"))
    )
    (net (code "122") (name "Net-(D56-A)") (class "Default")
      (node (ref "D56") (pin "1") (pinfunction "A_1") (pintype "passive"))
      (node (ref "SW6") (pin "8") (pinfunction "8_8") (pintype "passive"))
    )
    (net (code "123") (name "Net-(D57-A)") (class "Default")
      (node (ref "D57") (pin "1") (pinfunction "A_1") (pintype "passive"))
      (node (ref "SW7") (pin "1") (pinfunction "1_1") (pintype "passive"))
    )
    (net (code "124") (name "Net-(D58-A)") (class "Default")
      (node (ref "D58") (pin "1") (pinfunction "A_1") (pintype "passive"))
      (node (ref "SW7") (pin "2") (pinfunction "2_2") (pintype "passive"))
    )
    (net (code "125") (name "Net-(D59-A)") (class "Default")
      (node (ref "D59") (pin "1") (pinfunction "A_1") (pintype "passive"))
      (node (ref "SW7") (pin "3") (pinfunction "3_3") (pintype "passive"))
    )
    (net (code "126") (name "Net-(D60-A)") (class "Default")
      (node (ref "D60") (pin "1") (pinfunction "A_1") (pintype "passive"))
      (node (ref "SW7") (pin "4") (pinfunction "4_4") (pintype "passive"))
    )
    (net (code "127") (name "Net-(D61-A)") (class "Default")
      (node (ref "D61") (pin "1") (pinfunction "A_1") (pintype "passive"))
      (node (ref "SW7") (pin "5") (pinfunction "5_5") (pintype "passive"))
    )
    (net (code "128") (name "Net-(D62-A)") (class "Default")
      (node (ref "D62") (pin "1") (pinfunction "A_1") (pintype "passive"))
      (node (ref "SW7") (pin "6") (pinfunction "6_6") (pintype "passive"))
    )
    (net (code "129") (name "Net-(D63-A)") (class "Default")
      (node (ref "D63") (pin "1") (pinfunction "A_1") (pintype "passive"))
      (node (ref "SW7") (pin "7") (pinfunction "7_7") (pintype "passive"))
    )
    (net (code "130") (name "Net-(D64-A)") (class "Default")
      (node (ref "D64") (pin "1") (pinfunction "A_1") (pintype "passive"))
      (node (ref "SW7") (pin "8") (pinfunction "8_8") (pintype "passive"))
    )
    (net (code "131") (name "Net-(D65-A)") (class "Default")
      (node (ref "D65") (pin "1") (pinfunction "A_1") (pintype "passive"))
      (node (ref "SW8") (pin "1") (pinfunction "1_1") (pintype "passive"))
    )
    (net (code "132") (name "Net-(D66-A)") (class "Default")
      (node (ref "D66") (pin "1") (pinfunction "A_1") (pintype "passive"))
      (node (ref "SW8") (pin "2") (pinfunction "2_2") (pintype "passive"))
    )
    (net (code "133") (name "Net-(D67-A)") (class "Default")
      (node (ref "D67") (pin "1") (pinfunction "A_1") (pintype "passive"))
      (node (ref "SW8") (pin "3") (pinfunction "3_3") (pintype "passive"))
    )
    (net (code "134") (name "Net-(D68-A)") (class "Default")
      (node (ref "D68") (pin "1") (pinfunction "A_1") (pintype "passive"))
      (node (ref "SW8") (pin "4") (pinfunction "4_4") (pintype "passive"))
    )
    (net (code "135") (name "Net-(D69-A)") (class "Default")
      (node (ref "D69") (pin "1") (pinfunction "A_1") (pintype "passive"))
      (node (ref "SW8") (pin "5") (pinfunction "5_5") (pintype "passive"))
    )
    (net (code "136") (name "Net-(D70-A)") (class "Default")
      (node (ref "D70") (pin "1") (pinfunction "A_1") (pintype "passive"))
      (node (ref "SW8") (pin "6") (pinfunction "6_6") (pintype "passive"))
    )
    (net (code "137") (name "Net-(D71-A)") (class "Default")
      (node (ref "D71") (pin "1") (pinfunction "A_1") (pintype "passive"))
      (node (ref "SW8") (pin "7") (pinfunction "7_7") (pintype "passive"))
    )
    (net (code "138") (name "Net-(D72-A)") (class "Default")
      (node (ref "D72") (pin "1") (pinfunction "A_1") (pintype "passive"))
      (node (ref "SW8") (pin "8") (pinfunction "8_8") (pintype "passive"))
    )
    (net (code "139") (name "Net-(D73-A)") (class "Default")
      (node (ref "D73") (pin "1") (pinfunction "A_1") (pintype "passive"))
      (node (ref "SW9") (pin "1") (pinfunction "1_1") (pintype "passive"))
    )
    (net (code "140") (name "Net-(D74-A)") (class "Default")
      (node (ref "D74") (pin "1") (pinfunction "A_1") (pintype "passive"))
      (node (ref "SW9") (pin "2") (pinfunction "2_2") (pintype "passive"))
    )
    (net (code "141") (name "Net-(D75-A)") (class "Default")
      (node (ref "D75") (pin "1") (pinfunction "A_1") (pintype "passive"))
      (node (ref "SW9") (pin "3") (pinfunction "3_3") (pintype "passive"))
    )
    (net (code "142") (name "Net-(D76-A)") (class "Default")
      (node (ref "D76") (pin "1") (pinfunction "A_1") (pintype "passive"))
      (node (ref "SW9") (pin "4") (pinfunction "4_4") (pintype "passive"))
    )
    (net (code "143") (name "Net-(D77-A)") (class "Default")
      (node (ref "D77") (pin "1") (pinfunction "A_1") (pintype "passive"))
      (node (ref "SW9") (pin "5") (pinfunction "5_5") (pintype "passive"))
    )
    (net (code "144") (name "Net-(D78-A)") (class "Default")
      (node (ref "D78") (pin "1") (pinfunction "A_1") (pintype "passive"))
      (node (ref "SW9") (pin "6") (pinfunction "6_6") (pintype "passive"))
    )
    (net (code "145") (name "Net-(D79-A)") (class "Default")
      (node (ref "D79") (pin "1") (pinfunction "A_1") (pintype "passive"))
      (node (ref "SW9") (pin "7") (pinfunction "7_7") (pintype "passive"))
    )
    (net (code "146") (name "Net-(D80-A)") (class "Default")
      (node (ref "D80") (pin "1") (pinfunction "A_1") (pintype "passive"))
      (node (ref "SW9") (pin "8") (pinfunction "8_8") (pintype "passive"))
    )
    (net (code "147") (name "Net-(D81-A)") (class "Default")
      (node (ref "D81") (pin "1") (pinfunction "A_1") (pintype "passive"))
      (node (ref "SW10") (pin "1") (pinfunction "1_1") (pintype "passive"))
    )
    (net (code "148") (name "Net-(D82-A)") (class "Default")
      (node (ref "D82") (pin "1") (pinfunction "A_1") (pintype "passive"))
      (node (ref "SW10") (pin "2") (pinfunction "2_2") (pintype "passive"))
    )
    (net (code "149") (name "Net-(D83-A)") (class "Default")
      (node (ref "D83") (pin "1") (pinfunction "A_1") (pintype "passive"))
      (node (ref "SW10") (pin "3") (pinfunction "3_3") (pintype "passive"))
    )
    (net (code "150") (name "Net-(D84-A)") (class "Default")
      (node (ref "D84") (pin "1") (pinfunction "A_1") (pintype "passive"))
      (node (ref "SW10") (pin "4") (pinfunction "4_4") (pintype "passive"))
    )
    (net (code "151") (name "Net-(D85-A)") (class "Default")
      (node (ref "D85") (pin "1") (pinfunction "A_1") (pintype "passive"))
      (node (ref "SW10") (pin "5") (pinfunction "5_5") (pintype "passive"))
    )
    (net (code "152") (name "Net-(D86-A)") (class "Default")
      (node (ref "D86") (pin "1") (pinfunction "A_1") (pintype "passive"))
      (node (ref "SW10") (pin "6") (pinfunction "6_6") (pintype "passive"))
    )
    (net (code "153") (name "Net-(D87-A)") (class "Default")
      (node (ref "D87") (pin "1") (pinfunction "A_1") (pintype "passive"))
      (node (ref "SW10") (pin "7") (pinfunction "7_7") (pintype "passive"))
    )
    (net (code "154") (name "Net-(D88-A)") (class "Default")
      (node (ref "D88") (pin "1") (pinfunction "A_1") (pintype "passive"))
      (node (ref "SW10") (pin "8") (pinfunction "8_8") (pintype "passive"))
    )
    (net (code "155") (name "Net-(D89-A)") (class "Default")
      (node (ref "D89") (pin "1") (pinfunction "A_1") (pintype "passive"))
      (node (ref "SW11") (pin "1") (pinfunction "1_1") (pintype "passive"))
    )
    (net (code "156") (name "Net-(D90-A)") (class "Default")
      (node (ref "D90") (pin "1") (pinfunction "A_1") (pintype "passive"))
      (node (ref "SW11") (pin "2") (pinfunction "2_2") (pintype "passive"))
    )
    (net (code "157") (name "Net-(D91-A)") (class "Default")
      (node (ref "D91") (pin "1") (pinfunction "A_1") (pintype "passive"))
      (node (ref "SW11") (pin "3") (pinfunction "3_3") (pintype "passive"))
    )
    (net (code "158") (name "Net-(D92-A)") (class "Default")
      (node (ref "D92") (pin "1") (pinfunction "A_1") (pintype "passive"))
      (node (ref "SW11") (pin "4") (pinfunction "4_4") (pintype "passive"))
    )
    (net (code "159") (name "Net-(D93-A)") (class "Default")
      (node (ref "D93") (pin "1") (pinfunction "A_1") (pintype "passive"))
      (node (ref "SW11") (pin "5") (pinfunction "5_5") (pintype "passive"))
    )
    (net (code "160") (name "Net-(D94-A)") (class "Default")
      (node (ref "D94") (pin "1") (pinfunction "A_1") (pintype "passive"))
      (node (ref "SW11") (pin "6") (pinfunction "6_6") (pintype "passive"))
    )
    (net (code "161") (name "Net-(D95-A)") (class "Default")
      (node (ref "D95") (pin "1") (pinfunction "A_1") (pintype "passive"))
      (node (ref "SW11") (pin "7") (pinfunction "7_7") (pintype "passive"))
    )
    (net (code "162") (name "Net-(D96-A)") (class "Default")
      (node (ref "D96") (pin "1") (pinfunction "A_1") (pintype "passive"))
      (node (ref "SW11") (pin "8") (pinfunction "8_8") (pintype "passive"))
    )
    (net (code "163") (name "Net-(D97-A)") (class "Default")
      (node (ref "D97") (pin "1") (pinfunction "A_1") (pintype "passive"))
      (node (ref "SW12") (pin "1") (pinfunction "1_1") (pintype "passive"))
    )
    (net (code "164") (name "Net-(D98-A)") (class "Default")
      (node (ref "D98") (pin "1") (pinfunction "A_1") (pintype "passive"))
      (node (ref "SW12") (pin "2") (pinfunction "2_2") (pintype "passive"))
    )
    (net (code "165") (name "Net-(D99-A)") (class "Default")
      (node (ref "D99") (pin "1") (pinfunction "A_1") (pintype "passive"))
      (node (ref "SW12") (pin "3") (pinfunction "3_3") (pintype "passive"))
    )
    (net (code "166") (name "Net-(D100-A)") (class "Default")
      (node (ref "D100") (pin "1") (pinfunction "A_1") (pintype "passive"))
      (node (ref "SW12") (pin "4") (pinfunction "4_4") (pintype "passive"))
    )
    (net (code "167") (name "Net-(D101-A)") (class "Default")
      (node (ref "D101") (pin "1") (pinfunction "A_1") (pintype "passive"))
      (node (ref "SW12") (pin "5") (pinfunction "5_5") (pintype "passive"))
    )
    (net (code "168") (name "Net-(D102-A)") (class "Default")
      (node (ref "D102") (pin "1") (pinfunction "A_1") (pintype "passive"))
      (node (ref "SW12") (pin "6") (pinfunction "6_6") (pintype "passive"))
    )
    (net (code "169") (name "Net-(D103-A)") (class "Default")
      (node (ref "D103") (pin "1") (pinfunction "A_1") (pintype "passive"))
      (node (ref "SW12") (pin "7") (pinfunction "7_7") (pintype "passive"))
    )
    (net (code "170") (name "Net-(D104-A)") (class "Default")
      (node (ref "D104") (pin "1") (pinfunction "A_1") (pintype "passive"))
      (node (ref "SW12") (pin "8") (pinfunction "8_8") (pintype "passive"))
    )
    (net (code "171") (name "Net-(D105-A)") (class "Default")
      (node (ref "D105") (pin "1") (pinfunction "A_1") (pintype "passive"))
      (node (ref "SW13") (pin "1") (pinfunction "1_1") (pintype "passive"))
    )
    (net (code "172") (name "Net-(D106-A)") (class "Default")
      (node (ref "D106") (pin "1") (pinfunction "A_1") (pintype "passive"))
      (node (ref "SW13") (pin "2") (pinfunction "2_2") (pintype "passive"))
    )
    (net (code "173") (name "Net-(D107-A)") (class "Default")
      (node (ref "D107") (pin "1") (pinfunction "A_1") (pintype "passive"))
      (node (ref "SW13") (pin "3") (pinfunction "3_3") (pintype "passive"))
    )
    (net (code "174") (name "Net-(D108-A)") (class "Default")
      (node (ref "D108") (pin "1") (pinfunction "A_1") (pintype "passive"))
      (node (ref "SW13") (pin "4") (pinfunction "4_4") (pintype "passive"))
    )
    (net (code "175") (name "Net-(D109-A)") (class "Default")
      (node (ref "D109") (pin "1") (pinfunction "A_1") (pintype "passive"))
      (node (ref "SW13") (pin "5") (pinfunction "5_5") (pintype "passive"))
    )
    (net (code "176") (name "Net-(D110-A)") (class "Default")
      (node (ref "D110") (pin "1") (pinfunction "A_1") (pintype "passive"))
      (node (ref "SW13") (pin "6") (pinfunction "6_6") (pintype "passive"))
    )
    (net (code "177") (name "Net-(D111-A)") (class "Default")
      (node (ref "D111") (pin "1") (pinfunction "A_1") (pintype "passive"))
      (node (ref "SW13") (pin "7") (pinfunction "7_7") (pintype "passive"))
    )
    (net (code "178") (name "Net-(D112-A)") (class "Default")
      (node (ref "D112") (pin "1") (pinfunction "A_1") (pintype "passive"))
      (node (ref "SW13") (pin "8") (pinfunction "8_8") (pintype "passive"))
    )
    (net (code "179") (name "Net-(D113-A)") (class "Default")
      (node (ref "D113") (pin "1") (pinfunction "A_1") (pintype "passive"))
      (node (ref "SW14") (pin "1") (pinfunction "1_1") (pintype "passive"))
    )
    (net (code "180") (name "Net-(D114-A)") (class "Default")
      (node (ref "D114") (pin "1") (pinfunction "A_1") (pintype "passive"))
      (node (ref "SW14") (pin "2") (pinfunction "2_2") (pintype "passive"))
    )
    (net (code "181") (name "Net-(D115-A)") (class "Default")
      (node (ref "D115") (pin "1") (pinfunction "A_1") (pintype "passive"))
      (node (ref "SW14") (pin "3") (pinfunction "3_3") (pintype "passive"))
    )
    (net (code "182") (name "Net-(D116-A)") (class "Default")
      (node (ref "D116") (pin "1") (pinfunction "A_1") (pintype "passive"))
      (node (ref "SW14") (pin "4") (pinfunction "4_4") (pintype "passive"))
    )
    (net (code "183") (name "Net-(D117-A)") (class "Default")
      (node (ref "D117") (pin "1") (pinfunction "A_1") (pintype "passive"))
      (node (ref "SW14") (pin "5") (pinfunction "5_5") (pintype "passive"))
    )
    (net (code "184") (name "Net-(D118-A)") (class "Default")
      (node (ref "D118") (pin "1") (pinfunction "A_1") (pintype "passive"))
      (node (ref "SW14") (pin "6") (pinfunction "6_6") (pintype "passive"))
    )
    (net (code "185") (name "Net-(D119-A)") (class "Default")
      (node (ref "D119") (pin "1") (pinfunction "A_1") (pintype "passive"))
      (node (ref "SW14") (pin "7") (pinfunction "7_7") (pintype "passive"))
    )
    (net (code "186") (name "Net-(D120-A)") (class "Default")
      (node (ref "D120") (pin "1") (pinfunction "A_1") (pintype "passive"))
      (node (ref "SW14") (pin "8") (pinfunction "8_8") (pintype "passive"))
    )
    (net (code "187") (name "Net-(D121-A)") (class "Default")
      (node (ref "D121") (pin "1") (pinfunction "A_1") (pintype "passive"))
      (node (ref "SW15") (pin "1") (pinfunction "1_1") (pintype "passive"))
    )
    (net (code "188") (name "Net-(D122-A)") (class "Default")
      (node (ref "D122") (pin "1") (pinfunction "A_1") (pintype "passive"))
      (node (ref "SW15") (pin "2") (pinfunction "2_2") (pintype "passive"))
    )
    (net (code "189") (name "Net-(D123-A)") (class "Default")
      (node (ref "D123") (pin "1") (pinfunction "A_1") (pintype "passive"))
      (node (ref "SW15") (pin "3") (pinfunction "3_3") (pintype "passive"))
    )
    (net (code "190") (name "Net-(D124-A)") (class "Default")
      (node (ref "D124") (pin "1") (pinfunction "A_1") (pintype "passive"))
      (node (ref "SW15") (pin "4") (pinfunction "4_4") (pintype "passive"))
    )
    (net (code "191") (name "Net-(D125-A)") (class "Default")
      (node (ref "D125") (pin "1") (pinfunction "A_1") (pintype "passive"))
      (node (ref "SW15") (pin "5") (pinfunction "5_5") (pintype "passive"))
    )
    (net (code "192") (name "Net-(D126-A)") (class "Default")
      (node (ref "D126") (pin "1") (pinfunction "A_1") (pintype "passive"))
      (node (ref "SW15") (pin "6") (pinfunction "6_6") (pintype "passive"))
    )
    (net (code "193") (name "Net-(D127-A)") (class "Default")
      (node (ref "D127") (pin "1") (pinfunction "A_1") (pintype "passive"))
      (node (ref "SW15") (pin "7") (pinfunction "7_7") (pintype "passive"))
    )
    (net (code "194") (name "Net-(D128-A)") (class "Default")
      (node (ref "D128") (pin "1") (pinfunction "A_1") (pintype "passive"))
      (node (ref "SW15") (pin "8") (pinfunction "8_8") (pintype "passive"))
    )
    (net (code "195") (name "Net-(LED0-A)") (class "Default")
      (node (ref "LED0") (pin "1") (pinfunction "A_1") (pintype "passive"))
      (node (ref "R9") (pin "1") (pinfunction "1_1") (pintype "passive"))
    )
    (net (code "196") (name "Net-(LED1-A)") (class "Default")
      (node (ref "LED1") (pin "1") (pinfunction "A_1") (pintype "passive"))
      (node (ref "R10") (pin "1") (pinfunction "1_1") (pintype "passive"))
    )
    (net (code "197") (name "Net-(LED2-A)") (class "Default")
      (node (ref "LED2") (pin "1") (pinfunction "A_1") (pintype "passive"))
      (node (ref "R11") (pin "1") (pinfunction "1_1") (pintype "passive"))
    )
    (net (code "198") (name "Net-(LED3-A)") (class "Default")
      (node (ref "LED3") (pin "1") (pinfunction "A_1") (pintype "passive"))
      (node (ref "R12") (pin "1") (pinfunction "1_1") (pintype "passive"))
    )
    (net (code "199") (name "Net-(LED4-A)") (class "Default")
      (node (ref "LED4") (pin "1") (pinfunction "A_1") (pintype "passive"))
      (node (ref "R13") (pin "1") (pinfunction "1_1") (pintype "passive"))
    )
    (net (code "200") (name "Net-(LED5-A)") (class "Default")
      (node (ref "LED5") (pin "1") (pinfunction "A_1") (pintype "passive"))
      (node (ref "R14") (pin "1") (pinfunction "1_1") (pintype "passive"))
    )
    (net (code "201") (name "Net-(LED6-A)") (class "Default")
      (node (ref "LED6") (pin "1") (pinfunction "A_1") (pintype "passive"))
      (node (ref "R15") (pin "1") (pinfunction "1_1") (pintype "passive"))
    )
    (net (code "202") (name "Net-(LED7-A)") (class "Default")
      (node (ref "LED7") (pin "1") (pinfunction "A_1") (pintype "passive"))
      (node (ref "R16") (pin "1") (pinfunction "1_1") (pintype "passive"))
    )
    (net (code "203") (name "Net-(LED8-A)") (class "Default")
      (node (ref "LED8") (pin "1") (pinfunction "A_1") (pintype "passive"))
      (node (ref "R17") (pin "1") (pinfunction "1_1") (pintype "passive"))
    )
    (net (code "204") (name "Net-(LED9-A)") (class "Default")
      (node (ref "LED9") (pin "1") (pinfunction "A_1") (pintype "passive"))
      (node (ref "R18") (pin "1") (pinfunction "1_1") (pintype "passive"))
    )
    (net (code "205") (name "Net-(LED10-A)") (class "Default")
      (node (ref "LED10") (pin "1") (pinfunction "A_1") (pintype "passive"))
      (node (ref "R19") (pin "1") (pinfunction "1_1") (pintype "passive"))
    )
    (net (code "206") (name "Net-(LED11-A)") (class "Default")
      (node (ref "LED11") (pin "1") (pinfunction "A_1") (pintype "passive"))
      (node (ref "R20") (pin "1") (pinfunction "1_1") (pintype "passive"))
    )
    (net (code "207") (name "Net-(LED12-A)") (class "Default")
      (node (ref "LED12") (pin "1") (pinfunction "A_1") (pintype "passive"))
      (node (ref "R21") (pin "1") (pinfunction "1_1") (pintype "passive"))
    )
    (net (code "208") (name "Net-(LED13-A)") (class "Default")
      (node (ref "LED13") (pin "1") (pinfunction "A_1") (pintype "passive"))
      (node (ref "R22") (pin "1") (pinfunction "1_1") (pintype "passive"))
    )
    (net (code "209") (name "Net-(LED14-A)") (class "Default")
      (node (ref "LED14") (pin "1") (pinfunction "A_1") (pintype "passive"))
      (node (ref "R23") (pin "1") (pinfunction "1_1") (pintype "passive"))
    )
    (net (code "210") (name "Net-(LED15-A)") (class "Default")
      (node (ref "LED15") (pin "1") (pinfunction "A_1") (pintype "passive"))
      (node (ref "R24") (pin "1") (pinfunction "1_1") (pintype "passive"))
    )
    (net (code "211") (name "Net-(LED16-A)") (class "Default")
      (node (ref "LED16") (pin "1") (pinfunction "A_1") (pintype "passive"))
      (node (ref "R25") (pin "1") (pinfunction "1_1") (pintype "passive"))
    )
    (net (code "212") (name "Net-(LED17-A)") (class "Default")
      (node (ref "LED17") (pin "1") (pinfunction "A_1") (pintype "passive"))
      (node (ref "R26") (pin "1") (pinfunction "1_1") (pintype "passive"))
    )
    (net (code "213") (name "Net-(LED18-A)") (class "Default")
      (node (ref "LED18") (pin "1") (pinfunction "A_1") (pintype "passive"))
      (node (ref "R27") (pin "1") (pinfunction "1_1") (pintype "passive"))
    )
    (net (code "214") (name "Net-(LED19-A)") (class "Default")
      (node (ref "LED19") (pin "1") (pinfunction "A_1") (pintype "passive"))
      (node (ref "R28") (pin "1") (pinfunction "1_1") (pintype "passive"))
    )
    (net (code "215") (name "Net-(LED20-A)") (class "Default")
      (node (ref "LED20") (pin "1") (pinfunction "A_1") (pintype "passive"))
      (node (ref "R29") (pin "1") (pinfunction "1_1") (pintype "passive"))
    )
    (net (code "216") (name "Net-(LED21-A)") (class "Default")
      (node (ref "LED21") (pin "1") (pinfunction "A_1") (pintype "passive"))
      (node (ref "R30") (pin "1") (pinfunction "1_1") (pintype "passive"))
    )
    (net (code "217") (name "Net-(LED22-A)") (class "Default")
      (node (ref "LED22") (pin "1") (pinfunction "A_1") (pintype "passive"))
      (node (ref "R31") (pin "1") (pinfunction "1_1") (pintype "passive"))
    )
    (net (code "218") (name "Net-(LED23-A)") (class "Default")
      (node (ref "LED23") (pin "1") (pinfunction "A_1") (pintype "passive"))
      (node (ref "R32") (pin "1") (pinfunction "1_1") (pintype "passive"))
    )
    (net (code "219") (name "Net-(LED24-A)") (class "Default")
      (node (ref "LED24") (pin "1") (pinfunction "A_1") (pintype "passive"))
      (node (ref "R33") (pin "1") (pinfunction "1_1") (pintype "passive"))
    )
    (net (code "220") (name "Net-(LED25-A)") (class "Default")
      (node (ref "LED25") (pin "1") (pinfunction "A_1") (pintype "passive"))
      (node (ref "R34") (pin "1") (pinfunction "1_1") (pintype "passive"))
    )
    (net (code "221") (name "Net-(LED26-A)") (class "Default")
      (node (ref "LED26") (pin "1") (pinfunction "A_1") (pintype "passive"))
      (node (ref "R35") (pin "1") (pinfunction "1_1") (pintype "passive"))
    )
    (net (code "222") (name "Net-(LED27-A)") (class "Default")
      (node (ref "LED27") (pin "1") (pinfunction "A_1") (pintype "passive"))
      (node (ref "R36") (pin "1") (pinfunction "1_1") (pintype "passive"))
    )
    (net (code "223") (name "Net-(LED28-A)") (class "Default")
      (node (ref "LED28") (pin "1") (pinfunction "A_1") (pintype "passive"))
      (node (ref "R37") (pin "1") (pinfunction "1_1") (pintype "passive"))
    )
    (net (code "224") (name "Net-(LED29-A)") (class "Default")
      (node (ref "LED29") (pin "1") (pinfunction "A_1") (pintype "passive"))
      (node (ref "R38") (pin "1") (pinfunction "1_1") (pintype "passive"))
    )
    (net (code "225") (name "Net-(LED30-A)") (class "Default")
      (node (ref "LED30") (pin "1") (pinfunction "A_1") (pintype "passive"))
      (node (ref "R39") (pin "1") (pinfunction "1_1") (pintype "passive"))
    )
    (net (code "226") (name "Net-(LED31-A)") (class "Default")
      (node (ref "LED31") (pin "1") (pinfunction "A_1") (pintype "passive"))
      (node (ref "R40") (pin "1") (pinfunction "1_1") (pintype "passive"))
    )
    (net (code "227") (name "Net-(LED32-A)") (class "Default")
      (node (ref "LED32") (pin "1") (pinfunction "A_1") (pintype "passive"))
      (node (ref "R41") (pin "1") (pinfunction "1_1") (pintype "passive"))
    )
    (net (code "228") (name "Net-(LED33-K)") (class "Default")
      (node (ref "LED33") (pin "2") (pinfunction "K_2") (pintype "passive"))
      (node (ref "R42") (pin "2") (pinfunction "2_2") (pintype "passive"))
    )
    (net (code "229") (name "Net-(LED34-K)") (class "Default")
      (node (ref "LED34") (pin "2") (pinfunction "K_2") (pintype "passive"))
      (node (ref "R43") (pin "2") (pinfunction "2_2") (pintype "passive"))
    )
    (net (code "230") (name "Net-(LED35-K)") (class "Default")
      (node (ref "LED35") (pin "2") (pinfunction "K_2") (pintype "passive"))
      (node (ref "R44") (pin "2") (pinfunction "2_2") (pintype "passive"))
    )
    (net (code "231") (name "Net-(LED36-A)") (class "Default")
      (node (ref "LED36") (pin "1") (pinfunction "A_1") (pintype "passive"))
      (node (ref "R45") (pin "2") (pinfunction "2_2") (pintype "passive"))
    )
    (net (code "232") (name "Net-(LED37-K)") (class "Default")
      (node (ref "LED37") (pin "2") (pinfunction "K_2") (pintype "passive"))
      (node (ref "R46") (pin "2") (pinfunction "2_2") (pintype "passive"))
    )
    (net (code "233") (name "Net-(LED38-K)") (class "Default")
      (node (ref "LED38") (pin "2") (pinfunction "K_2") (pintype "passive"))
      (node (ref "R47") (pin "2") (pinfunction "2_2") (pintype "passive"))
    )
    (net (code "234") (name "Net-(LED39-K)") (class "Default")
      (node (ref "LED39") (pin "2") (pinfunction "K_2") (pintype "passive"))
      (node (ref "R48") (pin "2") (pinfunction "2_2") (pintype "passive"))
    )
    (net (code "235") (name "Net-(LED40-K)") (class "Default")
      (node (ref "LED40") (pin "2") (pinfunction "K_2") (pintype "passive"))
      (node (ref "R49") (pin "2") (pinfunction "2_2") (pintype "passive"))
    )
    (net (code "236") (name "Net-(LED41-A)") (class "Default")
      (node (ref "LED41") (pin "1") (pinfunction "A_1") (pintype "passive"))
      (node (ref "R50") (pin "1") (pinfunction "1_1") (pintype "passive"))
    )
    (net (code "237") (name "Net-(LED42-A)") (class "Default")
      (node (ref "LED42") (pin "1") (pinfunction "A_1") (pintype "passive"))
      (node (ref "R51") (pin "1") (pinfunction "1_1") (pintype "passive"))
    )
    (net (code "238") (name "Net-(LED43-K)") (class "Default")
      (node (ref "LED43") (pin "2") (pinfunction "K_2") (pintype "passive"))
      (node (ref "R52") (pin "2") (pinfunction "2_2") (pintype "passive"))
    )
    (net (code "239") (name "Net-(LED44-K)") (class "Default")
      (node (ref "LED44") (pin "2") (pinfunction "K_2") (pintype "passive"))
      (node (ref "R53") (pin "2") (pinfunction "2_2") (pintype "passive"))
    )
    (net (code "240") (name "Net-(LED45-K)") (class "Default")
      (node (ref "LED45") (pin "2") (pinfunction "K_2") (pintype "passive"))
      (node (ref "R54") (pin "2") (pinfunction "2_2") (pintype "passive"))
    )
    (net (code "241") (name "Net-(LED46-K)") (class "Default")
      (node (ref "LED46") (pin "2") (pinfunction "K_2") (pintype "passive"))
      (node (ref "R55") (pin "2") (pinfunction "2_2") (pintype "passive"))
    )
    (net (code "242") (name "Net-(LED47-K)") (class "Default")
      (node (ref "LED47") (pin "2") (pinfunction "K_2") (pintype "passive"))
      (node (ref "R56") (pin "2") (pinfunction "2_2") (pintype "passive"))
    )
    (net (code "243") (name "Net-(LED48-A)") (class "Default")
      (node (ref "LED48") (pin "1") (pinfunction "A_1") (pintype "passive"))
      (node (ref "R57") (pin "1") (pinfunction "1_1") (pintype "passive"))
    )
    (net (code "244") (name "Net-(LED49-A)") (class "Default")
      (node (ref "LED49") (pin "1") (pinfunction "A_1") (pintype "passive"))
      (node (ref "R58") (pin "1") (pinfunction "1_1") (pintype "passive"))
    )
    (net (code "245") (name "Net-(LED50-K)") (class "Default")
      (node (ref "LED50") (pin "2") (pinfunction "K_2") (pintype "passive"))
      (node (ref "R59") (pin "2") (pinfunction "2_2") (pintype "passive"))
    )
    (net (code "246") (name "Net-(LED51-K)") (class "Default")
      (node (ref "LED51") (pin "2") (pinfunction "K_2") (pintype "passive"))
      (node (ref "R60") (pin "2") (pinfunction "2_2") (pintype "passive"))
    )
    (net (code "247") (name "Net-(LED52-K)") (class "Default")
      (node (ref "LED52") (pin "2") (pinfunction "K_2") (pintype "passive"))
      (node (ref "R61") (pin "2") (pinfunction "2_2") (pintype "passive"))
    )
    (net (code "248") (name "Net-(LED53-K)") (class "Default")
      (node (ref "LED53") (pin "2") (pinfunction "K_2") (pintype "passive"))
      (node (ref "R62") (pin "2") (pinfunction "2_2") (pintype "passive"))
    )
    (net (code "249") (name "Net-(LED54-K)") (class "Default")
      (node (ref "LED54") (pin "2") (pinfunction "K_2") (pintype "passive"))
      (node (ref "R63") (pin "2") (pinfunction "2_2") (pintype "passive"))
    )
    (net (code "250") (name "Net-(LED55-A)") (class "Default")
      (node (ref "LED55") (pin "1") (pinfunction "A_1") (pintype "passive"))
      (node (ref "R64") (pin "1") (pinfunction "1_1") (pintype "passive"))
    )
    (net (code "251") (name "Net-(LED56-A)") (class "Default")
      (node (ref "LED56") (pin "1") (pinfunction "A_1") (pintype "passive"))
      (node (ref "R65") (pin "1") (pinfunction "1_1") (pintype "passive"))
    )
    (net (code "252") (name "Net-(LED57-K)") (class "Default")
      (node (ref "LED57") (pin "2") (pinfunction "K_2") (pintype "passive"))
      (node (ref "R66") (pin "2") (pinfunction "2_2") (pintype "passive"))
    )
    (net (code "253") (name "Net-(LED58-K)") (class "Default")
      (node (ref "LED58") (pin "2") (pinfunction "K_2") (pintype "passive"))
      (node (ref "R67") (pin "2") (pinfunction "2_2") (pintype "passive"))
    )
    (net (code "254") (name "Net-(LED59-K)") (class "Default")
      (node (ref "LED59") (pin "2") (pinfunction "K_2") (pintype "passive"))
      (node (ref "R68") (pin "2") (pinfunction "2_2") (pintype "passive"))
    )
    (net (code "255") (name "Net-(LED60-K)") (class "Default")
      (node (ref "LED60") (pin "2") (pinfunction "K_2") (pintype "passive"))
      (node (ref "R69") (pin "2") (pinfunction "2_2") (pintype "passive"))
    )
    (net (code "256") (name "Net-(LED61-K)") (class "Default")
      (node (ref "LED61") (pin "2") (pinfunction "K_2") (pintype "passive"))
      (node (ref "R70") (pin "2") (pinfunction "2_2") (pintype "passive"))
    )
    (net (code "257") (name "Net-(LED62-A)") (class "Default")
      (node (ref "LED62") (pin "1") (pinfunction "A_1") (pintype "passive"))
      (node (ref "R71") (pin "1") (pinfunction "1_1") (pintype "passive"))
    )
    (net (code "258") (name "Net-(LED63-A)") (class "Default")
      (node (ref "LED63") (pin "1") (pinfunction "A_1") (pintype "passive"))
      (node (ref "R72") (pin "1") (pinfunction "1_1") (pintype "passive"))
    )
    (net (code "259") (name "Net-(LED64-K)") (class "Default")
      (node (ref "LED64") (pin "2") (pinfunction "K_2") (pintype "passive"))
      (node (ref "R73") (pin "2") (pinfunction "2_2") (pintype "passive"))
    )
    (net (code "260") (name "Net-(LED65-K)") (class "Default")
      (node (ref "LED65") (pin "2") (pinfunction "K_2") (pintype "passive"))
      (node (ref "R74") (pin "2") (pinfunction "2_2") (pintype "passive"))
    )
    (net (code "261") (name "Net-(LED66-A)") (class "Default")
      (node (ref "LED66") (pin "1") (pinfunction "A_1") (pintype "passive"))
      (node (ref "R89") (pin "1") (pinfunction "1_1") (pintype "passive"))
    )
    (net (code "262") (name "Net-(LED67-A)") (class "Default")
      (node (ref "LED67") (pin "1") (pinfunction "A_1") (pintype "passive"))
      (node (ref "R90") (pin "1") (pinfunction "1_1") (pintype "passive"))
    )
    (net (code "263") (name "Net-(LED68-A)") (class "Default")
      (node (ref "LED68") (pin "1") (pinfunction "A_1") (pintype "passive"))
      (node (ref "R91") (pin "1") (pinfunction "1_1") (pintype "passive"))
    )
    (net (code "264") (name "Net-(LED69-A)") (class "Default")
      (node (ref "LED69") (pin "1") (pinfunction "A_1") (pintype "passive"))
      (node (ref "R92") (pin "1") (pinfunction "1_1") (pintype "passive"))
    )
    (net (code "265") (name "Net-(LED70-A)") (class "Default")
      (node (ref "LED70") (pin "1") (pinfunction "A_1") (pintype "passive"))
      (node (ref "R93") (pin "1") (pinfunction "1_1") (pintype "passive"))
    )
    (net (code "266") (name "Net-(LED71-A)") (class "Default")
      (node (ref "LED71") (pin "1") (pinfunction "A_1") (pintype "passive"))
      (node (ref "R94") (pin "1") (pinfunction "1_1") (pintype "passive"))
    )
    (net (code "267") (name "Net-(LED72-A)") (class "Default")
      (node (ref "LED72") (pin "1") (pinfunction "A_1") (pintype "passive"))
      (node (ref "R95") (pin "1") (pinfunction "1_1") (pintype "passive"))
    )
    (net (code "268") (name "Net-(LED73-A)") (class "Default")
      (node (ref "LED73") (pin "1") (pinfunction "A_1") (pintype "passive"))
      (node (ref "R96") (pin "1") (pinfunction "1_1") (pintype "passive"))
    )
    (net (code "269") (name "Net-(LED74-K)") (class "Default")
      (node (ref "LED74") (pin "2") (pinfunction "K_2") (pintype "passive"))
      (node (ref "R97") (pin "2") (pinfunction "2_2") (pintype "passive"))
    )
    (net (code "270") (name "Net-(LED75-A)") (class "Default")
      (node (ref "LED75") (pin "1") (pinfunction "A_1") (pintype "passive"))
      (node (ref "R98") (pin "1") (pinfunction "1_1") (pintype "passive"))
    )
    (net (code "271") (name "Net-(LED76-A)") (class "Default")
      (node (ref "LED76") (pin "1") (pinfunction "A_1") (pintype "passive"))
      (node (ref "R99") (pin "1") (pinfunction "1_1") (pintype "passive"))
    )
    (net (code "272") (name "Net-(LED77-A)") (class "Default")
      (node (ref "LED77") (pin "1") (pinfunction "A_1") (pintype "passive"))
      (node (ref "R100") (pin "1") (pinfunction "1_1") (pintype "passive"))
    )
    (net (code "273") (name "Net-(LED78-A)") (class "Default")
      (node (ref "LED78") (pin "1") (pinfunction "A_1") (pintype "passive"))
      (node (ref "R101") (pin "1") (pinfunction "1_1") (pintype "passive"))
    )
    (net (code "274") (name "Net-(R75-Pad1)") (class "Default")
      (node (ref "R75") (pin "1") (pinfunction "1_1") (pintype "passive"))
      (node (ref "R76") (pin "1") (pinfunction "1_1") (pintype "passive"))
      (node (ref "SW16") (pin "1") (pinfunction "K_1") (pintype "passive"))
    )
    (net (code "275") (name "Net-(R77-Pad2)") (class "Default")
      (node (ref "R77") (pin "2") (pinfunction "2_2") (pintype "passive"))
      (node (ref "U5") (pin "3") (pintype "input"))
    )
    (net (code "276") (name "Net-(R78-Pad1)") (class "Default")
      (node (ref "R78") (pin "1") (pinfunction "1_1") (pintype "passive"))
      (node (ref "U5") (pin "4") (pintype "output"))
    )
    (net (code "277") (name "Net-(R78-Pad2)") (class "Default")
      (node (ref "R78") (pin "2") (pinfunction "2_2") (pintype "passive"))
      (node (ref "S1") (pin "1") (pinfunction "1_1") (pintype "passive"))
    )
    (net (code "278") (name "Net-(R79-Pad1)") (class "Default")
      (node (ref "R79") (pin "1") (pinfunction "1_1") (pintype "passive"))
      (node (ref "RP1") (pin "3") (pinfunction "3_3") (pintype "passive"))
    )
    (net (code "279") (name "Net-(R79-Pad2)") (class "Default")
      (node (ref "R79") (pin "2") (pinfunction "2_2") (pintype "passive"))
      (node (ref "U5") (pin "6") (pintype "output"))
      (node (ref "U5") (pin "9") (pintype "input"))
    )
    (net (code "280") (name "Net-(R80-Pad2)") (class "Default")
      (node (ref "R80") (pin "2") (pinfunction "2_2") (pintype "passive"))
      (node (ref "U5") (pin "5") (pintype "input"))
    )
    (net (code "281") (name "Net-(R81-Pad2)") (class "Default")
      (node (ref "R81") (pin "2") (pinfunction "2_2") (pintype "passive"))
      (node (ref "S1") (pin "3") (pinfunction "3_3") (pintype "passive"))
    )
    (net (code "282") (name "Net-(R82-Pad1)") (class "Default")
      (node (ref "R82") (pin "1") (pinfunction "1_1") (pintype "passive"))
      (node (ref "R83") (pin "1") (pinfunction "1_1") (pintype "passive"))
      (node (ref "SW17") (pin "1") (pinfunction "K_1") (pintype "passive"))
    )
    (net (code "283") (name "Net-(R84-Pad2)") (class "Default")
      (node (ref "R84") (pin "2") (pinfunction "2_2") (pintype "passive"))
      (node (ref "U5") (pin "11") (pintype "input"))
    )
    (net (code "284") (name "Net-(U1-A1)") (class "Default")
      (node (ref "R8") (pin "2") (pinfunction "2_2") (pintype "passive"))
      (node (ref "SW0") (pin "9") (pinfunction "9_9") (pintype "passive"))
      (node (ref "SW1") (pin "9") (pinfunction "9_9") (pintype "passive"))
      (node (ref "SW10") (pin "9") (pinfunction "9_9") (pintype "passive"))
      (node (ref "SW11") (pin "9") (pinfunction "9_9") (pintype "passive"))
      (node (ref "SW12") (pin "9") (pinfunction "9_9") (pintype "passive"))
      (node (ref "SW13") (pin "9") (pinfunction "9_9") (pintype "passive"))
      (node (ref "SW14") (pin "9") (pinfunction "9_9") (pintype "passive"))
      (node (ref "SW15") (pin "9") (pinfunction "9_9") (pintype "passive"))
      (node (ref "SW2") (pin "9") (pinfunction "9_9") (pintype "passive"))
      (node (ref "SW3") (pin "9") (pinfunction "9_9") (pintype "passive"))
      (node (ref "SW4") (pin "9") (pinfunction "9_9") (pintype "passive"))
      (node (ref "SW5") (pin "9") (pinfunction "9_9") (pintype "passive"))
      (node (ref "SW6") (pin "9") (pinfunction "9_9") (pintype "passive"))
      (node (ref "SW7") (pin "9") (pinfunction "9_9") (pintype "passive"))
      (node (ref "SW8") (pin "9") (pinfunction "9_9") (pintype "passive"))
      (node (ref "SW9") (pin "9") (pinfunction "9_9") (pintype "passive"))
      (node (ref "U1") (pin "2") (pinfunction "A1_2") (pintype "input"))
    )
    (net (code "285") (name "Net-(U1-A2)") (class "Default")
      (node (ref "R7") (pin "2") (pinfunction "2_2") (pintype "passive"))
      (node (ref "SW0") (pin "10") (pinfunction "10_10") (pintype "passive"))
      (node (ref "SW1") (pin "10") (pinfunction "10_10") (pintype "passive"))
      (node (ref "SW10") (pin "10") (pinfunction "10_10") (pintype "passive"))
      (node (ref "SW11") (pin "10") (pinfunction "10_10") (pintype "passive"))
      (node (ref "SW12") (pin "10") (pinfunction "10_10") (pintype "passive"))
      (node (ref "SW13") (pin "10") (pinfunction "10_10") (pintype "passive"))
      (node (ref "SW14") (pin "10") (pinfunction "10_10") (pintype "passive"))
      (node (ref "SW15") (pin "10") (pinfunction "10_10") (pintype "passive"))
      (node (ref "SW2") (pin "10") (pinfunction "10_10") (pintype "passive"))
      (node (ref "SW3") (pin "10") (pinfunction "10_10") (pintype "passive"))
      (node (ref "SW4") (pin "10") (pinfunction "10_10") (pintype "passive"))
      (node (ref "SW5") (pin "10") (pinfunction "10_10") (pintype "passive"))
      (node (ref "SW6") (pin "10") (pinfunction "10_10") (pintype "passive"))
      (node (ref "SW7") (pin "10") (pinfunction "10_10") (pintype "passive"))
      (node (ref "SW8") (pin "10") (pinfunction "10_10") (pintype "passive"))
      (node (ref "SW9") (pin "10") (pinfunction "10_10") (pintype "passive"))
      (node (ref "U1") (pin "3") (pinfunction "A2_3") (pintype "input"))
    )
    (net (code "286") (name "Net-(U1-A3)") (class "Default")
      (node (ref "R6") (pin "2") (pinfunction "2_2") (pintype "passive"))
      (node (ref "SW0") (pin "11") (pinfunction "11_11") (pintype "passive"))
      (node (ref "SW1") (pin "11") (pinfunction "11_11") (pintype "passive"))
      (node (ref "SW10") (pin "11") (pinfunction "11_11") (pintype "passive"))
      (node (ref "SW11") (pin "11") (pinfunction "11_11") (pintype "passive"))
      (node (ref "SW12") (pin "11") (pinfunction "11_11") (pintype "passive"))
      (node (ref "SW13") (pin "11") (pinfunction "11_11") (pintype "passive"))
      (node (ref "SW14") (pin "11") (pinfunction "11_11") (pintype "passive"))
      (node (ref "SW15") (pin "11") (pinfunction "11_11") (pintype "passive"))
      (node (ref "SW2") (pin "11") (pinfunction "11_11") (pintype "passive"))
      (node (ref "SW3") (pin "11") (pinfunction "11_11") (pintype "passive"))
      (node (ref "SW4") (pin "11") (pinfunction "11_11") (pintype "passive"))
      (node (ref "SW5") (pin "11") (pinfunction "11_11") (pintype "passive"))
      (node (ref "SW6") (pin "11") (pinfunction "11_11") (pintype "passive"))
      (node (ref "SW7") (pin "11") (pinfunction "11_11") (pintype "passive"))
      (node (ref "SW8") (pin "11") (pinfunction "11_11") (pintype "passive"))
      (node (ref "SW9") (pin "11") (pinfunction "11_11") (pintype "passive"))
      (node (ref "U1") (pin "4") (pinfunction "A3_4") (pintype "input"))
    )
    (net (code "287") (name "Net-(U1-A4)") (class "Default")
      (node (ref "R5") (pin "2") (pinfunction "2_2") (pintype "passive"))
      (node (ref "SW0") (pin "12") (pinfunction "12_12") (pintype "passive"))
      (node (ref "SW1") (pin "12") (pinfunction "12_12") (pintype "passive"))
      (node (ref "SW10") (pin "12") (pinfunction "12_12") (pintype "passive"))
      (node (ref "SW11") (pin "12") (pinfunction "12_12") (pintype "passive"))
      (node (ref "SW12") (pin "12") (pinfunction "12_12") (pintype "passive"))
      (node (ref "SW13") (pin "12") (pinfunction "12_12") (pintype "passive"))
      (node (ref "SW14") (pin "12") (pinfunction "12_12") (pintype "passive"))
      (node (ref "SW15") (pin "12") (pinfunction "12_12") (pintype "passive"))
      (node (ref "SW2") (pin "12") (pinfunction "12_12") (pintype "passive"))
      (node (ref "SW3") (pin "12") (pinfunction "12_12") (pintype "passive"))
      (node (ref "SW4") (pin "12") (pinfunction "12_12") (pintype "passive"))
      (node (ref "SW5") (pin "12") (pinfunction "12_12") (pintype "passive"))
      (node (ref "SW6") (pin "12") (pinfunction "12_12") (pintype "passive"))
      (node (ref "SW7") (pin "12") (pinfunction "12_12") (pintype "passive"))
      (node (ref "SW8") (pin "12") (pinfunction "12_12") (pintype "passive"))
      (node (ref "SW9") (pin "12") (pinfunction "12_12") (pintype "passive"))
      (node (ref "U1") (pin "5") (pinfunction "A4_5") (pintype "input"))
    )
    (net (code "288") (name "Net-(U1-A5)") (class "Default")
      (node (ref "R4") (pin "2") (pinfunction "2_2") (pintype "passive"))
      (node (ref "SW0") (pin "13") (pinfunction "13_13") (pintype "passive"))
      (node (ref "SW1") (pin "13") (pinfunction "13_13") (pintype "passive"))
      (node (ref "SW10") (pin "13") (pinfunction "13_13") (pintype "passive"))
      (node (ref "SW11") (pin "13") (pinfunction "13_13") (pintype "passive"))
      (node (ref "SW12") (pin "13") (pinfunction "13_13") (pintype "passive"))
      (node (ref "SW13") (pin "13") (pinfunction "13_13") (pintype "passive"))
      (node (ref "SW14") (pin "13") (pinfunction "13_13") (pintype "passive"))
      (node (ref "SW15") (pin "13") (pinfunction "13_13") (pintype "passive"))
      (node (ref "SW2") (pin "13") (pinfunction "13_13") (pintype "passive"))
      (node (ref "SW3") (pin "13") (pinfunction "13_13") (pintype "passive"))
      (node (ref "SW4") (pin "13") (pinfunction "13_13") (pintype "passive"))
      (node (ref "SW5") (pin "13") (pinfunction "13_13") (pintype "passive"))
      (node (ref "SW6") (pin "13") (pinfunction "13_13") (pintype "passive"))
      (node (ref "SW7") (pin "13") (pinfunction "13_13") (pintype "passive"))
      (node (ref "SW8") (pin "13") (pinfunction "13_13") (pintype "passive"))
      (node (ref "SW9") (pin "13") (pinfunction "13_13") (pintype "passive"))
      (node (ref "U1") (pin "6") (pinfunction "A5_6") (pintype "input"))
    )
    (net (code "289") (name "Net-(U1-A6)") (class "Default")
      (node (ref "R3") (pin "2") (pinfunction "2_2") (pintype "passive"))
      (node (ref "SW0") (pin "14") (pinfunction "14_14") (pintype "passive"))
      (node (ref "SW1") (pin "14") (pinfunction "14_14") (pintype "passive"))
      (node (ref "SW10") (pin "14") (pinfunction "14_14") (pintype "passive"))
      (node (ref "SW11") (pin "14") (pinfunction "14_14") (pintype "passive"))
      (node (ref "SW12") (pin "14") (pinfunction "14_14") (pintype "passive"))
      (node (ref "SW13") (pin "14") (pinfunction "14_14") (pintype "passive"))
      (node (ref "SW14") (pin "14") (pinfunction "14_14") (pintype "passive"))
      (node (ref "SW15") (pin "14") (pinfunction "14_14") (pintype "passive"))
      (node (ref "SW2") (pin "14") (pinfunction "14_14") (pintype "passive"))
      (node (ref "SW3") (pin "14") (pinfunction "14_14") (pintype "passive"))
      (node (ref "SW4") (pin "14") (pinfunction "14_14") (pintype "passive"))
      (node (ref "SW5") (pin "14") (pinfunction "14_14") (pintype "passive"))
      (node (ref "SW6") (pin "14") (pinfunction "14_14") (pintype "passive"))
      (node (ref "SW7") (pin "14") (pinfunction "14_14") (pintype "passive"))
      (node (ref "SW8") (pin "14") (pinfunction "14_14") (pintype "passive"))
      (node (ref "SW9") (pin "14") (pinfunction "14_14") (pintype "passive"))
      (node (ref "U1") (pin "7") (pinfunction "A6_7") (pintype "input"))
    )
    (net (code "290") (name "Net-(U1-A7)") (class "Default")
      (node (ref "R2") (pin "2") (pinfunction "2_2") (pintype "passive"))
      (node (ref "SW0") (pin "15") (pinfunction "15_15") (pintype "passive"))
      (node (ref "SW1") (pin "15") (pinfunction "15_15") (pintype "passive"))
      (node (ref "SW10") (pin "15") (pinfunction "15_15") (pintype "passive"))
      (node (ref "SW11") (pin "15") (pinfunction "15_15") (pintype "passive"))
      (node (ref "SW12") (pin "15") (pinfunction "15_15") (pintype "passive"))
      (node (ref "SW13") (pin "15") (pinfunction "15_15") (pintype "passive"))
      (node (ref "SW14") (pin "15") (pinfunction "15_15") (pintype "passive"))
      (node (ref "SW15") (pin "15") (pinfunction "15_15") (pintype "passive"))
      (node (ref "SW2") (pin "15") (pinfunction "15_15") (pintype "passive"))
      (node (ref "SW3") (pin "15") (pinfunction "15_15") (pintype "passive"))
      (node (ref "SW4") (pin "15") (pinfunction "15_15") (pintype "passive"))
      (node (ref "SW5") (pin "15") (pinfunction "15_15") (pintype "passive"))
      (node (ref "SW6") (pin "15") (pinfunction "15_15") (pintype "passive"))
      (node (ref "SW7") (pin "15") (pinfunction "15_15") (pintype "passive"))
      (node (ref "SW8") (pin "15") (pinfunction "15_15") (pintype "passive"))
      (node (ref "SW9") (pin "15") (pinfunction "15_15") (pintype "passive"))
      (node (ref "U1") (pin "8") (pinfunction "A7_8") (pintype "input"))
    )
    (net (code "291") (name "Net-(U1-A8)") (class "Default")
      (node (ref "R1") (pin "2") (pinfunction "2_2") (pintype "passive"))
      (node (ref "SW0") (pin "16") (pinfunction "16_16") (pintype "passive"))
      (node (ref "SW1") (pin "16") (pinfunction "16_16") (pintype "passive"))
      (node (ref "SW10") (pin "16") (pinfunction "16_16") (pintype "passive"))
      (node (ref "SW11") (pin "16") (pinfunction "16_16") (pintype "passive"))
      (node (ref "SW12") (pin "16") (pinfunction "16_16") (pintype "passive"))
      (node (ref "SW13") (pin "16") (pinfunction "16_16") (pintype "passive"))
      (node (ref "SW14") (pin "16") (pinfunction "16_16") (pintype "passive"))
      (node (ref "SW15") (pin "16") (pinfunction "16_16") (pintype "passive"))
      (node (ref "SW2") (pin "16") (pinfunction "16_16") (pintype "passive"))
      (node (ref "SW3") (pin "16") (pinfunction "16_16") (pintype "passive"))
      (node (ref "SW4") (pin "16") (pinfunction "16_16") (pintype "passive"))
      (node (ref "SW5") (pin "16") (pinfunction "16_16") (pintype "passive"))
      (node (ref "SW6") (pin "16") (pinfunction "16_16") (pintype "passive"))
      (node (ref "SW7") (pin "16") (pinfunction "16_16") (pintype "passive"))
      (node (ref "SW8") (pin "16") (pinfunction "16_16") (pintype "passive"))
      (node (ref "SW9") (pin "16") (pinfunction "16_16") (pintype "passive"))
      (node (ref "U1") (pin "9") (pinfunction "A8_9") (pintype "input"))
    )
    (net (code "292") (name "Net-(U3-Pad4)") (class "Default")
      (node (ref "U3") (pin "4") (pintype "input"))
      (node (ref "U4") (pin "12") (pintype "output"))
      (node (ref "U4") (pin "4") (pintype "input"))
    )
    (net (code "293") (name "Net-(U3-Pad8)") (class "Default")
      (node (ref "U3") (pin "8") (pintype "output"))
      (node (ref "U4") (pin "9") (pintype "input"))
    )
    (net (code "294") (name "Net-(U5-Pad10)") (class "Default")
      (node (ref "U5") (pin "10") (pintype "output"))
      (node (ref "U5") (pin "13") (pintype "input"))
    )
    (net (code "295") (name "VCC") (class "Default")
      (node (ref "C1") (pin "2") (pinfunction "2_2") (pintype "passive"))
      (node (ref "C10") (pin "2") (pinfunction "2_2") (pintype "passive"))
      (node (ref "C11") (pin "2") (pinfunction "2_2") (pintype "passive"))
      (node (ref "C12") (pin "2") (pinfunction "2_2") (pintype "passive"))
      (node (ref "C13") (pin "2") (pinfunction "2_2") (pintype "passive"))
      (node (ref "C14") (pin "2") (pinfunction "2_2") (pintype "passive"))
      (node (ref "C15") (pin "2") (pinfunction "2_2") (pintype "passive"))
      (node (ref "C2") (pin "2") (pinfunction "2_2") (pintype "passive"))
      (node (ref "C3") (pin "2") (pinfunction "2_2") (pintype "passive"))
      (node (ref "C4") (pin "2") (pinfunction "2_2") (pintype "passive"))
      (node (ref "C5") (pin "2") (pinfunction "2_2") (pintype "passive"))
      (node (ref "C6") (pin "2") (pinfunction "2_2") (pintype "passive"))
      (node (ref "C7") (pin "2") (pinfunction "2_2") (pintype "passive"))
      (node (ref "C8") (pin "2") (pinfunction "2_2") (pintype "passive"))
      (node (ref "C9") (pin "2") (pinfunction "2_2") (pintype "passive"))
      (node (ref "LED74") (pin "1") (pinfunction "A_1") (pintype "passive"))
      (node (ref "R1") (pin "1") (pinfunction "1_1") (pintype "passive"))
      (node (ref "R10") (pin "2") (pinfunction "2_2") (pintype "passive"))
      (node (ref "R100") (pin "2") (pinfunction "2_2") (pintype "passive"))
      (node (ref "R101") (pin "2") (pinfunction "2_2") (pintype "passive"))
      (node (ref "R11") (pin "2") (pinfunction "2_2") (pintype "passive"))
      (node (ref "R12") (pin "2") (pinfunction "2_2") (pintype "passive"))
      (node (ref "R13") (pin "2") (pinfunction "2_2") (pintype "passive"))
      (node (ref "R14") (pin "2") (pinfunction "2_2") (pintype "passive"))
      (node (ref "R15") (pin "2") (pinfunction "2_2") (pintype "passive"))
      (node (ref "R16") (pin "2") (pinfunction "2_2") (pintype "passive"))
      (node (ref "R17") (pin "2") (pinfunction "2_2") (pintype "passive"))
      (node (ref "R18") (pin "2") (pinfunction "2_2") (pintype "passive"))
      (node (ref "R19") (pin "2") (pinfunction "2_2") (pintype "passive"))
      (node (ref "R2") (pin "1") (pinfunction "1_1") (pintype "passive"))
      (node (ref "R20") (pin "2") (pinfunction "2_2") (pintype "passive"))
      (node (ref "R21") (pin "2") (pinfunction "2_2") (pintype "passive"))
      (node (ref "R22") (pin "2") (pinfunction "2_2") (pintype "passive"))
      (node (ref "R23") (pin "2") (pinfunction "2_2") (pintype "passive"))
      (node (ref "R24") (pin "2") (pinfunction "2_2") (pintype "passive"))
      (node (ref "R27") (pin "2") (pinfunction "2_2") (pintype "passive"))
      (node (ref "R29") (pin "2") (pinfunction "2_2") (pintype "passive"))
      (node (ref "R3") (pin "1") (pinfunction "1_1") (pintype "passive"))
      (node (ref "R32") (pin "2") (pinfunction "2_2") (pintype "passive"))
      (node (ref "R35") (pin "2") (pinfunction "2_2") (pintype "passive"))
      (node (ref "R4") (pin "1") (pinfunction "1_1") (pintype "passive"))
      (node (ref "R41") (pin "2") (pinfunction "2_2") (pintype "passive"))
      (node (ref "R45") (pin "1") (pinfunction "1_1") (pintype "passive"))
      (node (ref "R5") (pin "1") (pinfunction "1_1") (pintype "passive"))
      (node (ref "R6") (pin "1") (pinfunction "1_1") (pintype "passive"))
      (node (ref "R7") (pin "1") (pinfunction "1_1") (pintype "passive"))
      (node (ref "R75") (pin "2") (pinfunction "2_2") (pintype "passive"))
      (node (ref "R8") (pin "1") (pinfunction "1_1") (pintype "passive"))
      (node (ref "R82") (pin "2") (pinfunction "2_2") (pintype "passive"))
      (node (ref "R9") (pin "2") (pinfunction "2_2") (pintype "passive"))
      (node (ref "R98") (pin "2") (pinfunction "2_2") (pintype "passive"))
      (node (ref "R99") (pin "2") (pinfunction "2_2") (pintype "passive"))
      (node (ref "SW18") (pin "1") (pinfunction "1_1") (pintype "passive"))
      (node (ref "SW18") (pin "2") (pinfunction "2_2") (pintype "passive"))
      (node (ref "SW18") (pin "3") (pinfunction "3_3") (pintype "passive"))
      (node (ref "SW18") (pin "4") (pinfunction "4_4") (pintype "passive"))
      (node (ref "U1") (pin "20") (pinfunction "VCC_20") (pintype "power_in"))
      (node (ref "U10") (pin "16") (pinfunction "VCC_16") (pintype "power_in"))
      (node (ref "U11") (pin "16") (pinfunction "VCC_16") (pintype "power_in"))
      (node (ref "U12") (pin "16") (pinfunction "VCC_16") (pintype "power_in"))
      (node (ref "U13") (pin "10") (pinfunction "ENT_10") (pintype "input"))
      (node (ref "U13") (pin "16") (pinfunction "VCC_16") (pintype "power_in"))
      (node (ref "U13") (pin "7") (pinfunction "ENP_7") (pintype "input"))
      (node (ref "U2") (pin "24") (pinfunction "VCC_24") (pintype "power_in"))
      (node (ref "U3") (pin "14") (pinfunction "VCC_14") (pintype "power_in"))
      (node (ref "U4") (pin "1") (pintype "input"))
      (node (ref "U4") (pin "14") (pinfunction "VCC_14") (pintype "power_in"))
      (node (ref "U4") (pin "2") (pintype "input"))
      (node (ref "U4") (pin "3") (pintype "input"))
      (node (ref "U5") (pin "14") (pinfunction "VCC_14") (pintype "power_in"))
      (node (ref "U6") (pin "16") (pinfunction "VCC_16") (pintype "power_in"))
      (node (ref "U7") (pin "16") (pinfunction "VCC_16") (pintype "power_in"))
      (node (ref "U8") (pin "16") (pinfunction "VCC_16") (pintype "power_in"))
      (node (ref "U9") (pin "1") (pinfunction "~{CLR}_1") (pintype "input"))
      (node (ref "U9") (pin "10") (pinfunction "~{PRE}_10") (pintype "input"))
      (node (ref "U9") (pin "14") (pinfunction "VCC_14") (pintype "power_in"))
      (node (ref "U9") (pin "4") (pinfunction "~{PRE}_4") (pintype "input"))
      (node (ref "USB1") (pin "A9") (pinfunction "VBUS_A9") (pintype "passive"))
      (node (ref "USB1") (pin "B9") (pinfunction "VBUS_B9") (pintype "passive"))
    )
    (net (code "296") (name "unconnected-(RP1-Pad1)") (class "Default")
      (node (ref "RP1") (pin "1") (pinfunction "1_1") (pintype "passive"))
    )
    (net (code "297") (name "unconnected-(SW16-+-Pad3)") (class "Default")
      (node (ref "SW16") (pin "3") (pinfunction "+_3") (pintype "passive"))
    )
    (net (code "298") (name "unconnected-(SW16---Pad4)") (class "Default")
      (node (ref "SW16") (pin "4") (pinfunction "-_4") (pintype "passive"))
    )
    (net (code "299") (name "unconnected-(SW17-+-Pad3)") (class "Default")
      (node (ref "SW17") (pin "3") (pinfunction "+_3") (pintype "passive"))
    )
    (net (code "300") (name "unconnected-(SW17---Pad4)") (class "Default")
      (node (ref "SW17") (pin "4") (pinfunction "-_4") (pintype "passive"))
    )
    (net (code "301") (name "unconnected-(U5-Pad2)") (class "Default")
      (node (ref "U5") (pin "2") (pintype "output"))
    )
    (net (code "302") (name "unconnected-(U6-RCO-Pad15)") (class "Default")
      (node (ref "U6") (pin "15") (pinfunction "RCO_15") (pintype "output"))
    )
    (net (code "303") (name "unconnected-(U9A-Q-Pad5)") (class "Default")
      (node (ref "U9") (pin "5") (pinfunction "Q_5") (pintype "output"))
    )
    (net (code "304") (name "unconnected-(U9A-~{Q}-Pad6)") (class "Default")
      (node (ref "U9") (pin "6") (pinfunction "~{Q}_6") (pintype "output"))
    )
    (net (code "305") (name "unconnected-(U9B-Q-Pad9)") (class "Default")
      (node (ref "U9") (pin "9") (pinfunction "Q_9") (pintype "output"))
    )
    (net (code "306") (name "unconnected-(U10-RCO-Pad15)") (class "Default")
      (node (ref "U10") (pin "15") (pinfunction "RCO_15") (pintype "output"))
    )
    (net (code "307") (name "unconnected-(U12-RCO-Pad15)") (class "Default")
      (node (ref "U12") (pin "15") (pinfunction "RCO_15") (pintype "output"))
    )
    (net (code "308") (name "unconnected-(U13-RCO-Pad15)") (class "Default")
      (node (ref "U13") (pin "15") (pinfunction "RCO_15") (pintype "output"))
    )
    (net (code "309") (name "unconnected-(USB1-CC1-PadA5)") (class "Default")
      (node (ref "USB1") (pin "A5") (pinfunction "CC1_A5") (pintype "passive"))
    )
    (net (code "310") (name "unconnected-(USB1-CC2-PadB5)") (class "Default")
      (node (ref "USB1") (pin "B5") (pinfunction "CC2_B5") (pintype "passive"))
    )
  )
)
